# star-tracker-card.net
KiCad netlist of a schematic drawn in EAGLE
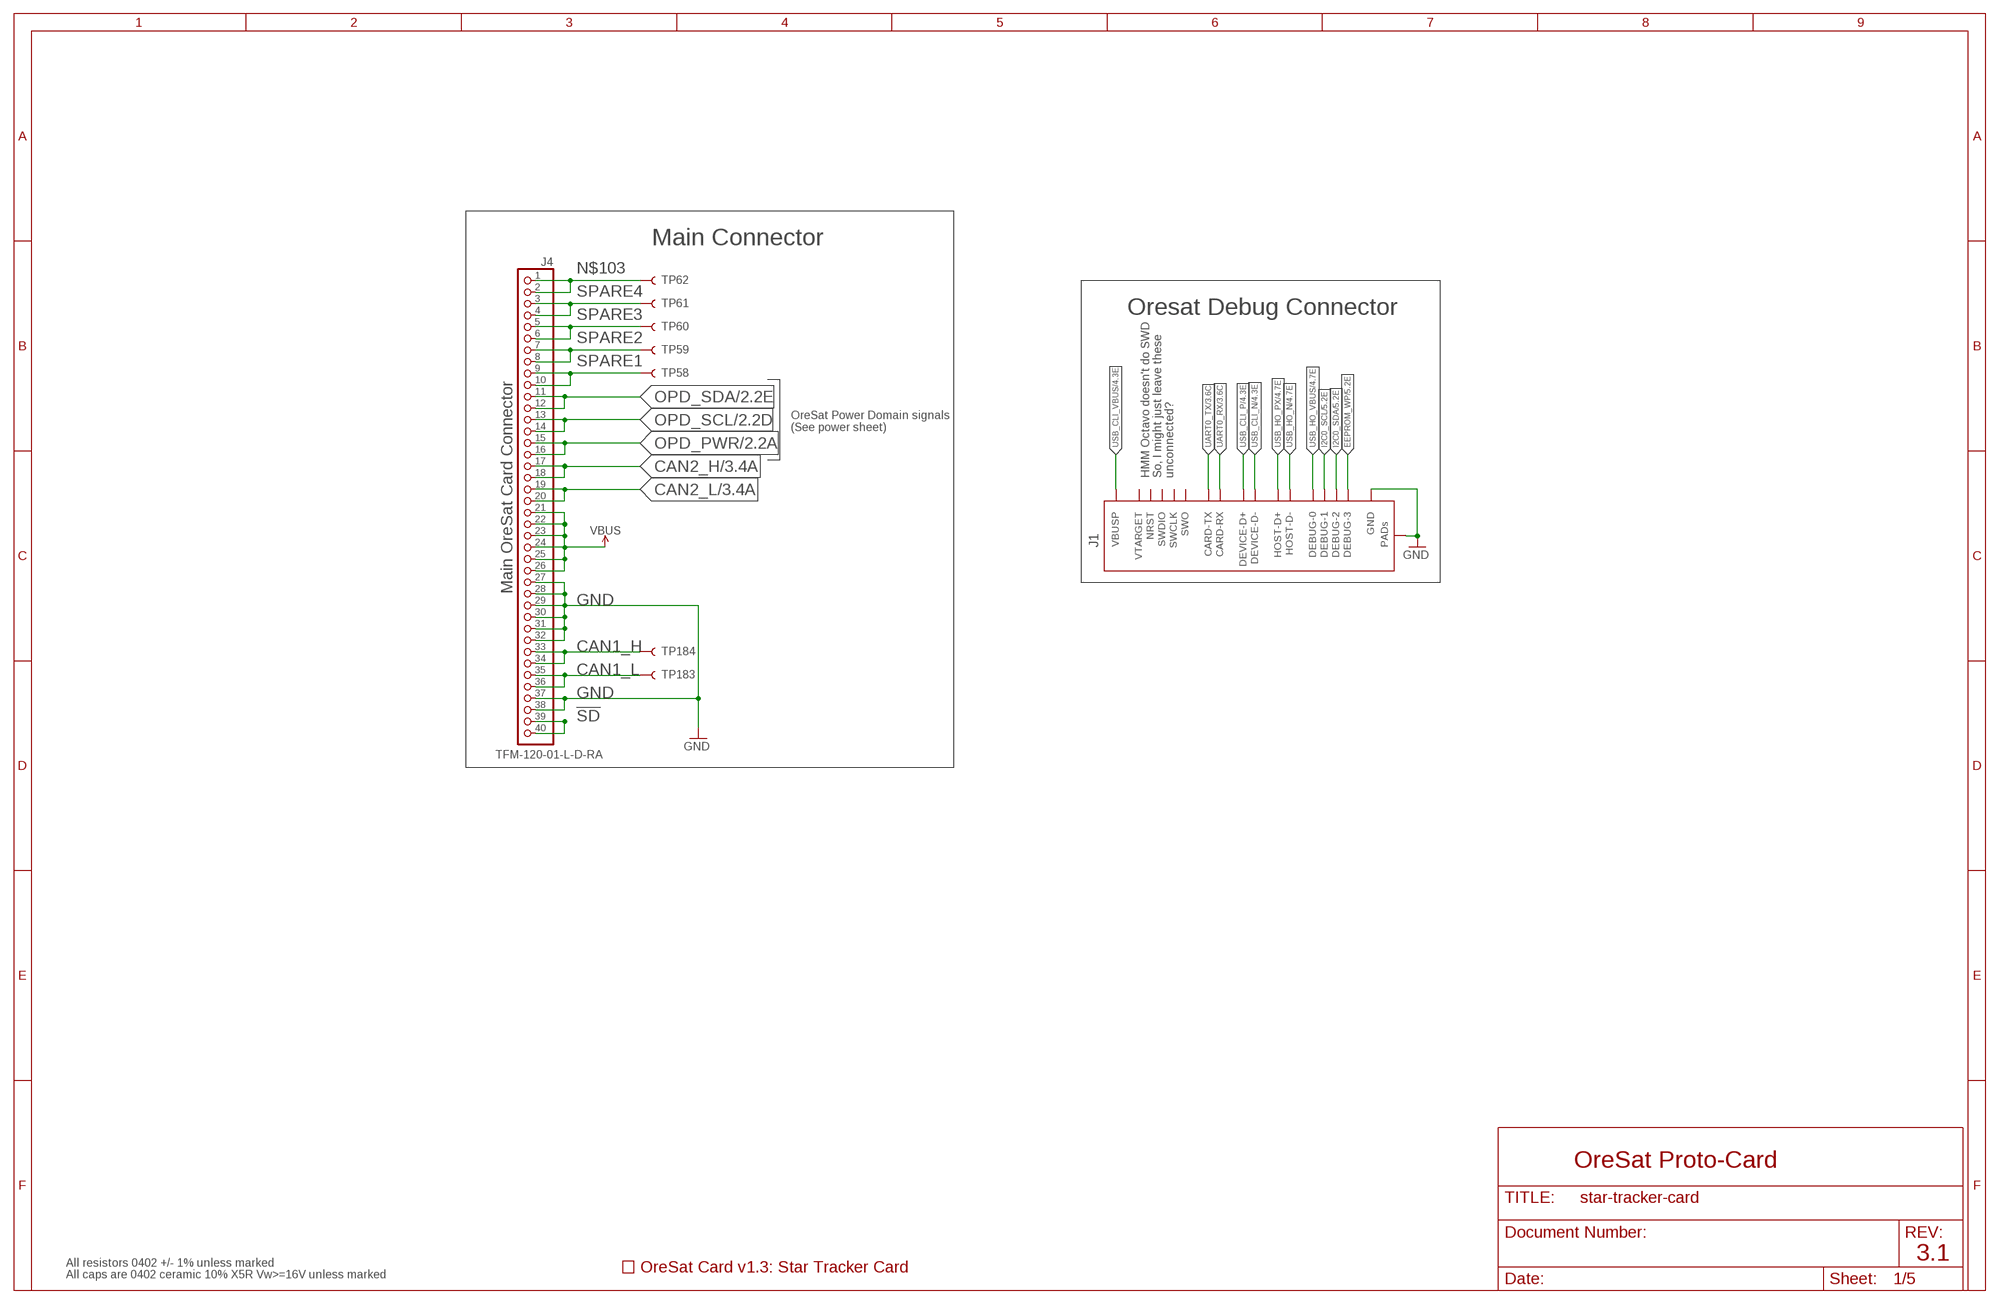
[diagram p0: schematic, sheet 1]
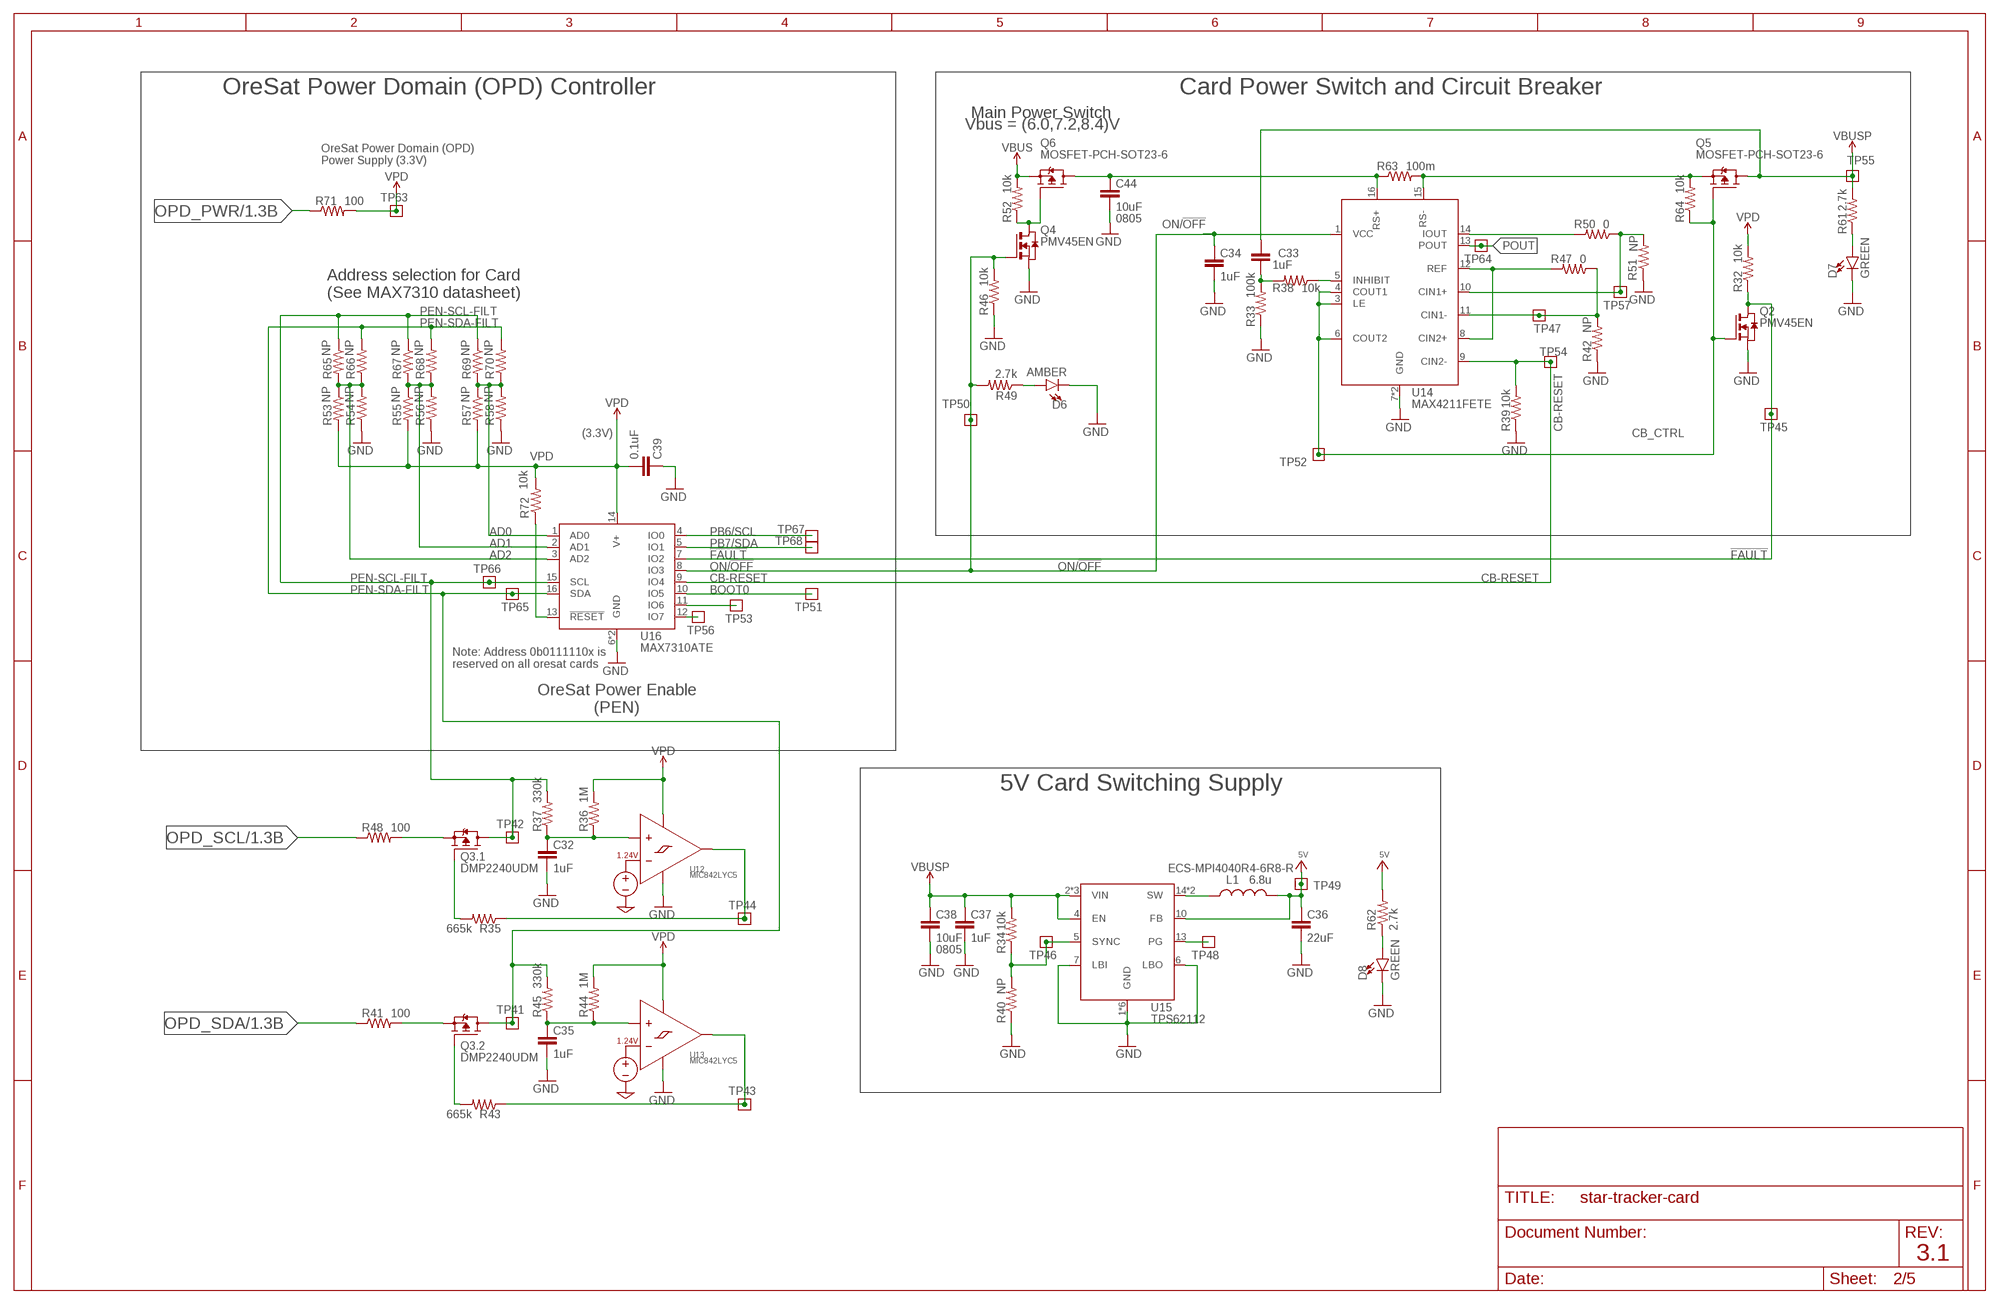
[diagram p1: schematic, sheet 2]
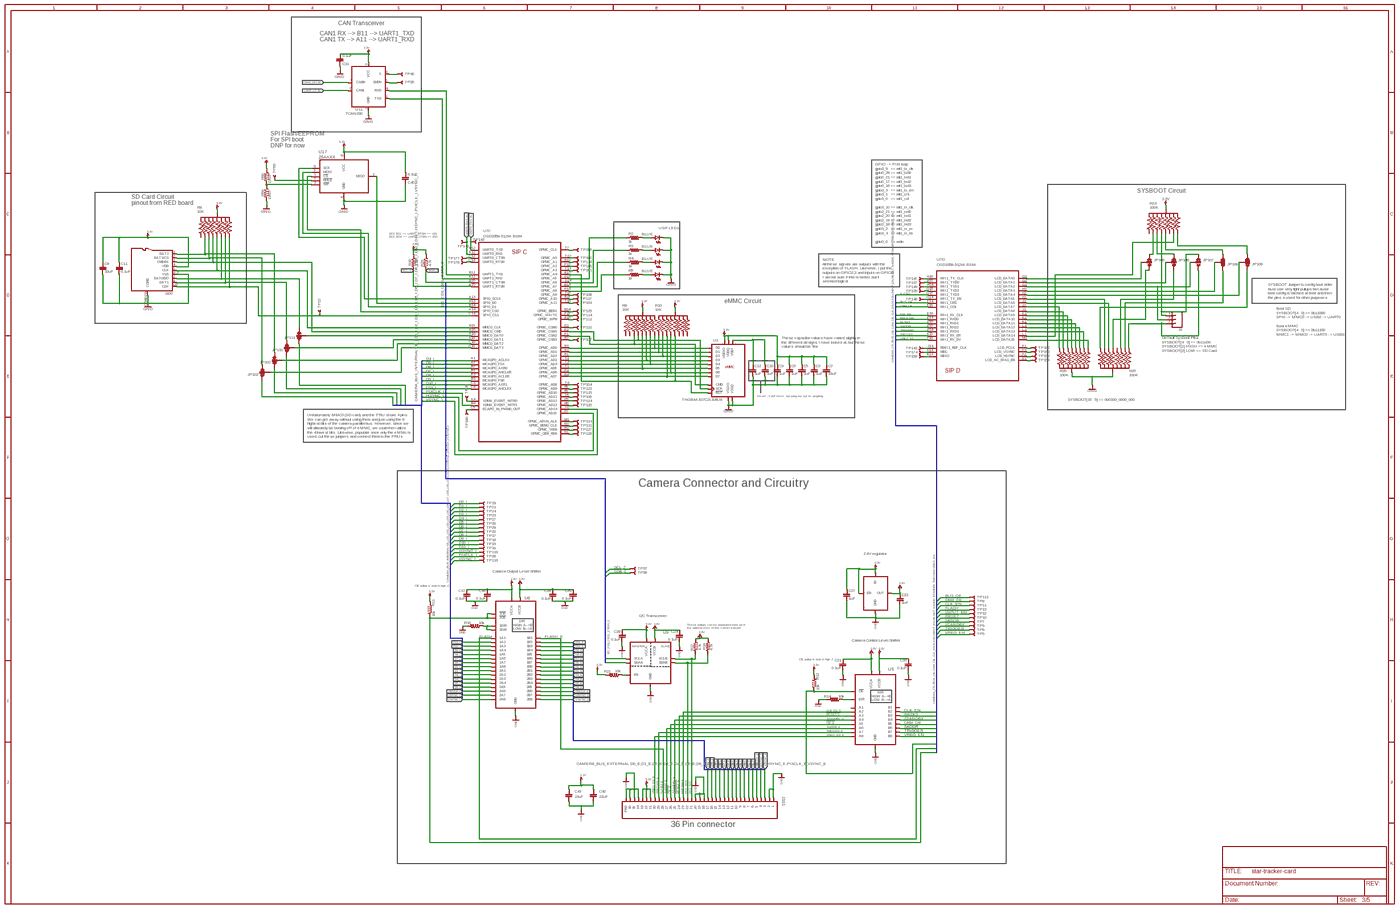
[diagram p2: schematic, sheet 3, overview]
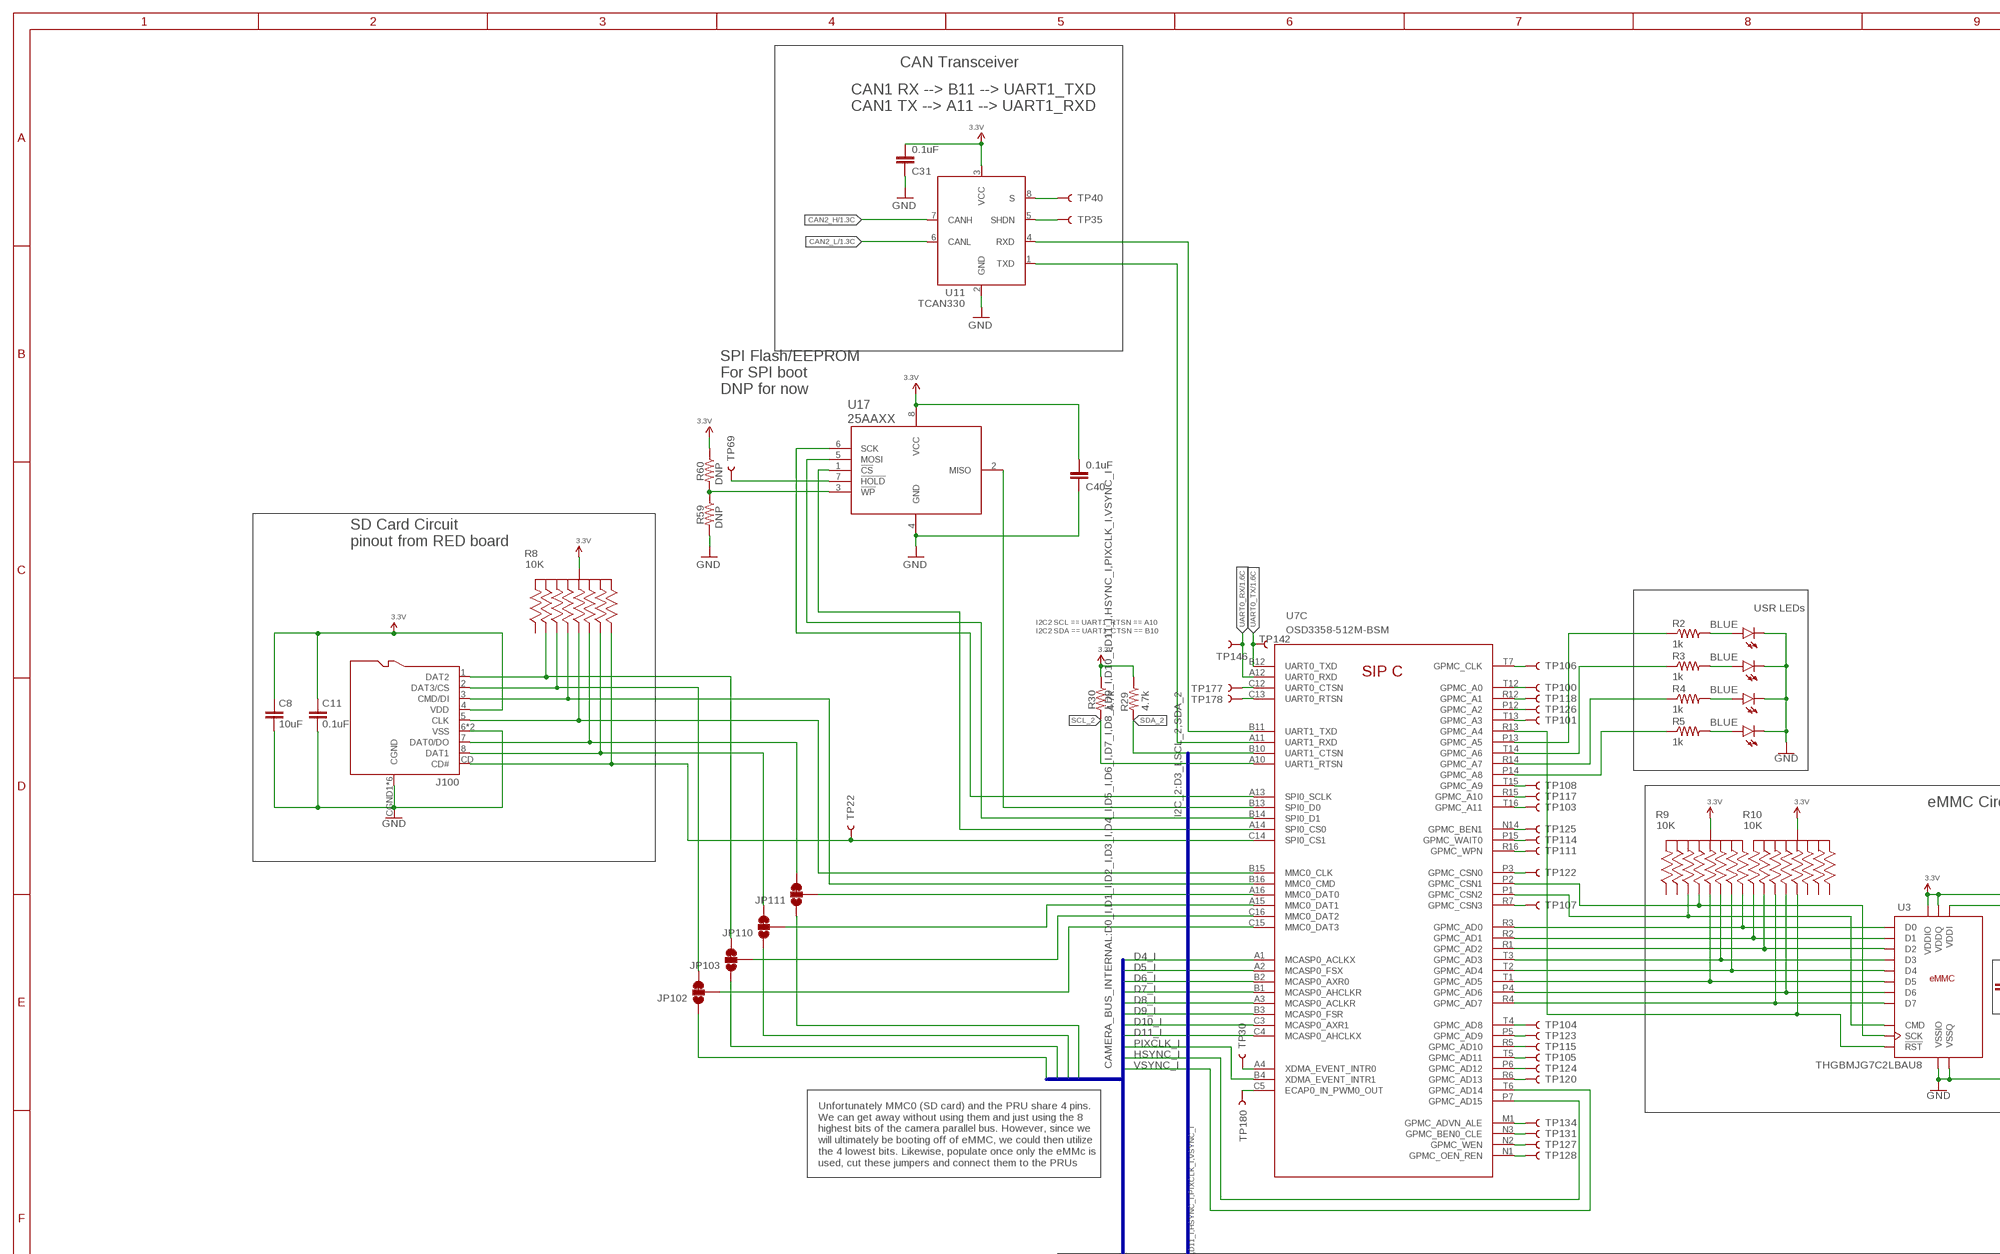
[diagram p3: schematic, sheet 3, part 1 of 4]
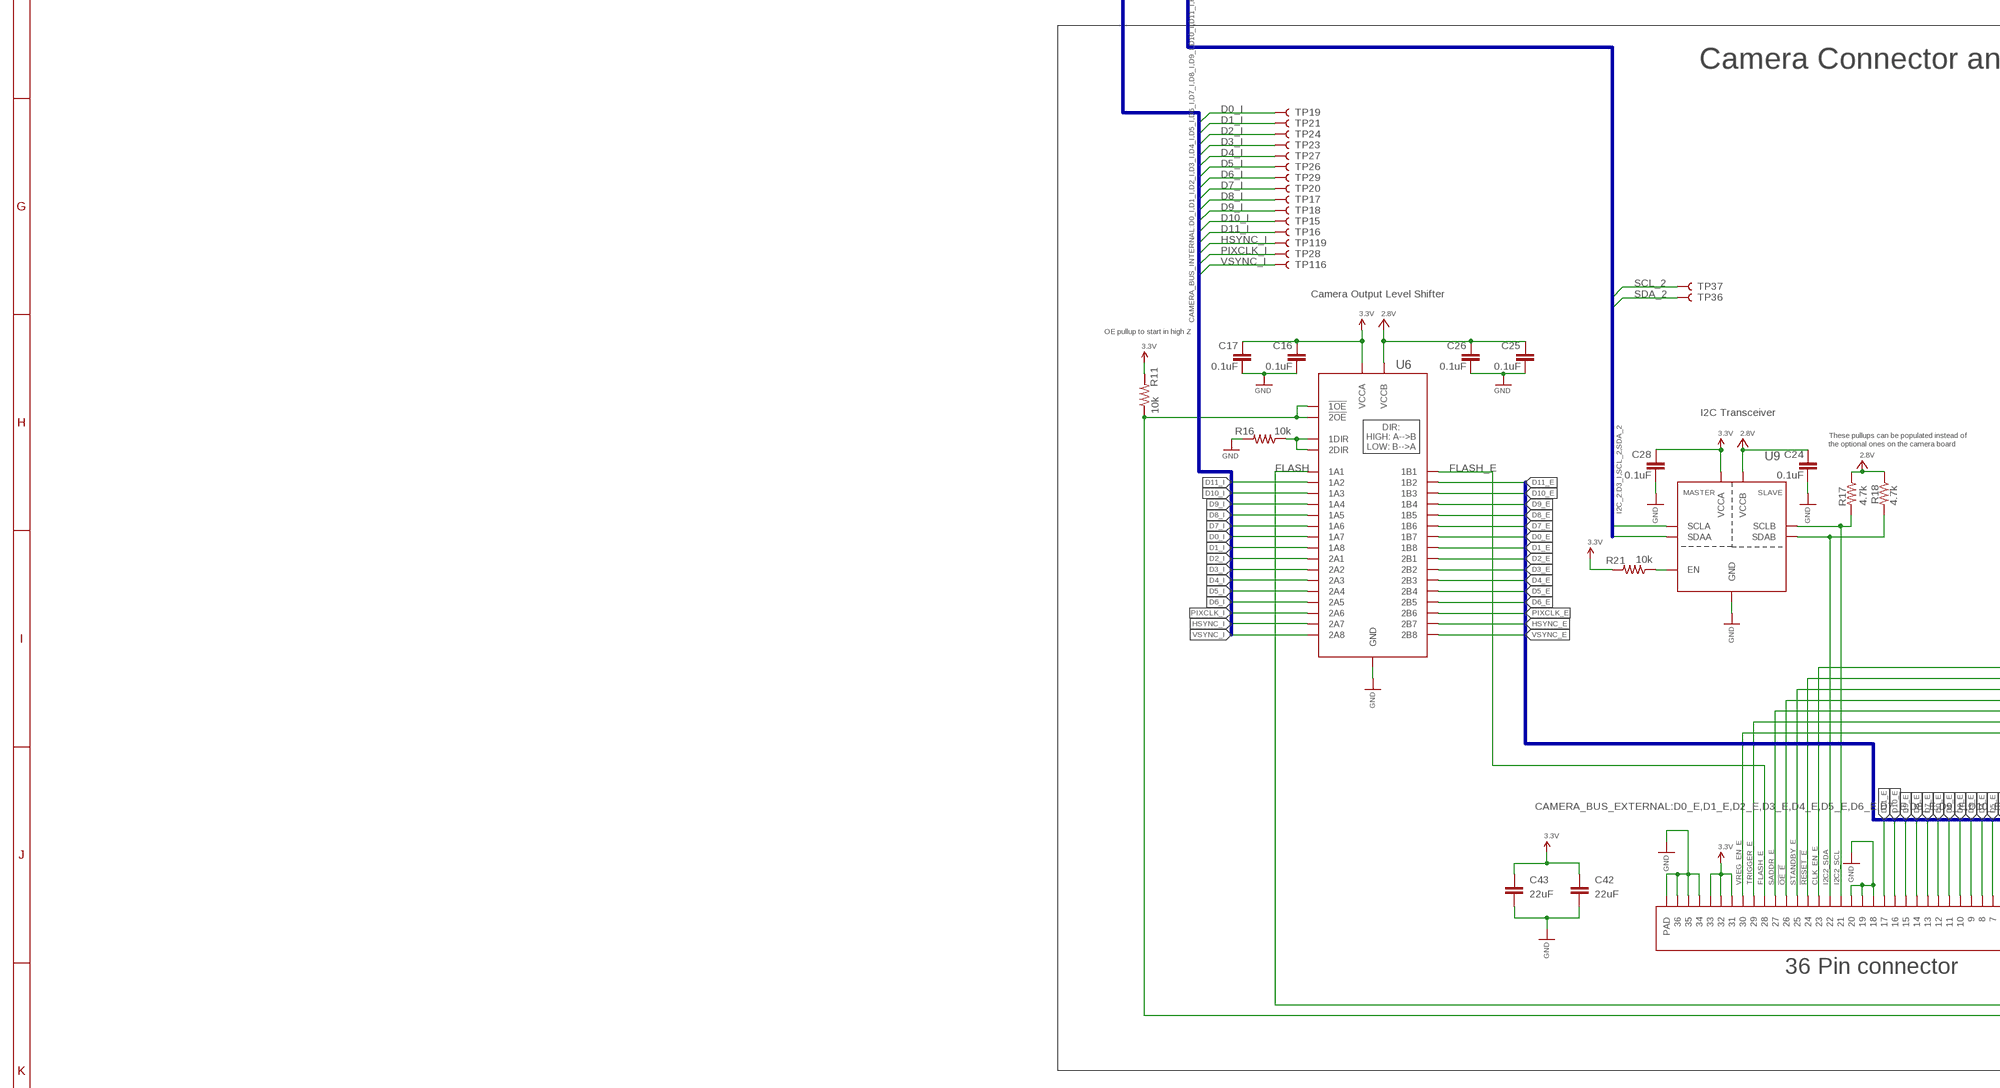
[diagram p4: schematic, sheet 3, part 2 of 4]
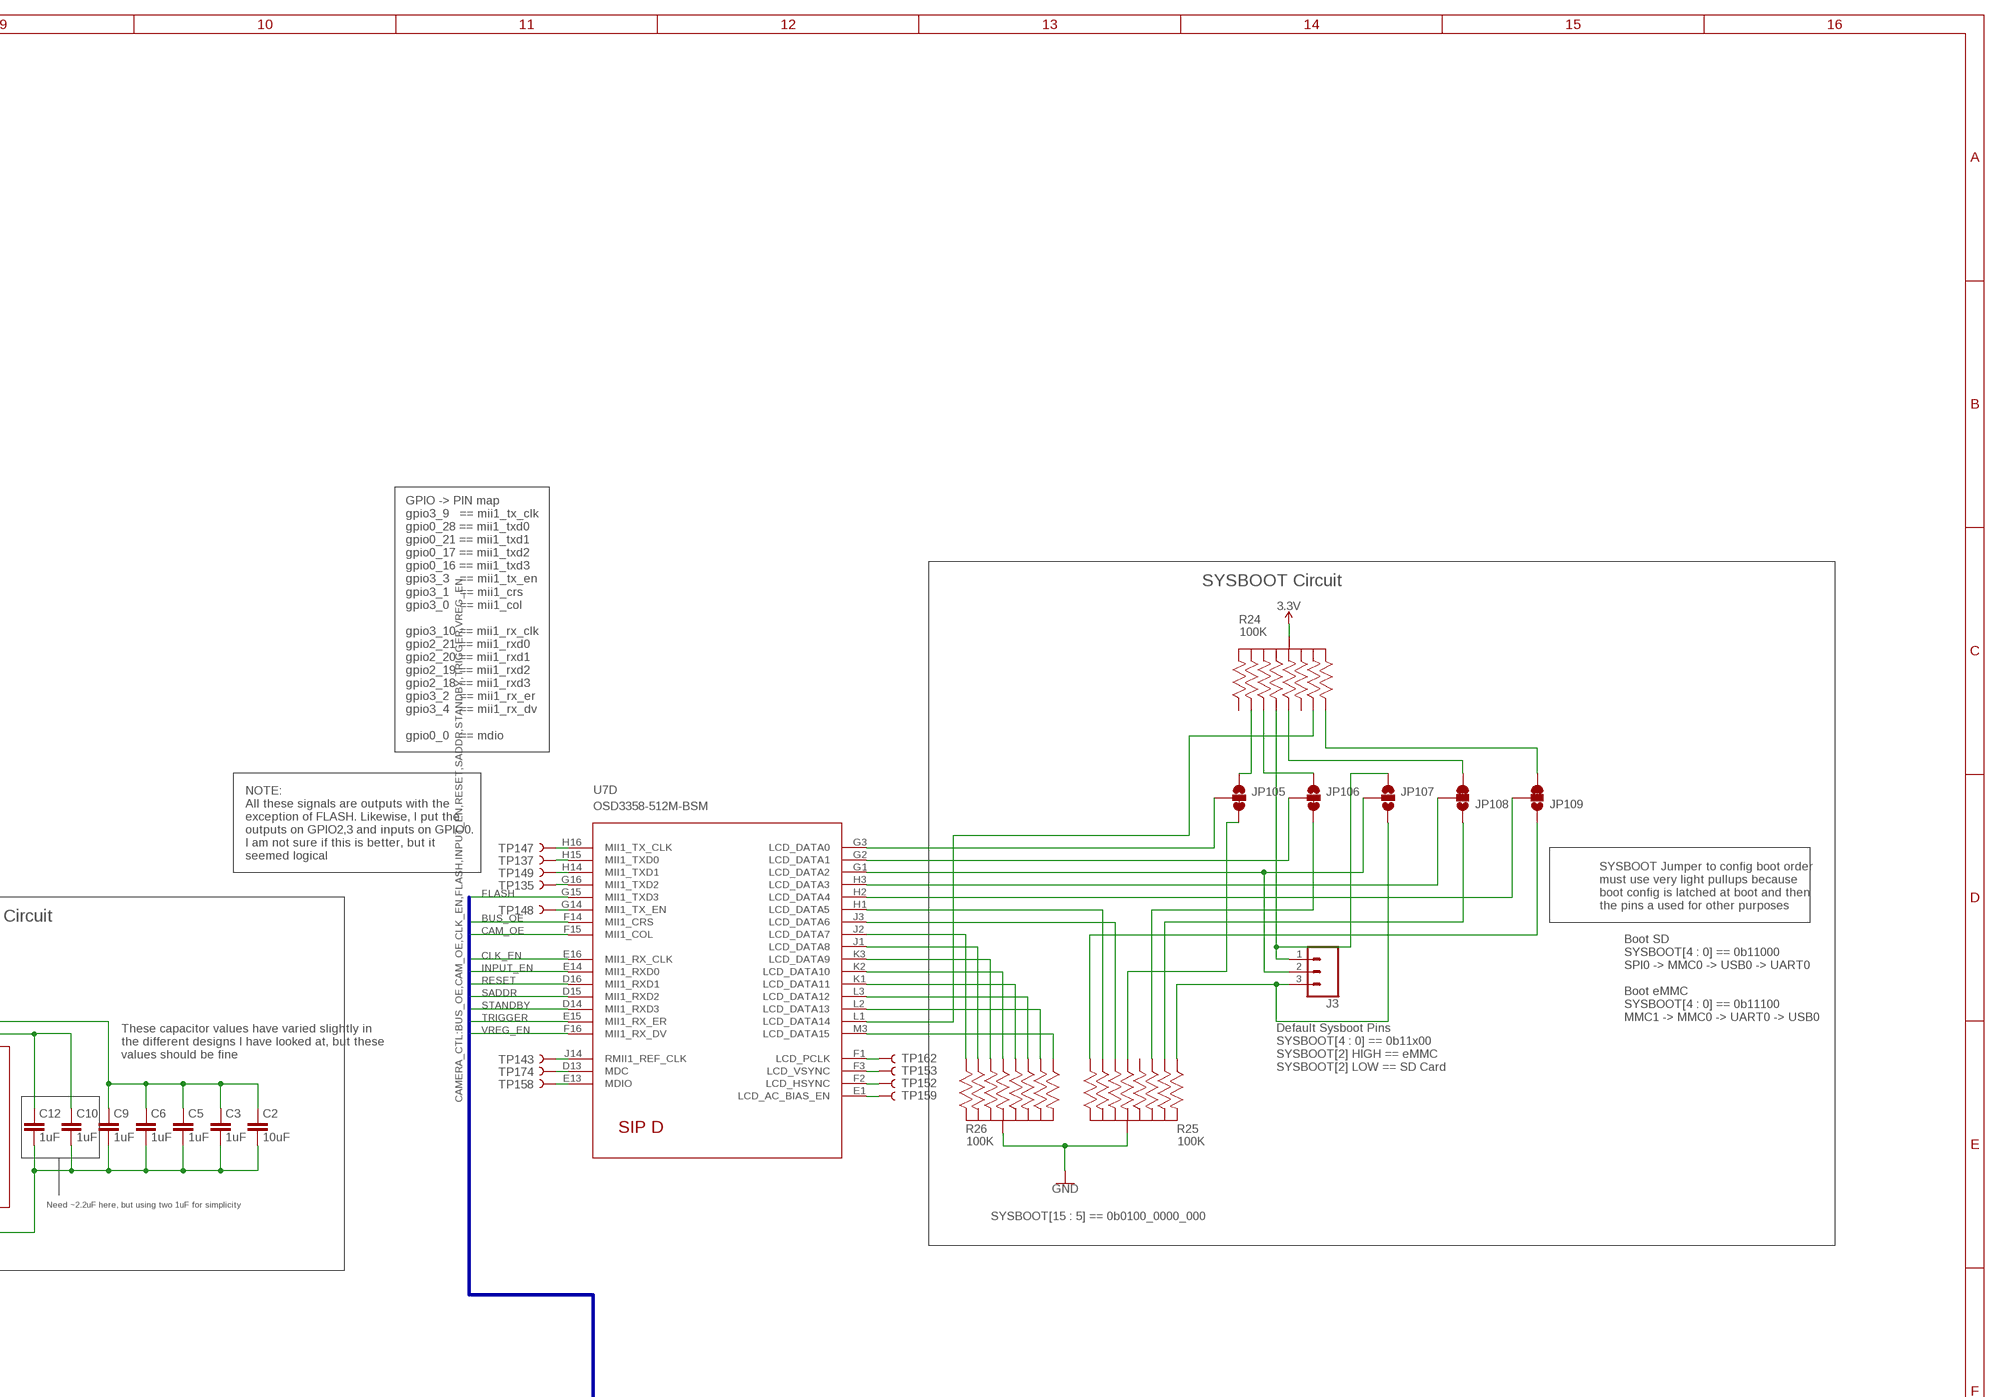
[diagram p5: schematic, sheet 3, part 3 of 4]
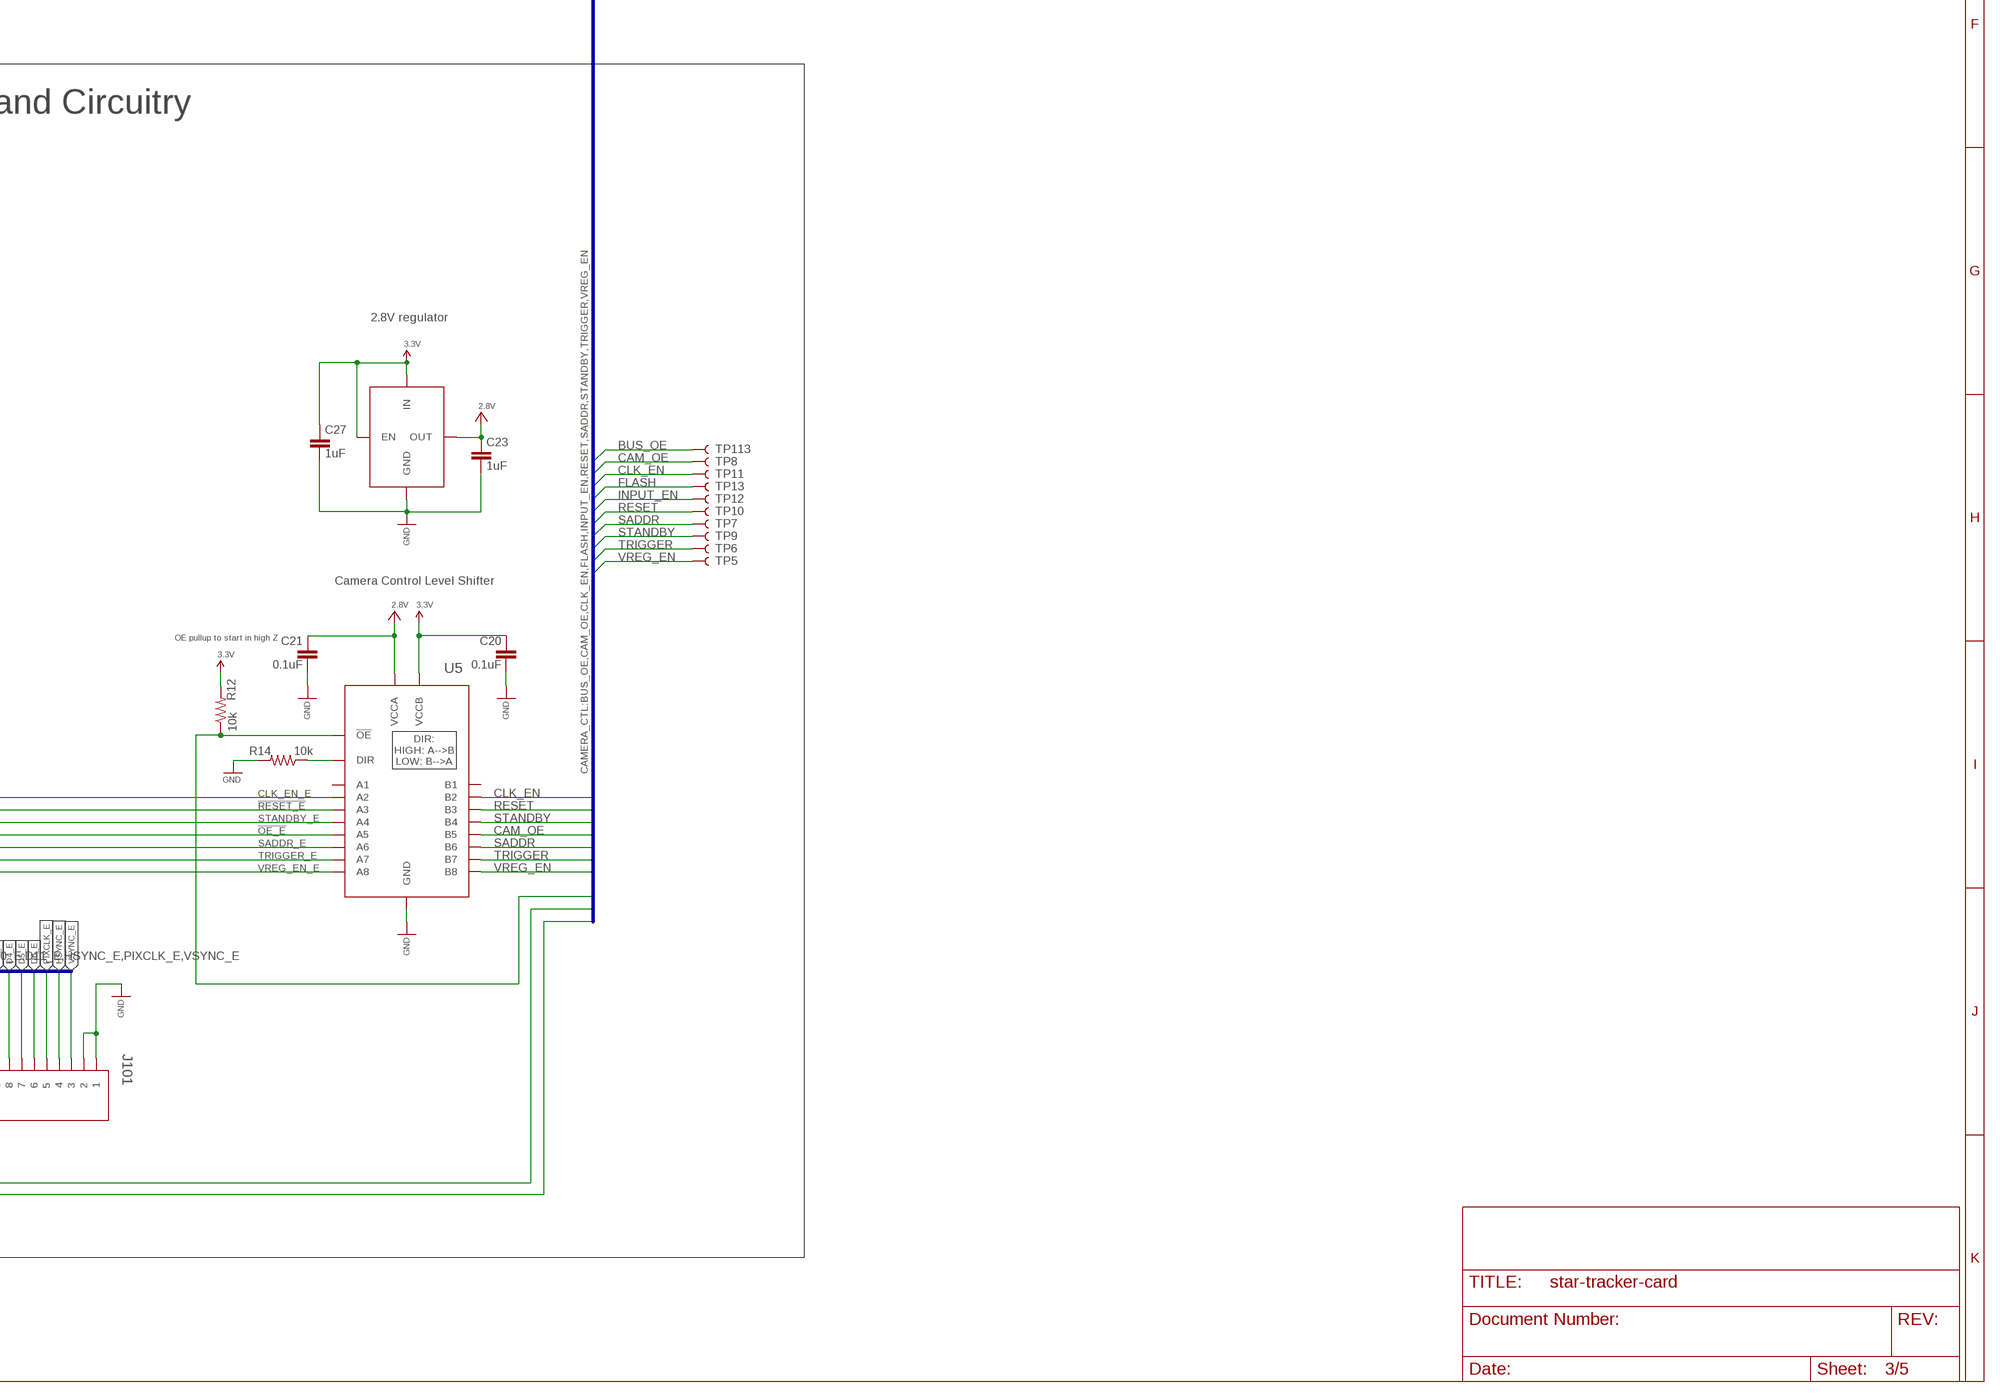
[diagram p6: schematic, sheet 3, part 4 of 4]
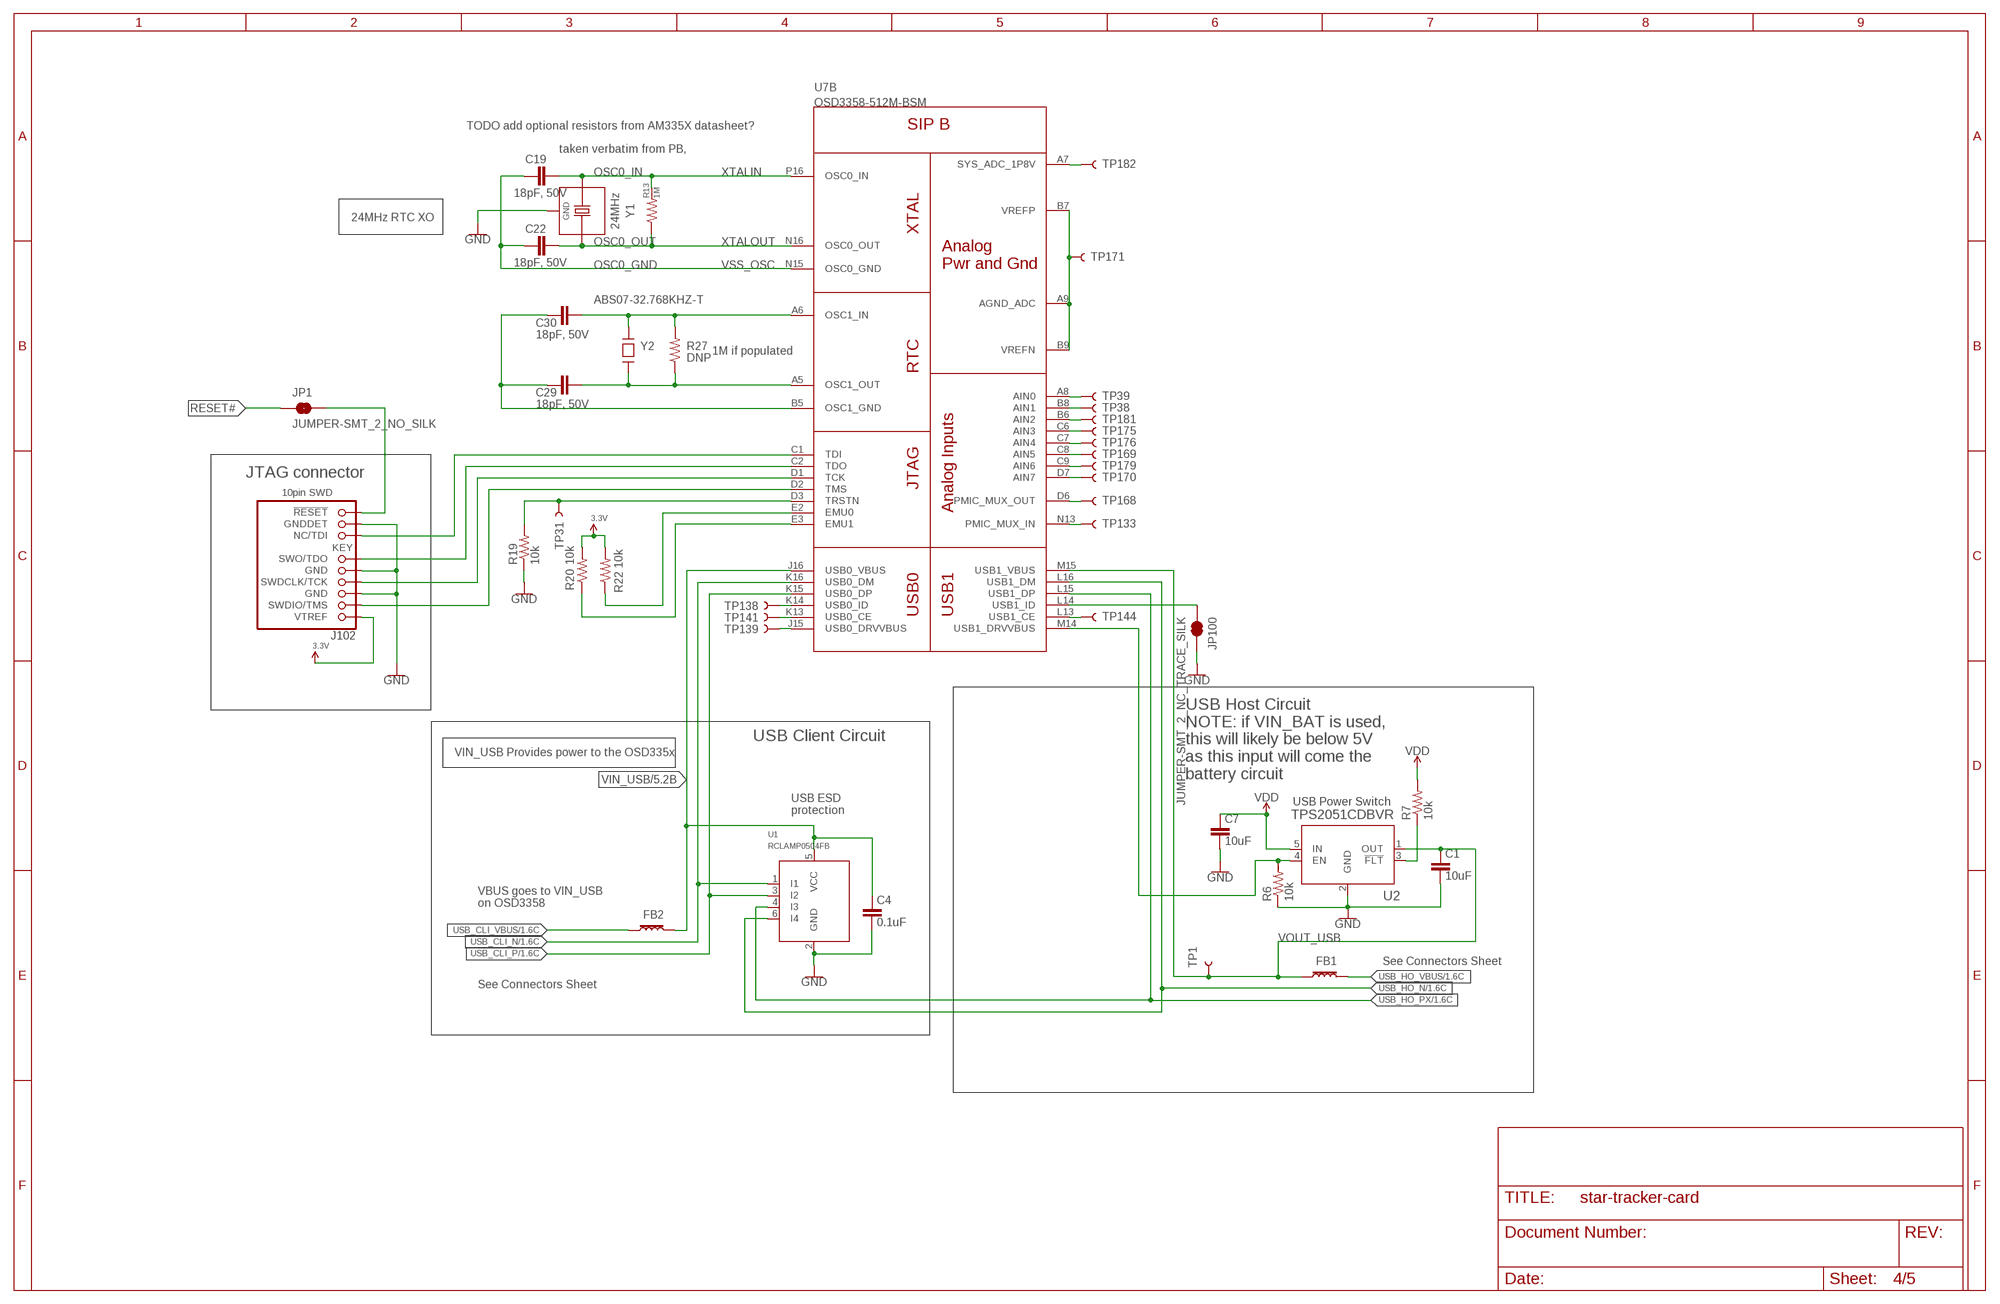
[diagram p7: schematic, sheet 4]
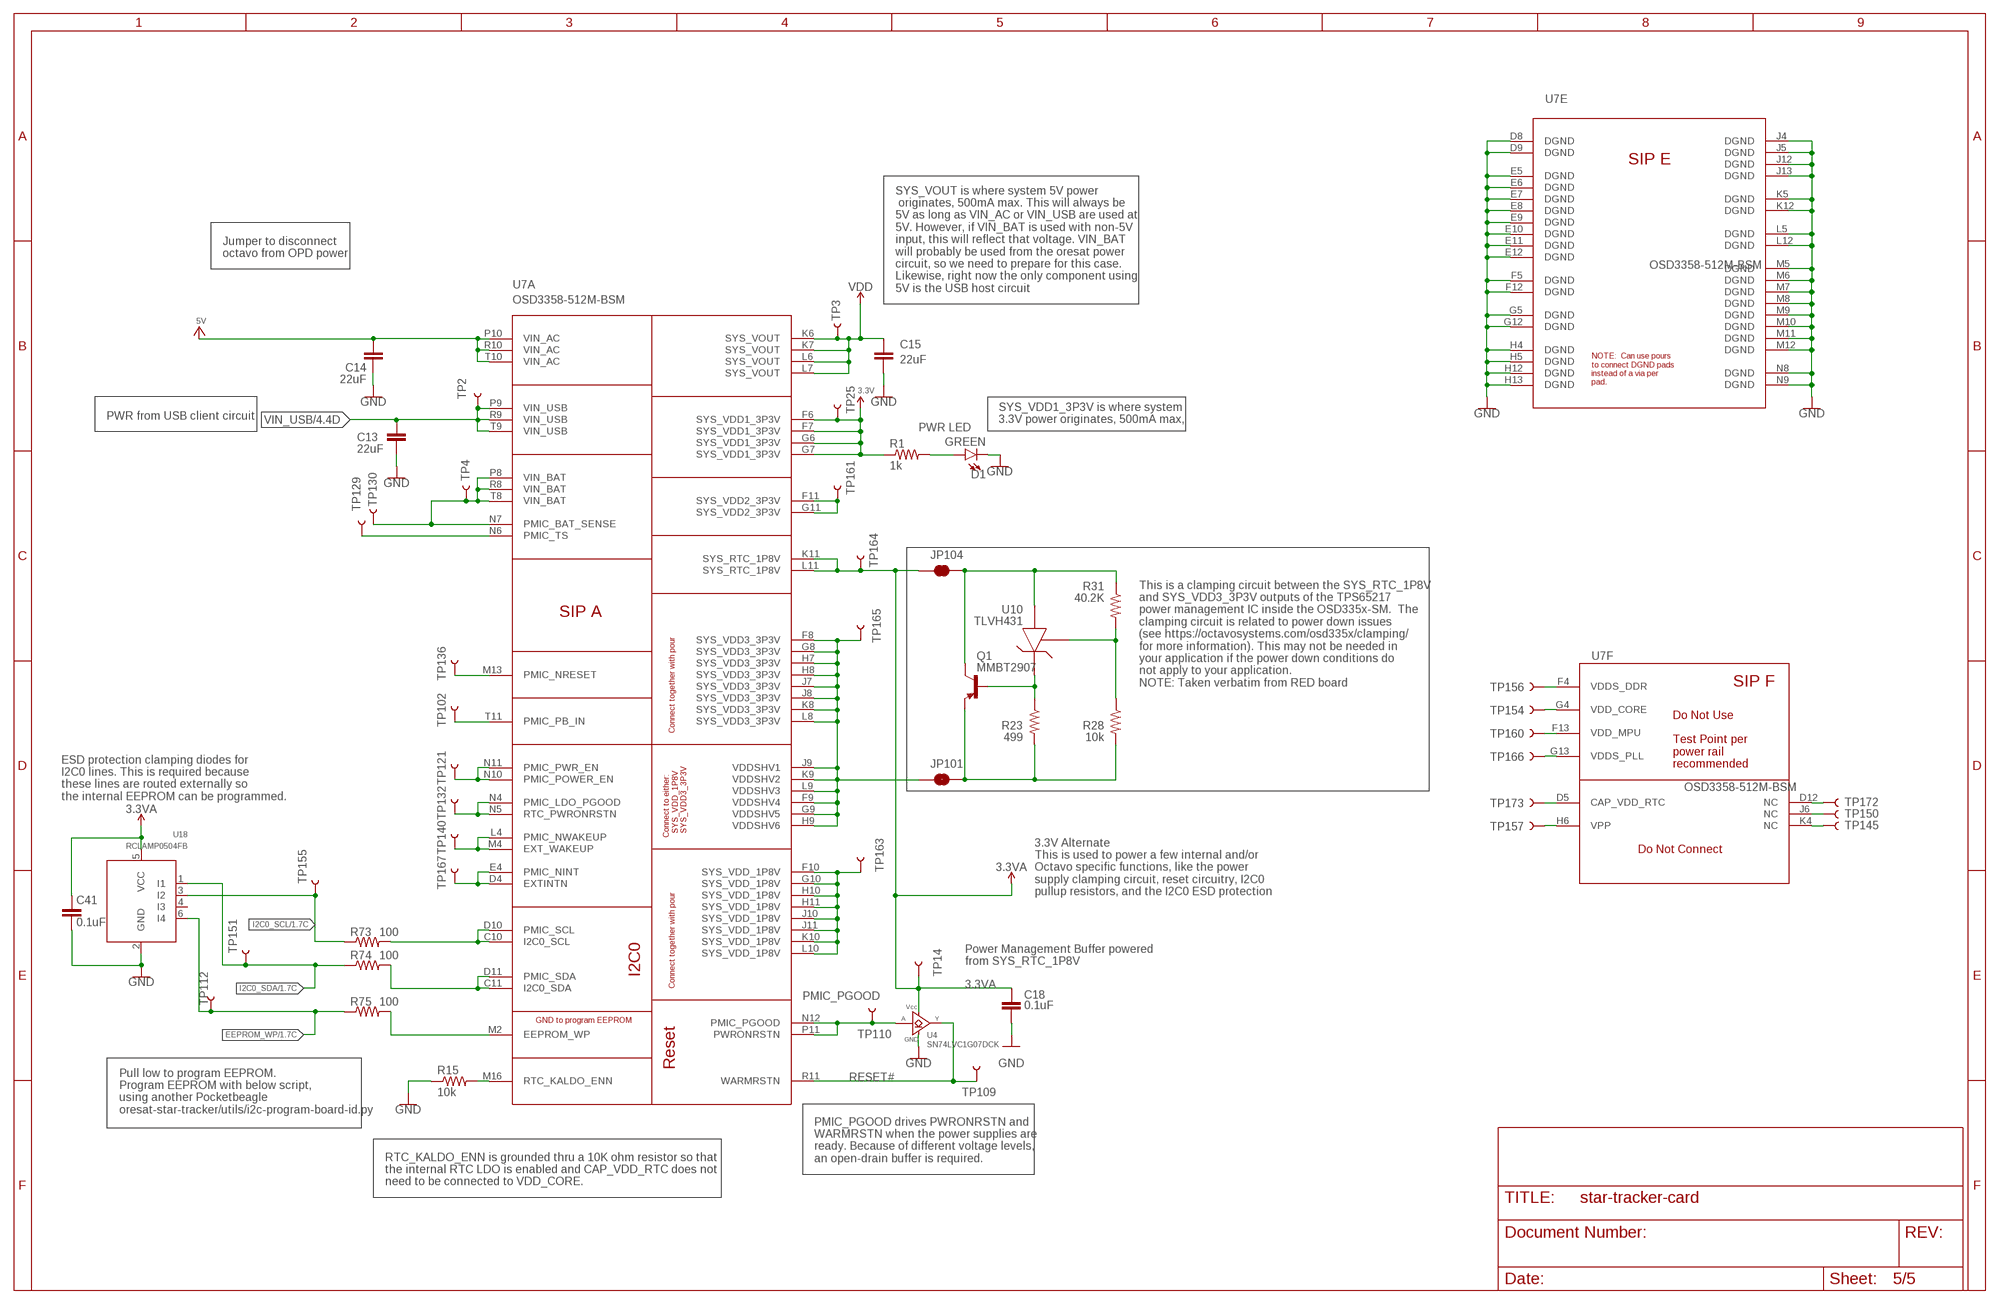
[diagram p8: schematic, sheet 5]

(export (version "E")
  (design (tool "Eeschema 10.0.6"))
  (components
    (comp (ref "C32")
      (value "1uF")
      (footprint "eagle-import:.0805-B-NOSILK")
      (libsource (lib "eagle-import") (part "C-EU0805-B-NOSILK"))
    )
    (comp (ref "C33")
      (value "1uF")
      (footprint "eagle-import:.0603-A")
      (fields (field (name "MFR") "Samsung") (field (name "MPN") "CL05B104KO5NNNC"))
      (libsource (lib "eagle-import") (part "C-EU0603-A"))
    )
    (comp (ref "C34")
      (value "1uF")
      (footprint "eagle-import:.0603-A")
      (libsource (lib "eagle-import") (part "C-EU0603-A"))
    )
    (comp (ref "C35")
      (value "1uF")
      (footprint "eagle-import:.0805-B-NOSILK")
      (libsource (lib "eagle-import") (part "C-EU0805-B-NOSILK"))
    )
    (comp (ref "C36")
      (value "22uF")
      (footprint "eagle-import:C1210")
      (libsource (lib "eagle-import") (part "C-EUC1210"))
    )
    (comp (ref "C37")
      (value "1uF")
      (footprint "eagle-import:.0603-A")
      (libsource (lib "eagle-import") (part "C-EU0603-A"))
    )
    (comp (ref "C38")
      (value "10uF")
      (footprint "eagle-import:.0805-B")
      (libsource (lib "eagle-import") (part "C-EU0805-B"))
    )
    (comp (ref "C39")
      (value "0.1uF")
      (footprint "eagle-import:.0603-A")
      (libsource (lib "eagle-import") (part "C-EU0603-A"))
    )
    (comp (ref "C44")
      (value "10uF")
      (footprint "eagle-import:.0805-B")
      (libsource (lib "eagle-import") (part "C-EU0805-B"))
    )
    (comp (ref "D6")
      (value "AMBER")
      (footprint "eagle-import:LED-0603")
      (libsource (lib "eagle-import") (part "SparkFun-LED_529_LED-GREEN0603"))
    )
    (comp (ref "D7")
      (value "GREEN")
      (footprint "eagle-import:LED-0603")
      (libsource (lib "eagle-import") (part "LED-GREEN0603"))
    )
    (comp (ref "D8")
      (value "GREEN")
      (footprint "eagle-import:LED-0603")
      (libsource (lib "eagle-import") (part "LED-GREEN0603"))
    )
    (comp (ref "L1")
      (value "6.8u")
      (footprint "eagle-import:ECS-MPI4040")
      (fields (field (name "MPN") "ECS-MPI4040R4-6R8-R"))
      (libsource (lib "eagle-import") (part "L-ECS-MPI4040"))
    )
    (comp (ref "Q2")
      (value "PMV45EN")
      (footprint "eagle-import:SOT23")
      (fields (field (name "MPN") "PMV45EN2R"))
      (libsource (lib "eagle-import") (part "PMV45EN"))
    )
    (comp (ref "Q3")
      (value "DMP2240UDM")
      (footprint "eagle-import:SOT23-6")
      (fields (field (name "MPN") "DMP2240UDM-7"))
      (libsource (lib "eagle-import") (part "Q-MOSFET-PCH-dual-SOT23-6_MOSFET-PCH-SOT23-6"))
    )
    (comp (ref "Q4")
      (value "PMV45EN")
      (footprint "eagle-import:SOT23")
      (fields (field (name "MPN") "PMV45EN2R"))
      (libsource (lib "eagle-import") (part "PMV45EN"))
    )
    (comp (ref "Q5")
      (value "MOSFET-PCH-SOT23-6")
      (footprint "eagle-import:SOT23-6")
      (fields (field (name "MPN") "DMP3050LVT-7") (field (name "MPN_1") "DMP3050LVT-7"))
      (libsource (lib "eagle-import") (part "MOSFET-PCH-SOT23-6"))
    )
    (comp (ref "Q6")
      (value "MOSFET-PCH-SOT23-6")
      (footprint "eagle-import:SOT23-6")
      (fields (field (name "MPN") "DMP3050LVT-7") (field (name "MPN_1") "DMP3050LVT-7"))
      (libsource (lib "eagle-import") (part "MOSFET-PCH-SOT23-6"))
    )
    (comp (ref "R32")
      (value "10k")
      (footprint "eagle-import:.0603-A")
      (libsource (lib "eagle-import") (part "R-US_0603-A"))
    )
    (comp (ref "R33")
      (value "100k")
      (footprint "eagle-import:.0603-A")
      (fields (field (name "MFR") "Samsung") (field (name "MPN") "RC1005F6653CS"))
      (libsource (lib "eagle-import") (part "R-US_0603-A"))
    )
    (comp (ref "R34")
      (value "10k")
      (footprint "eagle-import:.0603-A")
      (libsource (lib "eagle-import") (part "R-US_0603-A"))
    )
    (comp (ref "R35")
      (value "665k")
      (footprint "eagle-import:.0603-A")
      (libsource (lib "eagle-import") (part "R-US_0603-A"))
    )
    (comp (ref "R36")
      (value "1M")
      (footprint "eagle-import:.0603-A")
      (libsource (lib "eagle-import") (part "R-US_0603-A"))
    )
    (comp (ref "R37")
      (value "330k")
      (footprint "eagle-import:.0603-A")
      (libsource (lib "eagle-import") (part "R-US_0603-A"))
    )
    (comp (ref "R38")
      (value "10k")
      (footprint "eagle-import:.0603-A")
      (fields (field (name "MFR") "Samsung") (field (name "MPN") "RC1005F6653CS"))
      (libsource (lib "eagle-import") (part "R-US_0603-A"))
    )
    (comp (ref "R39")
      (value "10k")
      (footprint "eagle-import:.0603-A")
      (libsource (lib "eagle-import") (part "R-US_0603-A"))
    )
    (comp (ref "R40")
      (value "NP")
      (footprint "eagle-import:.0603-A")
      (fields (field (name "MFR") "Samsung") (field (name "MPN") "RC1005F6653CS"))
      (libsource (lib "eagle-import") (part "R-US_0603-A"))
    )
    (comp (ref "R41")
      (value "100")
      (footprint "eagle-import:.0603-A")
      (libsource (lib "eagle-import") (part "R-US_0603-A"))
    )
    (comp (ref "R42")
      (value "NP")
      (footprint "eagle-import:.0603-A")
      (fields (field (name "MFR") "Samsung") (field (name "MPN") "RC1005F6653CS"))
      (libsource (lib "eagle-import") (part "R-US_0603-A"))
    )
    (comp (ref "R43")
      (value "665k")
      (footprint "eagle-import:.0603-A")
      (libsource (lib "eagle-import") (part "R-US_0603-A"))
    )
    (comp (ref "R44")
      (value "1M")
      (footprint "eagle-import:.0603-A")
      (libsource (lib "eagle-import") (part "R-US_0603-A"))
    )
    (comp (ref "R45")
      (value "330k")
      (footprint "eagle-import:.0603-A")
      (libsource (lib "eagle-import") (part "R-US_0603-A"))
    )
    (comp (ref "R46")
      (value "10k")
      (footprint "eagle-import:.0603-A")
      (libsource (lib "eagle-import") (part "R-US_0603-A"))
    )
    (comp (ref "R47")
      (value "0")
      (footprint "eagle-import:.0603-A")
      (libsource (lib "eagle-import") (part "R-US_0603-A"))
    )
    (comp (ref "R48")
      (value "100")
      (footprint "eagle-import:.0603-A")
      (libsource (lib "eagle-import") (part "R-US_0603-A"))
    )
    (comp (ref "R49")
      (value "2.7k")
      (footprint "eagle-import:.0603-A")
      (libsource (lib "eagle-import") (part "R-US_0603-A"))
    )
    (comp (ref "R50")
      (value "0")
      (footprint "eagle-import:.0603-A")
      (libsource (lib "eagle-import") (part "R-US_0603-A"))
    )
    (comp (ref "R51")
      (value "NP")
      (footprint "eagle-import:.0603-A")
      (fields (field (name "MFR") "Samsung") (field (name "MPN") "RC1005F6653CS"))
      (libsource (lib "eagle-import") (part "R-US_0603-A"))
    )
    (comp (ref "R52")
      (value "10k")
      (footprint "eagle-import:.0603-A")
      (libsource (lib "eagle-import") (part "R-US_0603-A"))
    )
    (comp (ref "R53")
      (value "NP")
      (footprint "eagle-import:.0603-A")
      (fields (field (name "MFR") "Samsung") (field (name "MPN") "RC1005F6653CS"))
      (libsource (lib "eagle-import") (part "R-US_0603-A"))
    )
    (comp (ref "R54")
      (value "NP")
      (footprint "eagle-import:.0603-A")
      (fields (field (name "MFR") "Samsung") (field (name "MPN") "RC1005F6653CS"))
      (libsource (lib "eagle-import") (part "R-US_0603-A"))
    )
    (comp (ref "R55")
      (value "NP")
      (footprint "eagle-import:.0603-A")
      (fields (field (name "MFR") "Samsung") (field (name "MPN") "RC1005F6653CS"))
      (libsource (lib "eagle-import") (part "R-US_0603-A"))
    )
    (comp (ref "R56")
      (value "NP")
      (footprint "eagle-import:.0603-A")
      (fields (field (name "MFR") "Samsung") (field (name "MPN") "RC1005F6653CS"))
      (libsource (lib "eagle-import") (part "R-US_0603-A"))
    )
    (comp (ref "R57")
      (value "NP")
      (footprint "eagle-import:.0603-A")
      (fields (field (name "MFR") "Samsung") (field (name "MPN") "RC1005F6653CS"))
      (libsource (lib "eagle-import") (part "R-US_0603-A"))
    )
    (comp (ref "R58")
      (value "NP")
      (footprint "eagle-import:.0603-A")
      (fields (field (name "MFR") "Samsung") (field (name "MPN") "RC1005F6653CS"))
      (libsource (lib "eagle-import") (part "R-US_0603-A"))
    )
    (comp (ref "R61")
      (value "2.7k")
      (footprint "eagle-import:.0603-A")
      (libsource (lib "eagle-import") (part "R-US_0603-A"))
    )
    (comp (ref "R62")
      (value "2.7k")
      (footprint "eagle-import:.0603-A")
      (libsource (lib "eagle-import") (part "R-US_0603-A"))
    )
    (comp (ref "R63")
      (value "100m")
      (footprint "eagle-import:R1206")
      (libsource (lib "eagle-import") (part "rcl_334_R-US_R1206"))
    )
    (comp (ref "R64")
      (value "10k")
      (footprint "eagle-import:.0603-A")
      (libsource (lib "eagle-import") (part "R-US_0603-A"))
    )
    (comp (ref "R65")
      (value "NP")
      (footprint "eagle-import:.0603-A")
      (fields (field (name "MFR") "Samsung") (field (name "MPN") "RC1005F6653CS"))
      (libsource (lib "eagle-import") (part "R-US_0603-A"))
    )
    (comp (ref "R66")
      (value "NP")
      (footprint "eagle-import:.0603-A")
      (fields (field (name "MFR") "Samsung") (field (name "MPN") "RC1005F6653CS"))
      (libsource (lib "eagle-import") (part "R-US_0603-A"))
    )
    (comp (ref "R67")
      (value "NP")
      (footprint "eagle-import:.0603-A")
      (fields (field (name "MFR") "Samsung") (field (name "MPN") "RC1005F6653CS"))
      (libsource (lib "eagle-import") (part "R-US_0603-A"))
    )
    (comp (ref "R68")
      (value "NP")
      (footprint "eagle-import:.0603-A")
      (fields (field (name "MFR") "Samsung") (field (name "MPN") "RC1005F6653CS"))
      (libsource (lib "eagle-import") (part "R-US_0603-A"))
    )
    (comp (ref "R69")
      (value "NP")
      (footprint "eagle-import:.0603-A")
      (fields (field (name "MFR") "Samsung") (field (name "MPN") "RC1005F6653CS"))
      (libsource (lib "eagle-import") (part "R-US_0603-A"))
    )
    (comp (ref "R70")
      (value "NP")
      (footprint "eagle-import:.0603-A")
      (fields (field (name "MFR") "Samsung") (field (name "MPN") "RC1005F6653CS"))
      (libsource (lib "eagle-import") (part "R-US_0603-A"))
    )
    (comp (ref "R71")
      (value "100")
      (footprint "eagle-import:.0603-A")
      (libsource (lib "eagle-import") (part "R-US_0603-A"))
    )
    (comp (ref "R72")
      (value "10k")
      (footprint "eagle-import:.0603-A")
      (libsource (lib "eagle-import") (part "R-US_0603-A"))
    )
    (comp (ref "TP41")
      (value "TEST-POINT")
      (footprint "eagle-import:2MM-TEST-POINT")
      (libsource (lib "eagle-import") (part "TEST-POINT"))
    )
    (comp (ref "TP42")
      (value "TEST-POINT")
      (footprint "eagle-import:2MM-TEST-POINT")
      (libsource (lib "eagle-import") (part "TEST-POINT"))
    )
    (comp (ref "TP43")
      (value "TEST-POINT")
      (footprint "eagle-import:2MM-TEST-POINT")
      (libsource (lib "eagle-import") (part "TEST-POINT"))
    )
    (comp (ref "TP44")
      (value "TEST-POINT")
      (footprint "eagle-import:2MM-TEST-POINT")
      (libsource (lib "eagle-import") (part "TEST-POINT"))
    )
    (comp (ref "TP45")
      (value "TEST-POINT")
      (footprint "eagle-import:2MM-TEST-POINT")
      (libsource (lib "eagle-import") (part "TEST-POINT"))
    )
    (comp (ref "TP46")
      (value "TEST-POINT")
      (footprint "eagle-import:2MM-TEST-POINT")
      (libsource (lib "eagle-import") (part "TEST-POINT"))
    )
    (comp (ref "TP47")
      (value "TEST-POINT")
      (footprint "eagle-import:2MM-TEST-POINT")
      (libsource (lib "eagle-import") (part "TEST-POINT"))
    )
    (comp (ref "TP48")
      (value "TEST-POINT")
      (footprint "eagle-import:2MM-TEST-POINT")
      (libsource (lib "eagle-import") (part "TEST-POINT"))
    )
    (comp (ref "TP49")
      (value "TEST-POINT")
      (footprint "eagle-import:2MM-TEST-POINT")
      (libsource (lib "eagle-import") (part "TEST-POINT"))
    )
    (comp (ref "TP50")
      (value "TEST-POINT")
      (footprint "eagle-import:2MM-TEST-POINT")
      (libsource (lib "eagle-import") (part "TEST-POINT"))
    )
    (comp (ref "TP51")
      (value "TEST-POINT")
      (footprint "eagle-import:2MM-TEST-POINT")
      (libsource (lib "eagle-import") (part "TEST-POINT"))
    )
    (comp (ref "TP52")
      (value "TEST-POINT")
      (footprint "eagle-import:2MM-TEST-POINT")
      (libsource (lib "eagle-import") (part "TEST-POINT"))
    )
    (comp (ref "TP53")
      (value "TEST-POINT")
      (footprint "eagle-import:2MM-TEST-POINT")
      (libsource (lib "eagle-import") (part "TEST-POINT"))
    )
    (comp (ref "TP54")
      (value "TEST-POINT")
      (footprint "eagle-import:2MM-TEST-POINT")
      (libsource (lib "eagle-import") (part "TEST-POINT"))
    )
    (comp (ref "TP55")
      (value "TEST-POINT")
      (footprint "eagle-import:2MM-TEST-POINT")
      (libsource (lib "eagle-import") (part "TEST-POINT"))
    )
    (comp (ref "TP56")
      (value "TEST-POINT")
      (footprint "eagle-import:2MM-TEST-POINT")
      (libsource (lib "eagle-import") (part "TEST-POINT"))
    )
    (comp (ref "TP57")
      (value "TEST-POINT")
      (footprint "eagle-import:2MM-TEST-POINT")
      (libsource (lib "eagle-import") (part "TEST-POINT"))
    )
    (comp (ref "TP63")
      (value "TEST-POINT")
      (footprint "eagle-import:2MM-TEST-POINT")
      (libsource (lib "eagle-import") (part "TEST-POINT"))
    )
    (comp (ref "TP64")
      (value "TEST-POINT")
      (footprint "eagle-import:2MM-TEST-POINT")
      (libsource (lib "eagle-import") (part "TEST-POINT"))
    )
    (comp (ref "TP65")
      (value "TEST-POINT")
      (footprint "eagle-import:2MM-TEST-POINT")
      (libsource (lib "eagle-import") (part "TEST-POINT"))
    )
    (comp (ref "TP66")
      (value "TEST-POINT")
      (footprint "eagle-import:2MM-TEST-POINT")
      (libsource (lib "eagle-import") (part "TEST-POINT"))
    )
    (comp (ref "TP67")
      (value "TEST-POINT")
      (footprint "eagle-import:2MM-TEST-POINT")
      (libsource (lib "eagle-import") (part "TEST-POINT"))
    )
    (comp (ref "TP68")
      (value "TEST-POINT")
      (footprint "eagle-import:2MM-TEST-POINT")
      (libsource (lib "eagle-import") (part "TEST-POINT"))
    )
    (comp (ref "U12")
      (value "MIC842LYC5")
      (footprint "eagle-import:SC70-5")
      (libsource (lib "eagle-import") (part "MIC842LYC5"))
    )
    (comp (ref "U13")
      (value "MIC842LYC5")
      (footprint "eagle-import:SC70-5")
      (libsource (lib "eagle-import") (part "MIC842LYC5"))
    )
    (comp (ref "U14")
      (value "MAX4211FETE")
      (footprint "eagle-import:QFN65P400X400X80-17T210")
      (fields (field (name "MPN") "MAX4211FETE+"))
      (libsource (lib "eagle-import") (part "MAX4211"))
    )
    (comp (ref "U15")
      (value "TPS62112")
      (footprint "eagle-import:S-PVQFN-16")
      (fields (field (name "MPN") "TPS62112RSAR"))
      (libsource (lib "eagle-import") (part "TPS6211X"))
    )
    (comp (ref "U16")
      (value "MAX7310ATE")
      (footprint "eagle-import:QFN65P400X400X80-17T210")
      (fields
        (field (name "MPN") "MAX7310ATE+")
        (field (name "MFR") "Maxim")
        (field (name "MPN_1") "MAX7310ATE")
      )
      (libsource (lib "eagle-import") (part "MAX7310"))
    )
    (comp (ref "C1")
      (value "10uF")
      (footprint "eagle-import:.0805-B")
      (libsource (lib "eagle-import") (part "C-EU0805-B"))
    )
    (comp (ref "C4")
      (value "0.1uF")
      (footprint "eagle-import:.0603-A")
      (libsource (lib "eagle-import") (part "C-EU0603-A"))
    )
    (comp (ref "C7")
      (value "10uF")
      (footprint "eagle-import:.0805-B")
      (libsource (lib "eagle-import") (part "C-EU0805-B"))
    )
    (comp (ref "C19")
      (value "18pF, 50V")
      (footprint "eagle-import:.0603-A")
      (libsource (lib "eagle-import") (part "C-EU0603-A"))
    )
    (comp (ref "C22")
      (value "18pF, 50V")
      (footprint "eagle-import:.0603-A")
      (libsource (lib "eagle-import") (part "C-EU0603-A"))
    )
    (comp (ref "C29")
      (value "18pF, 50V")
      (footprint "eagle-import:.0603-A")
      (libsource (lib "eagle-import") (part "C-EU0603-A"))
    )
    (comp (ref "C30")
      (value "18pF, 50V")
      (footprint "eagle-import:.0603-A")
      (libsource (lib "eagle-import") (part "C-EU0603-A"))
    )
    (comp (ref "FB1")
      (value "30Ω/1.8A")
      (footprint "eagle-import:0603")
      (fields (field (name "MPN") "BLM18KG300JH1D"))
      (libsource (lib "eagle-import") (part "FERRITE_BEAD-0603"))
    )
    (comp (ref "FB2")
      (value "30Ω/1.8A")
      (footprint "eagle-import:0603")
      (fields (field (name "MPN") "BLM18KG300JH1D"))
      (libsource (lib "eagle-import") (part "FERRITE_BEAD-0603"))
    )
    (comp (ref "J102")
      (value "FTSH-105-XX-X-DV-K")
      (footprint "eagle-import:CON10_2X5_DUK_FTSH")
      (libsource (lib "eagle-import") (part "FTSH-105-XX-X-DV-K"))
    )
    (comp (ref "JP1")
      (value "JUMPER-SMT_2_NO_SILK")
      (footprint "eagle-import:SMT-JUMPER_2_NO_SILK")
      (libsource (lib "eagle-import") (part "JUMPER-SMT_2_NO_SILK"))
    )
    (comp (ref "JP100")
      (value "JUMPER-SMT_2_NC_TRACE_SILK")
      (footprint "eagle-import:SMT-JUMPER_2_NC_TRACE_SILK")
      (libsource (lib "eagle-import") (part "JUMPER-SMT_2_NC_TRACE_SILK"))
    )
    (comp (ref "R6")
      (value "10k")
      (footprint "eagle-import:.0603-A")
      (libsource (lib "eagle-import") (part "R-US_0603-A"))
    )
    (comp (ref "R7")
      (value "10k")
      (footprint "eagle-import:.0603-A")
      (libsource (lib "eagle-import") (part "R-US_0603-A"))
    )
    (comp (ref "R13")
      (value "1M")
      (footprint "eagle-import:.0603-A")
      (libsource (lib "eagle-import") (part "R-US_0603-A"))
    )
    (comp (ref "R19")
      (value "10k")
      (footprint "eagle-import:.0603-A")
      (libsource (lib "eagle-import") (part "R-US_0603-A"))
    )
    (comp (ref "R20")
      (value "10k")
      (footprint "eagle-import:.0603-A")
      (libsource (lib "eagle-import") (part "R-US_0603-A"))
    )
    (comp (ref "R22")
      (value "10k")
      (footprint "eagle-import:.0603-A")
      (libsource (lib "eagle-import") (part "R-US_0603-A"))
    )
    (comp (ref "R27")
      (value "DNP")
      (footprint "eagle-import:.0603-A")
      (libsource (lib "eagle-import") (part "R-US_0603-A"))
    )
    (comp (ref "TP1")
      (value "TEST-POINT3X4")
      (footprint "eagle-import:PAD.03X.04")
      (libsource (lib "eagle-import") (part "TEST-POINT3X4"))
    )
    (comp (ref "TP31")
      (value "TEST-POINT3X4")
      (footprint "eagle-import:PAD.03X.04")
      (libsource (lib "eagle-import") (part "TEST-POINT3X4"))
    )
    (comp (ref "TP38")
      (value "TEST-POINT3X4")
      (footprint "eagle-import:PAD.03X.04")
      (libsource (lib "eagle-import") (part "TEST-POINT3X4"))
    )
    (comp (ref "TP39")
      (value "TEST-POINT3X4")
      (footprint "eagle-import:PAD.03X.04")
      (libsource (lib "eagle-import") (part "TEST-POINT3X4"))
    )
    (comp (ref "TP133")
      (value "TEST-POINT3X4")
      (footprint "eagle-import:PAD.03X.04")
      (libsource (lib "eagle-import") (part "TEST-POINT3X4"))
    )
    (comp (ref "TP138")
      (value "TEST-POINT3X4")
      (footprint "eagle-import:PAD.03X.04")
      (libsource (lib "eagle-import") (part "TEST-POINT3X4"))
    )
    (comp (ref "TP139")
      (value "TEST-POINT3X4")
      (footprint "eagle-import:PAD.03X.04")
      (libsource (lib "eagle-import") (part "TEST-POINT3X4"))
    )
    (comp (ref "TP141")
      (value "TEST-POINT3X4")
      (footprint "eagle-import:PAD.03X.04")
      (libsource (lib "eagle-import") (part "TEST-POINT3X4"))
    )
    (comp (ref "TP144")
      (value "TEST-POINT3X4")
      (footprint "eagle-import:PAD.03X.04")
      (libsource (lib "eagle-import") (part "TEST-POINT3X4"))
    )
    (comp (ref "TP168")
      (value "TEST-POINT3X4")
      (footprint "eagle-import:PAD.03X.04")
      (libsource (lib "eagle-import") (part "TEST-POINT3X4"))
    )
    (comp (ref "TP169")
      (value "TEST-POINT3X4")
      (footprint "eagle-import:PAD.03X.04")
      (libsource (lib "eagle-import") (part "TEST-POINT3X4"))
    )
    (comp (ref "TP170")
      (value "TEST-POINT3X4")
      (footprint "eagle-import:PAD.03X.04")
      (libsource (lib "eagle-import") (part "TEST-POINT3X4"))
    )
    (comp (ref "TP171")
      (value "TEST-POINT3X4")
      (footprint "eagle-import:PAD.03X.04")
      (libsource (lib "eagle-import") (part "TEST-POINT3X4"))
    )
    (comp (ref "TP175")
      (value "TEST-POINT3X4")
      (footprint "eagle-import:PAD.03X.04")
      (libsource (lib "eagle-import") (part "TEST-POINT3X4"))
    )
    (comp (ref "TP176")
      (value "TEST-POINT3X4")
      (footprint "eagle-import:PAD.03X.04")
      (libsource (lib "eagle-import") (part "TEST-POINT3X4"))
    )
    (comp (ref "TP179")
      (value "TEST-POINT3X4")
      (footprint "eagle-import:PAD.03X.04")
      (libsource (lib "eagle-import") (part "TEST-POINT3X4"))
    )
    (comp (ref "TP181")
      (value "TEST-POINT3X4")
      (footprint "eagle-import:PAD.03X.04")
      (libsource (lib "eagle-import") (part "TEST-POINT3X4"))
    )
    (comp (ref "TP182")
      (value "TEST-POINT3X4")
      (footprint "eagle-import:PAD.03X.04")
      (libsource (lib "eagle-import") (part "TEST-POINT3X4"))
    )
    (comp (ref "U1")
      (value "RCLAMP0504FB")
      (footprint "eagle-import:SC70-6")
      (fields (field (name "MPN") "RCLAMP0504FBTCT"))
      (libsource (lib "eagle-import") (part "RCLAMP0504FB"))
    )
    (comp (ref "U2")
      (value "TPS2051CDBVR")
      (footprint "eagle-import:DBV5")
      (fields (field (name "MFR") "Texas Instruments"))
      (libsource (lib "eagle-import") (part "TPS2051CDBVR"))
    )
    (comp (ref "U7")
      (value "OSD3358-512M-BSM")
      (footprint "eagle-import:OSD335X-BGA-256")
      (fields (field (name "MFR") "Octavo Systems"))
      (libsource (lib "eagle-import") (part "OSD3358-512M-BSM"))
    )
    (comp (ref "Y1")
      (value "24MHz")
      (footprint "eagle-import:5X3.2-4SMD")
      (fields (field (name "MPN") "ECS-240-12-30BQ-AEN-TR"))
      (libsource (lib "eagle-import") (part "ECS-240-12-30BQ-AEN-TR"))
    )
    (comp (ref "Y2")
      (value "ABS07-32.768KHZ-T")
      (footprint "eagle-import:CRYSTAL_3.2X1.5")
      (libsource (lib "eagle-import") (part "ABS07-32.768KHZ-T"))
    )
    (comp (ref "C13")
      (value "22uF")
      (footprint "eagle-import:C1210")
      (libsource (lib "eagle-import") (part "C-EUC1210"))
    )
    (comp (ref "C14")
      (value "22uF")
      (footprint "eagle-import:C1210")
      (libsource (lib "eagle-import") (part "C-EUC1210"))
    )
    (comp (ref "C15")
      (value "22uF")
      (footprint "eagle-import:C1210")
      (libsource (lib "eagle-import") (part "C-EUC1210"))
    )
    (comp (ref "C18")
      (value "0.1uF")
      (footprint "eagle-import:.0603-A")
      (libsource (lib "eagle-import") (part "C-EU0603-A"))
    )
    (comp (ref "C41")
      (value "0.1uF")
      (footprint "eagle-import:.0603-A")
      (libsource (lib "eagle-import") (part "C-EU0603-A"))
    )
    (comp (ref "D1")
      (value "GREEN")
      (footprint "eagle-import:LED-0603")
      (libsource (lib "eagle-import") (part "LED-GREEN0603"))
    )
    (comp (ref "JP101")
      (value "JUMPER-SMT_2_NC_TRACE_SILK")
      (footprint "eagle-import:SMT-JUMPER_2_NC_TRACE_SILK")
      (libsource (lib "eagle-import") (part "JUMPER-SMT_2_NC_TRACE_SILK"))
    )
    (comp (ref "JP104")
      (value "JUMPER-SMT_2_NC_TRACE_SILK")
      (footprint "eagle-import:SMT-JUMPER_2_NC_TRACE_SILK")
      (libsource (lib "eagle-import") (part "JUMPER-SMT_2_NC_TRACE_SILK"))
    )
    (comp (ref "Q1")
      (value "MMBT2907")
      (footprint "eagle-import:SOT23-BEC")
      (fields (field (name "MPN") "MMBT2907A-7-F"))
      (libsource (lib "eagle-import") (part "MMBT2907SMD"))
    )
    (comp (ref "R1")
      (value "1k")
      (footprint "eagle-import:.0603-A")
      (libsource (lib "eagle-import") (part "R-US_0603-A"))
    )
    (comp (ref "R15")
      (value "10k")
      (footprint "eagle-import:.0603-A")
      (libsource (lib "eagle-import") (part "R-US_0603-A"))
    )
    (comp (ref "R23")
      (value "499")
      (footprint "eagle-import:.0603-A")
      (libsource (lib "eagle-import") (part "R-US_0603-A"))
    )
    (comp (ref "R28")
      (value "10k")
      (footprint "eagle-import:.0603-A")
      (libsource (lib "eagle-import") (part "R-US_0603-A"))
    )
    (comp (ref "R31")
      (value "40.2K")
      (footprint "eagle-import:.0603-A")
      (libsource (lib "eagle-import") (part "R-US_0603-A"))
    )
    (comp (ref "R73")
      (value "100")
      (footprint "eagle-import:.0603-A")
      (libsource (lib "eagle-import") (part "R-US_0603-A"))
    )
    (comp (ref "R74")
      (value "100")
      (footprint "eagle-import:.0603-A")
      (libsource (lib "eagle-import") (part "R-US_0603-A"))
    )
    (comp (ref "R75")
      (value "100")
      (footprint "eagle-import:.0603-A")
      (libsource (lib "eagle-import") (part "R-US_0603-A"))
    )
    (comp (ref "TP2")
      (value "TEST-POINT3X4")
      (footprint "eagle-import:PAD.03X.04")
      (libsource (lib "eagle-import") (part "TEST-POINT3X4"))
    )
    (comp (ref "TP3")
      (value "TEST-POINT3X4")
      (footprint "eagle-import:PAD.03X.04")
      (libsource (lib "eagle-import") (part "TEST-POINT3X4"))
    )
    (comp (ref "TP4")
      (value "TEST-POINT3X4")
      (footprint "eagle-import:PAD.03X.04")
      (libsource (lib "eagle-import") (part "TEST-POINT3X4"))
    )
    (comp (ref "TP14")
      (value "TEST-POINT3X4")
      (footprint "eagle-import:PAD.03X.04")
      (libsource (lib "eagle-import") (part "TEST-POINT3X4"))
    )
    (comp (ref "TP25")
      (value "TEST-POINT3X4")
      (footprint "eagle-import:PAD.03X.04")
      (libsource (lib "eagle-import") (part "TEST-POINT3X4"))
    )
    (comp (ref "TP102")
      (value "TEST-POINT3X4")
      (footprint "eagle-import:PAD.03X.04")
      (libsource (lib "eagle-import") (part "TEST-POINT3X4"))
    )
    (comp (ref "TP109")
      (value "TEST-POINT3X4")
      (footprint "eagle-import:PAD.03X.04")
      (libsource (lib "eagle-import") (part "TEST-POINT3X4"))
    )
    (comp (ref "TP110")
      (value "TEST-POINT3X4")
      (footprint "eagle-import:PAD.03X.04")
      (libsource (lib "eagle-import") (part "TEST-POINT3X4"))
    )
    (comp (ref "TP112")
      (value "TEST-POINT3X4")
      (footprint "eagle-import:PAD.03X.04")
      (libsource (lib "eagle-import") (part "TEST-POINT3X4"))
    )
    (comp (ref "TP121")
      (value "TEST-POINT3X4")
      (footprint "eagle-import:PAD.03X.04")
      (libsource (lib "eagle-import") (part "TEST-POINT3X4"))
    )
    (comp (ref "TP129")
      (value "TEST-POINT3X4")
      (footprint "eagle-import:PAD.03X.04")
      (libsource (lib "eagle-import") (part "TEST-POINT3X4"))
    )
    (comp (ref "TP130")
      (value "TEST-POINT3X4")
      (footprint "eagle-import:PAD.03X.04")
      (libsource (lib "eagle-import") (part "TEST-POINT3X4"))
    )
    (comp (ref "TP132")
      (value "TEST-POINT3X4")
      (footprint "eagle-import:PAD.03X.04")
      (libsource (lib "eagle-import") (part "TEST-POINT3X4"))
    )
    (comp (ref "TP136")
      (value "TEST-POINT3X4")
      (footprint "eagle-import:PAD.03X.04")
      (libsource (lib "eagle-import") (part "TEST-POINT3X4"))
    )
    (comp (ref "TP140")
      (value "TEST-POINT3X4")
      (footprint "eagle-import:PAD.03X.04")
      (libsource (lib "eagle-import") (part "TEST-POINT3X4"))
    )
    (comp (ref "TP145")
      (value "TEST-POINT3X4")
      (footprint "eagle-import:PAD.03X.04")
      (libsource (lib "eagle-import") (part "TEST-POINT3X4"))
    )
    (comp (ref "TP150")
      (value "TEST-POINT3X4")
      (footprint "eagle-import:PAD.03X.04")
      (libsource (lib "eagle-import") (part "TEST-POINT3X4"))
    )
    (comp (ref "TP151")
      (value "TEST-POINT3X4")
      (footprint "eagle-import:PAD.03X.04")
      (libsource (lib "eagle-import") (part "TEST-POINT3X4"))
    )
    (comp (ref "TP154")
      (value "TEST-POINT3X4")
      (footprint "eagle-import:PAD.03X.04")
      (libsource (lib "eagle-import") (part "TEST-POINT3X4"))
    )
    (comp (ref "TP155")
      (value "TEST-POINT3X4")
      (footprint "eagle-import:PAD.03X.04")
      (libsource (lib "eagle-import") (part "TEST-POINT3X4"))
    )
    (comp (ref "TP156")
      (value "TEST-POINT3X4")
      (footprint "eagle-import:PAD.03X.04")
      (libsource (lib "eagle-import") (part "TEST-POINT3X4"))
    )
    (comp (ref "TP157")
      (value "TEST-POINT3X4")
      (footprint "eagle-import:PAD.03X.04")
      (libsource (lib "eagle-import") (part "TEST-POINT3X4"))
    )
    (comp (ref "TP160")
      (value "TEST-POINT3X4")
      (footprint "eagle-import:PAD.03X.04")
      (libsource (lib "eagle-import") (part "TEST-POINT3X4"))
    )
    (comp (ref "TP161")
      (value "TEST-POINT3X4")
      (footprint "eagle-import:PAD.03X.04")
      (libsource (lib "eagle-import") (part "TEST-POINT3X4"))
    )
    (comp (ref "TP163")
      (value "TEST-POINT3X4")
      (footprint "eagle-import:PAD.03X.04")
      (libsource (lib "eagle-import") (part "TEST-POINT3X4"))
    )
    (comp (ref "TP164")
      (value "TEST-POINT3X4")
      (footprint "eagle-import:PAD.03X.04")
      (libsource (lib "eagle-import") (part "TEST-POINT3X4"))
    )
    (comp (ref "TP165")
      (value "TEST-POINT3X4")
      (footprint "eagle-import:PAD.03X.04")
      (libsource (lib "eagle-import") (part "TEST-POINT3X4"))
    )
    (comp (ref "TP166")
      (value "TEST-POINT3X4")
      (footprint "eagle-import:PAD.03X.04")
      (libsource (lib "eagle-import") (part "TEST-POINT3X4"))
    )
    (comp (ref "TP167")
      (value "TEST-POINT3X4")
      (footprint "eagle-import:PAD.03X.04")
      (libsource (lib "eagle-import") (part "TEST-POINT3X4"))
    )
    (comp (ref "TP172")
      (value "TEST-POINT3X4")
      (footprint "eagle-import:PAD.03X.04")
      (libsource (lib "eagle-import") (part "TEST-POINT3X4"))
    )
    (comp (ref "TP173")
      (value "TEST-POINT3X4")
      (footprint "eagle-import:PAD.03X.04")
      (libsource (lib "eagle-import") (part "TEST-POINT3X4"))
    )
    (comp (ref "U4")
      (value "SN74LVC1G07DCK")
      (footprint "eagle-import:C70(TI-DCK)")
      (fields (field (name "MPN") "SN74LVC1G07DCKR"))
      (libsource (lib "eagle-import") (part "SN74LVC1G07DCK"))
    )
    (comp (ref "U10")
      (value "TLVH431")
      (footprint "eagle-import:SOT23-3")
      (fields (field (name "MPN") "TLVH431BQDBZRQ1"))
      (libsource (lib "eagle-import") (part "TLVH431"))
    )
    (comp (ref "U18")
      (value "RCLAMP0504FB")
      (footprint "eagle-import:SC70-6")
      (fields (field (name "MPN") "RCLAMP0504FBTCT"))
      (libsource (lib "eagle-import") (part "RCLAMP0504FB"))
    )
    (comp (ref "J1")
      (value "ORESAT-DEBUG-CONNECTOR-CARD")
      (footprint "eagle-import:TE_2-1734592-0")
      (fields (field (name "MPN") "2-1734592-0"))
      (libsource (lib "eagle-import") (part "ORESAT-DEBUG-CONNECTOR-CARD"))
    )
    (comp (ref "J4")
      (value "TFM-120-01-L-D-RA")
      (footprint "eagle-import:J-SAMTEC-TFM-120-X1-XXX-D-RA")
      (libsource (lib "eagle-import") (part "J-SAMTEC-TFM-120-X1-XXX-D-RA"))
    )
    (comp (ref "PCB1")
      (value "ORESAT-CARD-V1.3-STAR-TRACKER")
      (footprint "eagle-import:ORESAT-CARD-V1.3-STAR-TRACKER")
      (libsource (lib "eagle-import") (part "ORESAT-CARD-V1.3-STAR-TRACKER"))
    )
    (comp (ref "TP58")
      (value "TEST-POINT3X4")
      (footprint "eagle-import:PAD.03X.04")
      (libsource (lib "eagle-import") (part "TEST-POINT3X4"))
    )
    (comp (ref "TP59")
      (value "TEST-POINT3X4")
      (footprint "eagle-import:PAD.03X.04")
      (libsource (lib "eagle-import") (part "TEST-POINT3X4"))
    )
    (comp (ref "TP60")
      (value "TEST-POINT3X4")
      (footprint "eagle-import:PAD.03X.04")
      (libsource (lib "eagle-import") (part "TEST-POINT3X4"))
    )
    (comp (ref "TP61")
      (value "TEST-POINT3X4")
      (footprint "eagle-import:PAD.03X.04")
      (libsource (lib "eagle-import") (part "TEST-POINT3X4"))
    )
    (comp (ref "TP62")
      (value "TEST-POINT3X4")
      (footprint "eagle-import:PAD.03X.04")
      (libsource (lib "eagle-import") (part "TEST-POINT3X4"))
    )
    (comp (ref "TP183")
      (value "TEST-POINT3X4")
      (footprint "eagle-import:PAD.03X.04")
      (libsource (lib "eagle-import") (part "TEST-POINT3X4"))
    )
    (comp (ref "TP184")
      (value "TEST-POINT3X4")
      (footprint "eagle-import:PAD.03X.04")
      (libsource (lib "eagle-import") (part "TEST-POINT3X4"))
    )
    (comp (ref "C2")
      (value "10uF")
      (footprint "eagle-import:.0805-B")
      (libsource (lib "eagle-import") (part "C-EU0805-B"))
    )
    (comp (ref "C3")
      (value "1uF")
      (footprint "eagle-import:.0603-A")
      (libsource (lib "eagle-import") (part "C-EU0603-A"))
    )
    (comp (ref "C5")
      (value "1uF")
      (footprint "eagle-import:.0603-A")
      (libsource (lib "eagle-import") (part "C-EU0603-A"))
    )
    (comp (ref "C6")
      (value "1uF")
      (footprint "eagle-import:.0603-A")
      (libsource (lib "eagle-import") (part "C-EU0603-A"))
    )
    (comp (ref "C8")
      (value "10uF")
      (footprint "eagle-import:.0805-B")
      (libsource (lib "eagle-import") (part "C-EU0805-B"))
    )
    (comp (ref "C9")
      (value "1uF")
      (footprint "eagle-import:.0603-A")
      (libsource (lib "eagle-import") (part "C-EU0603-A"))
    )
    (comp (ref "C10")
      (value "1uF")
      (footprint "eagle-import:.0603-A")
      (libsource (lib "eagle-import") (part "C-EU0603-A"))
    )
    (comp (ref "C11")
      (value "0.1uF")
      (footprint "eagle-import:.0603-A")
      (libsource (lib "eagle-import") (part "C-EU0603-A"))
    )
    (comp (ref "C12")
      (value "1uF")
      (footprint "eagle-import:.0603-A")
      (libsource (lib "eagle-import") (part "C-EU0603-A"))
    )
    (comp (ref "C16")
      (value "0.1uF")
      (footprint "eagle-import:.0603-A")
      (libsource (lib "eagle-import") (part "C-EU0603-A"))
    )
    (comp (ref "C17")
      (value "0.1uF")
      (footprint "eagle-import:.0603-A")
      (libsource (lib "eagle-import") (part "C-EU0603-A"))
    )
    (comp (ref "C20")
      (value "0.1uF")
      (footprint "eagle-import:.0603-A")
      (libsource (lib "eagle-import") (part "C-EU0603-A"))
    )
    (comp (ref "C21")
      (value "0.1uF")
      (footprint "eagle-import:.0603-A")
      (libsource (lib "eagle-import") (part "C-EU0603-A"))
    )
    (comp (ref "C23")
      (value "1uF")
      (footprint "eagle-import:.0603-A")
      (libsource (lib "eagle-import") (part "C-EU0603-A"))
    )
    (comp (ref "C24")
      (value "0.1uF")
      (footprint "eagle-import:.0603-A")
      (libsource (lib "eagle-import") (part "C-EU0603-A"))
    )
    (comp (ref "C25")
      (value "0.1uF")
      (footprint "eagle-import:.0603-A")
      (libsource (lib "eagle-import") (part "C-EU0603-A"))
    )
    (comp (ref "C26")
      (value "0.1uF")
      (footprint "eagle-import:.0603-A")
      (libsource (lib "eagle-import") (part "C-EU0603-A"))
    )
    (comp (ref "C27")
      (value "1uF")
      (footprint "eagle-import:.0603-A")
      (libsource (lib "eagle-import") (part "C-EU0603-A"))
    )
    (comp (ref "C28")
      (value "0.1uF")
      (footprint "eagle-import:.0603-A")
      (libsource (lib "eagle-import") (part "C-EU0603-A"))
    )
    (comp (ref "C31")
      (value "0.1uF")
      (footprint "eagle-import:.0603-A")
      (libsource (lib "eagle-import") (part "C-EU0603-A"))
    )
    (comp (ref "C40")
      (value "0.1uF")
      (footprint "eagle-import:.0603-A")
      (libsource (lib "eagle-import") (part "C-EU0603-A"))
    )
    (comp (ref "C42")
      (value "22uF")
      (footprint "eagle-import:C1210")
      (libsource (lib "eagle-import") (part "C-EUC1210"))
    )
    (comp (ref "C43")
      (value "22uF")
      (footprint "eagle-import:C1210")
      (libsource (lib "eagle-import") (part "C-EUC1210"))
    )
    (comp (ref "D2")
      (value "BLUE")
      (footprint "eagle-import:LED-0603")
      (libsource (lib "eagle-import") (part "LED-BLUE0603"))
    )
    (comp (ref "D3")
      (value "BLUE")
      (footprint "eagle-import:LED-0603")
      (libsource (lib "eagle-import") (part "LED-BLUE0603"))
    )
    (comp (ref "D4")
      (value "BLUE")
      (footprint "eagle-import:LED-0603")
      (libsource (lib "eagle-import") (part "LED-BLUE0603"))
    )
    (comp (ref "D5")
      (value "BLUE")
      (footprint "eagle-import:LED-0603")
      (libsource (lib "eagle-import") (part "LED-BLUE0603"))
    )
    (comp (ref "J3")
      (value "CONN_03LONGPADS")
      (footprint "eagle-import:1X03_LONGPADS")
      (libsource (lib "eagle-import") (part "CONN_03LONGPADS"))
    )
    (comp (ref "J100")
      (value "DM3BT-DSF-PEJS")
      (footprint "eagle-import:DM3BT-DSF-PEJS")
      (libsource (lib "eagle-import") (part "DM3BT-DSF-PEJS"))
    )
    (comp (ref "J101")
      (value "3-1734592-64-1734592-0")
      (footprint "eagle-import:TE_3-1734592-6")
      (fields (field (name "MPN") "3-1734592-6"))
      (libsource (lib "eagle-import") (part "3-1734592-64-1734592-0"))
    )
    (comp (ref "JP102")
      (value "JUMPER-SMT_3_1-NC_TRACE_SILK")
      (footprint "eagle-import:SMT-JUMPER_3_1-NC_TRACE_SILK")
      (libsource (lib "eagle-import") (part "JUMPER-SMT_3_1-NC_TRACE_SILK"))
    )
    (comp (ref "JP103")
      (value "JUMPER-SMT_3_1-NC_TRACE_SILK")
      (footprint "eagle-import:SMT-JUMPER_3_1-NC_TRACE_SILK")
      (libsource (lib "eagle-import") (part "JUMPER-SMT_3_1-NC_TRACE_SILK"))
    )
    (comp (ref "JP105")
      (value "JUMPER-SMT_3_1-NC_TRACE_SILK")
      (footprint "eagle-import:SMT-JUMPER_3_1-NC_TRACE_SILK")
      (libsource (lib "eagle-import") (part "JUMPER-SMT_3_1-NC_TRACE_SILK"))
    )
    (comp (ref "JP106")
      (value "JUMPER-SMT_3_1-NC_TRACE_SILK")
      (footprint "eagle-import:SMT-JUMPER_3_1-NC_TRACE_SILK")
      (libsource (lib "eagle-import") (part "JUMPER-SMT_3_1-NC_TRACE_SILK"))
    )
    (comp (ref "JP107")
      (value "JUMPER-SMT_3_NO_SILK")
      (footprint "eagle-import:SMT-JUMPER_3_NO_SILK")
      (libsource (lib "eagle-import") (part "JUMPER-SMT_3_NO_SILK"))
    )
    (comp (ref "JP108")
      (value "JUMPER-SMT_3_1-NC_TRACE_SILK")
      (footprint "eagle-import:SMT-JUMPER_3_1-NC_TRACE_SILK")
      (libsource (lib "eagle-import") (part "JUMPER-SMT_3_1-NC_TRACE_SILK"))
    )
    (comp (ref "JP109")
      (value "JUMPER-SMT_3_1-NC_TRACE_SILK")
      (footprint "eagle-import:SMT-JUMPER_3_1-NC_TRACE_SILK")
      (libsource (lib "eagle-import") (part "JUMPER-SMT_3_1-NC_TRACE_SILK"))
    )
    (comp (ref "JP110")
      (value "JUMPER-SMT_3_1-NC_TRACE_SILK")
      (footprint "eagle-import:SMT-JUMPER_3_1-NC_TRACE_SILK")
      (libsource (lib "eagle-import") (part "JUMPER-SMT_3_1-NC_TRACE_SILK"))
    )
    (comp (ref "JP111")
      (value "JUMPER-SMT_3_1-NC_TRACE_SILK")
      (footprint "eagle-import:SMT-JUMPER_3_1-NC_TRACE_SILK")
      (libsource (lib "eagle-import") (part "JUMPER-SMT_3_1-NC_TRACE_SILK"))
    )
    (comp (ref "R2")
      (value "1k")
      (footprint "eagle-import:.0603-A")
      (libsource (lib "eagle-import") (part "R-US_0603-A"))
    )
    (comp (ref "R3")
      (value "1k")
      (footprint "eagle-import:.0603-A")
      (libsource (lib "eagle-import") (part "R-US_0603-A"))
    )
    (comp (ref "R4")
      (value "1k")
      (footprint "eagle-import:.0603-A")
      (libsource (lib "eagle-import") (part "R-US_0603-A"))
    )
    (comp (ref "R5")
      (value "1k")
      (footprint "eagle-import:.0603-A")
      (libsource (lib "eagle-import") (part "R-US_0603-A"))
    )
    (comp (ref "R8")
      (value "10K")
      (footprint "eagle-import:ARRAY_EXBA-M")
      (fields
        (field (name "MFR") "Panasonic Electronic Components")
        (field (name "MPN") "EXB-A10PXXXJ")
        (field (name "MPN_1") "EXB-A10P103J")
      )
      (libsource (lib "eagle-import") (part "EXB-A10P391JC_ARRAY_EXBA-M"))
    )
    (comp (ref "R9")
      (value "10K")
      (footprint "eagle-import:ARRAY_EXBA-M")
      (fields
        (field (name "MFR") "Panasonic Electronic Components")
        (field (name "MPN") "EXB-A10PXXXJ")
        (field (name "MPN_1") "EXB-A10P103J")
      )
      (libsource (lib "eagle-import") (part "EXB-A10P391JC_ARRAY_EXBA-M"))
    )
    (comp (ref "R10")
      (value "10K")
      (footprint "eagle-import:ARRAY_EXBA-M")
      (fields
        (field (name "MFR") "Panasonic Electronic Components")
        (field (name "MPN") "EXB-A10PXXXJ")
        (field (name "DPN") "U7103CT-ND")
        (field (name "MPN_1") "EXB-A10P103J")
      )
      (libsource (lib "eagle-import") (part "EXB-A10P391JC_ARRAY_EXBA-M"))
    )
    (comp (ref "R11")
      (value "10k")
      (footprint "eagle-import:.0603-A")
      (libsource (lib "eagle-import") (part "R-US_0603-A"))
    )
    (comp (ref "R12")
      (value "10k")
      (footprint "eagle-import:.0603-A")
      (libsource (lib "eagle-import") (part "R-US_0603-A"))
    )
    (comp (ref "R14")
      (value "10k")
      (footprint "eagle-import:.0603-A")
      (libsource (lib "eagle-import") (part "R-US_0603-A"))
    )
    (comp (ref "R16")
      (value "10k")
      (footprint "eagle-import:.0603-A")
      (libsource (lib "eagle-import") (part "R-US_0603-A"))
    )
    (comp (ref "R17")
      (value "4.7k")
      (footprint "eagle-import:.0603-A")
      (libsource (lib "eagle-import") (part "R-US_0603-A"))
    )
    (comp (ref "R18")
      (value "4.7k")
      (footprint "eagle-import:.0603-A")
      (libsource (lib "eagle-import") (part "R-US_0603-A"))
    )
    (comp (ref "R21")
      (value "10k")
      (footprint "eagle-import:.0603-A")
      (libsource (lib "eagle-import") (part "R-US_0603-A"))
    )
    (comp (ref "R24")
      (value "100K")
      (footprint "eagle-import:ARRAY_EXBA-M")
      (fields
        (field (name "MFR") "Panasonic Electronic Components")
        (field (name "MPN") "EXB-A10PXXXJ")
        (field (name "MPN_1") "EXB-A10P104J")
      )
      (libsource (lib "eagle-import") (part "EXB-A10P391JC_ARRAY_EXBA-M"))
    )
    (comp (ref "R25")
      (value "100K")
      (footprint "eagle-import:ARRAY_EXBA-M")
      (fields
        (field (name "MFR") "Panasonic Electronic Components")
        (field (name "MPN") "EXB-A10PXXXJ")
        (field (name "MPN_1") "EXB-A10P104J")
      )
      (libsource (lib "eagle-import") (part "EXB-A10P391JC_ARRAY_EXBA-M"))
    )
    (comp (ref "R26")
      (value "100K")
      (footprint "eagle-import:ARRAY_EXBA-M")
      (fields
        (field (name "MFR") "Panasonic Electronic Components")
        (field (name "MPN") "EXB-A10PXXXJ")
        (field (name "MPN_1") "EXB-A10P104J")
      )
      (libsource (lib "eagle-import") (part "EXB-A10P391JC_ARRAY_EXBA-M"))
    )
    (comp (ref "R29")
      (value "4.7k")
      (footprint "eagle-import:.0603-A")
      (libsource (lib "eagle-import") (part "R-US_0603-A"))
    )
    (comp (ref "R30")
      (value "4.7k")
      (footprint "eagle-import:.0603-A")
      (libsource (lib "eagle-import") (part "R-US_0603-A"))
    )
    (comp (ref "R59")
      (value "DNP")
      (footprint "eagle-import:.0603-A")
      (libsource (lib "eagle-import") (part "R-US_0603-A"))
    )
    (comp (ref "R60")
      (value "DNP")
      (footprint "eagle-import:.0603-A")
      (libsource (lib "eagle-import") (part "R-US_0603-A"))
    )
    (comp (ref "TP5")
      (value "TEST-POINT3X4")
      (footprint "eagle-import:PAD.03X.04")
      (libsource (lib "eagle-import") (part "TEST-POINT3X4"))
    )
    (comp (ref "TP6")
      (value "TEST-POINT3X4")
      (footprint "eagle-import:PAD.03X.04")
      (libsource (lib "eagle-import") (part "TEST-POINT3X4"))
    )
    (comp (ref "TP7")
      (value "TEST-POINT3X4")
      (footprint "eagle-import:PAD.03X.04")
      (libsource (lib "eagle-import") (part "TEST-POINT3X4"))
    )
    (comp (ref "TP8")
      (value "TEST-POINT3X4")
      (footprint "eagle-import:PAD.03X.04")
      (libsource (lib "eagle-import") (part "TEST-POINT3X4"))
    )
    (comp (ref "TP9")
      (value "TEST-POINT3X4")
      (footprint "eagle-import:PAD.03X.04")
      (libsource (lib "eagle-import") (part "TEST-POINT3X4"))
    )
    (comp (ref "TP10")
      (value "TEST-POINT3X4")
      (footprint "eagle-import:PAD.03X.04")
      (libsource (lib "eagle-import") (part "TEST-POINT3X4"))
    )
    (comp (ref "TP11")
      (value "TEST-POINT3X4")
      (footprint "eagle-import:PAD.03X.04")
      (libsource (lib "eagle-import") (part "TEST-POINT3X4"))
    )
    (comp (ref "TP12")
      (value "TEST-POINT3X4")
      (footprint "eagle-import:PAD.03X.04")
      (libsource (lib "eagle-import") (part "TEST-POINT3X4"))
    )
    (comp (ref "TP13")
      (value "TEST-POINT3X4")
      (footprint "eagle-import:PAD.03X.04")
      (libsource (lib "eagle-import") (part "TEST-POINT3X4"))
    )
    (comp (ref "TP15")
      (value "TEST-POINT3X4")
      (footprint "eagle-import:PAD.03X.04")
      (libsource (lib "eagle-import") (part "TEST-POINT3X4"))
    )
    (comp (ref "TP16")
      (value "TEST-POINT3X4")
      (footprint "eagle-import:PAD.03X.04")
      (libsource (lib "eagle-import") (part "TEST-POINT3X4"))
    )
    (comp (ref "TP17")
      (value "TEST-POINT3X4")
      (footprint "eagle-import:PAD.03X.04")
      (libsource (lib "eagle-import") (part "TEST-POINT3X4"))
    )
    (comp (ref "TP18")
      (value "TEST-POINT3X4")
      (footprint "eagle-import:PAD.03X.04")
      (libsource (lib "eagle-import") (part "TEST-POINT3X4"))
    )
    (comp (ref "TP19")
      (value "TEST-POINT3X4")
      (footprint "eagle-import:PAD.03X.04")
      (libsource (lib "eagle-import") (part "TEST-POINT3X4"))
    )
    (comp (ref "TP20")
      (value "TEST-POINT3X4")
      (footprint "eagle-import:PAD.03X.04")
      (libsource (lib "eagle-import") (part "TEST-POINT3X4"))
    )
    (comp (ref "TP21")
      (value "TEST-POINT3X4")
      (footprint "eagle-import:PAD.03X.04")
      (libsource (lib "eagle-import") (part "TEST-POINT3X4"))
    )
    (comp (ref "TP22")
      (value "TEST-POINT3X4")
      (footprint "eagle-import:PAD.03X.04")
      (libsource (lib "eagle-import") (part "TEST-POINT3X4"))
    )
    (comp (ref "TP23")
      (value "TEST-POINT3X4")
      (footprint "eagle-import:PAD.03X.04")
      (libsource (lib "eagle-import") (part "TEST-POINT3X4"))
    )
    (comp (ref "TP24")
      (value "TEST-POINT3X4")
      (footprint "eagle-import:PAD.03X.04")
      (libsource (lib "eagle-import") (part "TEST-POINT3X4"))
    )
    (comp (ref "TP26")
      (value "TEST-POINT3X4")
      (footprint "eagle-import:PAD.03X.04")
      (libsource (lib "eagle-import") (part "TEST-POINT3X4"))
    )
    (comp (ref "TP27")
      (value "TEST-POINT3X4")
      (footprint "eagle-import:PAD.03X.04")
      (libsource (lib "eagle-import") (part "TEST-POINT3X4"))
    )
    (comp (ref "TP28")
      (value "TEST-POINT3X4")
      (footprint "eagle-import:PAD.03X.04")
      (libsource (lib "eagle-import") (part "TEST-POINT3X4"))
    )
    (comp (ref "TP29")
      (value "TEST-POINT3X4")
      (footprint "eagle-import:PAD.03X.04")
      (libsource (lib "eagle-import") (part "TEST-POINT3X4"))
    )
    (comp (ref "TP30")
      (value "TEST-POINT3X4")
      (footprint "eagle-import:PAD.03X.04")
      (libsource (lib "eagle-import") (part "TEST-POINT3X4"))
    )
    (comp (ref "TP35")
      (value "TEST-POINT3X4")
      (footprint "eagle-import:PAD.03X.04")
      (libsource (lib "eagle-import") (part "TEST-POINT3X4"))
    )
    (comp (ref "TP36")
      (value "TEST-POINT3X4")
      (footprint "eagle-import:PAD.03X.04")
      (libsource (lib "eagle-import") (part "TEST-POINT3X4"))
    )
    (comp (ref "TP37")
      (value "TEST-POINT3X4")
      (footprint "eagle-import:PAD.03X.04")
      (libsource (lib "eagle-import") (part "TEST-POINT3X4"))
    )
    (comp (ref "TP40")
      (value "TEST-POINT3X4")
      (footprint "eagle-import:PAD.03X.04")
      (libsource (lib "eagle-import") (part "TEST-POINT3X4"))
    )
    (comp (ref "TP69")
      (value "TEST-POINT3X4")
      (footprint "eagle-import:PAD.03X.04")
      (libsource (lib "eagle-import") (part "TEST-POINT3X4"))
    )
    (comp (ref "TP100")
      (value "TEST-POINT3X4")
      (footprint "eagle-import:PAD.03X.04")
      (libsource (lib "eagle-import") (part "TEST-POINT3X4"))
    )
    (comp (ref "TP101")
      (value "TEST-POINT3X4")
      (footprint "eagle-import:PAD.03X.04")
      (libsource (lib "eagle-import") (part "TEST-POINT3X4"))
    )
    (comp (ref "TP103")
      (value "TEST-POINT3X4")
      (footprint "eagle-import:PAD.03X.04")
      (libsource (lib "eagle-import") (part "TEST-POINT3X4"))
    )
    (comp (ref "TP104")
      (value "TEST-POINT3X4")
      (footprint "eagle-import:PAD.03X.04")
      (libsource (lib "eagle-import") (part "TEST-POINT3X4"))
    )
    (comp (ref "TP105")
      (value "TEST-POINT3X4")
      (footprint "eagle-import:PAD.03X.04")
      (libsource (lib "eagle-import") (part "TEST-POINT3X4"))
    )
    (comp (ref "TP106")
      (value "TEST-POINT3X4")
      (footprint "eagle-import:PAD.03X.04")
      (libsource (lib "eagle-import") (part "TEST-POINT3X4"))
    )
    (comp (ref "TP107")
      (value "TEST-POINT3X4")
      (footprint "eagle-import:PAD.03X.04")
      (libsource (lib "eagle-import") (part "TEST-POINT3X4"))
    )
    (comp (ref "TP108")
      (value "TEST-POINT3X4")
      (footprint "eagle-import:PAD.03X.04")
      (libsource (lib "eagle-import") (part "TEST-POINT3X4"))
    )
    (comp (ref "TP111")
      (value "TEST-POINT3X4")
      (footprint "eagle-import:PAD.03X.04")
      (libsource (lib "eagle-import") (part "TEST-POINT3X4"))
    )
    (comp (ref "TP113")
      (value "TEST-POINT3X4")
      (footprint "eagle-import:PAD.03X.04")
      (libsource (lib "eagle-import") (part "TEST-POINT3X4"))
    )
    (comp (ref "TP114")
      (value "TEST-POINT3X4")
      (footprint "eagle-import:PAD.03X.04")
      (libsource (lib "eagle-import") (part "TEST-POINT3X4"))
    )
    (comp (ref "TP115")
      (value "TEST-POINT3X4")
      (footprint "eagle-import:PAD.03X.04")
      (libsource (lib "eagle-import") (part "TEST-POINT3X4"))
    )
    (comp (ref "TP116")
      (value "TEST-POINT3X4")
      (footprint "eagle-import:PAD.03X.04")
      (libsource (lib "eagle-import") (part "TEST-POINT3X4"))
    )
    (comp (ref "TP117")
      (value "TEST-POINT3X4")
      (footprint "eagle-import:PAD.03X.04")
      (libsource (lib "eagle-import") (part "TEST-POINT3X4"))
    )
    (comp (ref "TP118")
      (value "TEST-POINT3X4")
      (footprint "eagle-import:PAD.03X.04")
      (libsource (lib "eagle-import") (part "TEST-POINT3X4"))
    )
    (comp (ref "TP119")
      (value "TEST-POINT3X4")
      (footprint "eagle-import:PAD.03X.04")
      (libsource (lib "eagle-import") (part "TEST-POINT3X4"))
    )
    (comp (ref "TP120")
      (value "TEST-POINT3X4")
      (footprint "eagle-import:PAD.03X.04")
      (libsource (lib "eagle-import") (part "TEST-POINT3X4"))
    )
    (comp (ref "TP122")
      (value "TEST-POINT3X4")
      (footprint "eagle-import:PAD.03X.04")
      (libsource (lib "eagle-import") (part "TEST-POINT3X4"))
    )
    (comp (ref "TP123")
      (value "TEST-POINT3X4")
      (footprint "eagle-import:PAD.03X.04")
      (libsource (lib "eagle-import") (part "TEST-POINT3X4"))
    )
    (comp (ref "TP124")
      (value "TEST-POINT3X4")
      (footprint "eagle-import:PAD.03X.04")
      (libsource (lib "eagle-import") (part "TEST-POINT3X4"))
    )
    (comp (ref "TP125")
      (value "TEST-POINT3X4")
      (footprint "eagle-import:PAD.03X.04")
      (libsource (lib "eagle-import") (part "TEST-POINT3X4"))
    )
    (comp (ref "TP126")
      (value "TEST-POINT3X4")
      (footprint "eagle-import:PAD.03X.04")
      (libsource (lib "eagle-import") (part "TEST-POINT3X4"))
    )
    (comp (ref "TP127")
      (value "TEST-POINT3X4")
      (footprint "eagle-import:PAD.03X.04")
      (libsource (lib "eagle-import") (part "TEST-POINT3X4"))
    )
    (comp (ref "TP128")
      (value "TEST-POINT3X4")
      (footprint "eagle-import:PAD.03X.04")
      (libsource (lib "eagle-import") (part "TEST-POINT3X4"))
    )
    (comp (ref "TP131")
      (value "TEST-POINT3X4")
      (footprint "eagle-import:PAD.03X.04")
      (libsource (lib "eagle-import") (part "TEST-POINT3X4"))
    )
    (comp (ref "TP134")
      (value "TEST-POINT3X4")
      (footprint "eagle-import:PAD.03X.04")
      (libsource (lib "eagle-import") (part "TEST-POINT3X4"))
    )
    (comp (ref "TP135")
      (value "TEST-POINT3X4")
      (footprint "eagle-import:PAD.03X.04")
      (libsource (lib "eagle-import") (part "TEST-POINT3X4"))
    )
    (comp (ref "TP137")
      (value "TEST-POINT3X4")
      (footprint "eagle-import:PAD.03X.04")
      (libsource (lib "eagle-import") (part "TEST-POINT3X4"))
    )
    (comp (ref "TP142")
      (value "TEST-POINT3X4")
      (footprint "eagle-import:PAD.03X.04")
      (libsource (lib "eagle-import") (part "TEST-POINT3X4"))
    )
    (comp (ref "TP143")
      (value "TEST-POINT3X4")
      (footprint "eagle-import:PAD.03X.04")
      (libsource (lib "eagle-import") (part "TEST-POINT3X4"))
    )
    (comp (ref "TP146")
      (value "TEST-POINT3X4")
      (footprint "eagle-import:PAD.03X.04")
      (libsource (lib "eagle-import") (part "TEST-POINT3X4"))
    )
    (comp (ref "TP147")
      (value "TEST-POINT3X4")
      (footprint "eagle-import:PAD.03X.04")
      (libsource (lib "eagle-import") (part "TEST-POINT3X4"))
    )
    (comp (ref "TP148")
      (value "TEST-POINT3X4")
      (footprint "eagle-import:PAD.03X.04")
      (libsource (lib "eagle-import") (part "TEST-POINT3X4"))
    )
    (comp (ref "TP149")
      (value "TEST-POINT3X4")
      (footprint "eagle-import:PAD.03X.04")
      (libsource (lib "eagle-import") (part "TEST-POINT3X4"))
    )
    (comp (ref "TP152")
      (value "TEST-POINT3X4")
      (footprint "eagle-import:PAD.03X.04")
      (libsource (lib "eagle-import") (part "TEST-POINT3X4"))
    )
    (comp (ref "TP153")
      (value "TEST-POINT3X4")
      (footprint "eagle-import:PAD.03X.04")
      (libsource (lib "eagle-import") (part "TEST-POINT3X4"))
    )
    (comp (ref "TP158")
      (value "TEST-POINT3X4")
      (footprint "eagle-import:PAD.03X.04")
      (libsource (lib "eagle-import") (part "TEST-POINT3X4"))
    )
    (comp (ref "TP159")
      (value "TEST-POINT3X4")
      (footprint "eagle-import:PAD.03X.04")
      (libsource (lib "eagle-import") (part "TEST-POINT3X4"))
    )
    (comp (ref "TP162")
      (value "TEST-POINT3X4")
      (footprint "eagle-import:PAD.03X.04")
      (libsource (lib "eagle-import") (part "TEST-POINT3X4"))
    )
    (comp (ref "TP174")
      (value "TEST-POINT3X4")
      (footprint "eagle-import:PAD.03X.04")
      (libsource (lib "eagle-import") (part "TEST-POINT3X4"))
    )
    (comp (ref "TP177")
      (value "TEST-POINT3X4")
      (footprint "eagle-import:PAD.03X.04")
      (libsource (lib "eagle-import") (part "TEST-POINT3X4"))
    )
    (comp (ref "TP178")
      (value "TEST-POINT3X4")
      (footprint "eagle-import:PAD.03X.04")
      (libsource (lib "eagle-import") (part "TEST-POINT3X4"))
    )
    (comp (ref "TP180")
      (value "TEST-POINT3X4")
      (footprint "eagle-import:PAD.03X.04")
      (libsource (lib "eagle-import") (part "TEST-POINT3X4"))
    )
    (comp (ref "U3")
      (value "THGBMJG7C2LBAU8")
      (footprint "eagle-import:BGA-153(11.5X13)(EMMC-BA)")
      (libsource (lib "eagle-import") (part "EMMC+RESET+5.1-COMPATIBLE-BA"))
    )
    (comp (ref "U5")
      (value "SN74LVC8T245MPWREPPW24-M")
      (footprint "eagle-import:PW24-M")
      (fields (field (name "MPN") " ‎SN74LVC8T245MPWREP‎"))
      (libsource (lib "eagle-import") (part "SN74LVC8T245MPWREPPW24-M"))
    )
    (comp (ref "U6")
      (value "CLVCH16T245MDGGREP")
      (footprint "eagle-import:DGG48-M")
      (libsource (lib "eagle-import") (part "CLVCH16T245MDGGREP"))
    )
    (comp (ref "U8")
      (value "TLV70028QDDCRQ1")
      (footprint "eagle-import:SOT23-5")
      (fields (field (name "MPN") "TLV70028DDCR"))
      (libsource (lib "eagle-import") (part "TLV70028QDDCRQ1"))
    )
    (comp (ref "U9")
      (value "TCA9509DGKRDGK8-M")
      (footprint "eagle-import:DGK8-M")
      (fields (field (name "MFR") "Texas Instruments") (field (name "MPN") "TCA9509DGKR"))
      (libsource (lib "eagle-import") (part "TCA9509DGKRDGK8-M"))
    )
    (comp (ref "U11")
      (value "TCAN330")
      (footprint "eagle-import:SOT23-8_TI-DCN")
      (fields (field (name "MPN") "TCAN330GDCNT"))
      (libsource (lib "eagle-import") (part "TCAN330"))
    )
    (comp (ref "U17")
      (value "25AAXX")
      (footprint "eagle-import:SOIC8")
      (fields (field (name "MPN") "25AA02E48T-I/SN"))
      (libsource (lib "eagle-import") (part "25AAXX"))
    )
  )
  (nets
    (net (code "7") (name "2.8V") (class "Default")
      (node (ref "C21") (pin "1") (pinfunction "1_1") (pintype "passive"))
      (node (ref "C23") (pin "1") (pinfunction "1_1") (pintype "passive"))
      (node (ref "C24") (pin "1") (pinfunction "1_1") (pintype "passive"))
      (node (ref "C25") (pin "1") (pinfunction "1_1") (pintype "passive"))
      (node (ref "C26") (pin "1") (pinfunction "1_1") (pintype "passive"))
      (node (ref "R17") (pin "1") (pinfunction "1_1") (pintype "passive"))
      (node (ref "R18") (pin "1") (pinfunction "1_1") (pintype "passive"))
      (node (ref "U5") (pin "1") (pinfunction "VCCA_1") (pintype "power_in"))
      (node (ref "U6") (pin "18") (pinfunction "VCCB_18") (pintype "power_in"))
      (node (ref "U6") (pin "7") (pinfunction "VCCB_7") (pintype "power_in"))
      (node (ref "U8") (pin "5") (pinfunction "OUT_5") (pintype "power_in"))
      (node (ref "U9") (pin "8") (pinfunction "VCCB_8") (pintype "power_in"))
    )
    (net (code "8") (name "3.3V") (class "Default")
      (node (ref "C11") (pin "1") (pinfunction "1_1") (pintype "passive"))
      (node (ref "C16") (pin "1") (pinfunction "1_1") (pintype "passive"))
      (node (ref "C17") (pin "1") (pinfunction "1_1") (pintype "passive"))
      (node (ref "C2") (pin "1") (pinfunction "1_1") (pintype "passive"))
      (node (ref "C20") (pin "1") (pinfunction "1_1") (pintype "passive"))
      (node (ref "C27") (pin "1") (pinfunction "1_1") (pintype "passive"))
      (node (ref "C28") (pin "1") (pinfunction "1_1") (pintype "passive"))
      (node (ref "C3") (pin "1") (pinfunction "1_1") (pintype "passive"))
      (node (ref "C31") (pin "2") (pinfunction "2_2") (pintype "passive"))
      (node (ref "C40") (pin "2") (pinfunction "2_2") (pintype "passive"))
      (node (ref "C42") (pin "1") (pinfunction "1_1") (pintype "passive"))
      (node (ref "C43") (pin "1") (pinfunction "1_1") (pintype "passive"))
      (node (ref "C5") (pin "1") (pinfunction "1_1") (pintype "passive"))
      (node (ref "C6") (pin "1") (pinfunction "1_1") (pintype "passive"))
      (node (ref "C8") (pin "1") (pinfunction "1_1") (pintype "passive"))
      (node (ref "C9") (pin "1") (pinfunction "1_1") (pintype "passive"))
      (node (ref "J100") (pin "4") (pinfunction "VDD_4") (pintype "bidirectional"))
      (node (ref "J101") (pin "31") (pinfunction "31_31") (pintype "passive"))
      (node (ref "J101") (pin "32") (pinfunction "32_32") (pintype "passive"))
      (node (ref "J101") (pin "33") (pinfunction "33_33") (pintype "passive"))
      (node (ref "J102") (pin "1") (pinfunction "VTREF_1") (pintype "passive"))
      (node (ref "R1") (pin "1") (pinfunction "1_1") (pintype "passive"))
      (node (ref "R10") (pin "10") (pinfunction "55_10") (pintype "passive"))
      (node (ref "R10") (pin "5") (pinfunction "55_5") (pintype "passive"))
      (node (ref "R11") (pin "2") (pinfunction "2_2") (pintype "passive"))
      (node (ref "R12") (pin "2") (pinfunction "2_2") (pintype "passive"))
      (node (ref "R20") (pin "2") (pinfunction "2_2") (pintype "passive"))
      (node (ref "R21") (pin "2") (pinfunction "2_2") (pintype "passive"))
      (node (ref "R22") (pin "2") (pinfunction "2_2") (pintype "passive"))
      (node (ref "R24") (pin "10") (pinfunction "55_10") (pintype "passive"))
      (node (ref "R24") (pin "5") (pinfunction "55_5") (pintype "passive"))
      (node (ref "R29") (pin "1") (pinfunction "1_1") (pintype "passive"))
      (node (ref "R30") (pin "1") (pinfunction "1_1") (pintype "passive"))
      (node (ref "R60") (pin "1") (pinfunction "1_1") (pintype "passive"))
      (node (ref "R8") (pin "10") (pinfunction "55_10") (pintype "passive"))
      (node (ref "R8") (pin "5") (pinfunction "55_5") (pintype "passive"))
      (node (ref "R9") (pin "10") (pinfunction "55_10") (pintype "passive"))
      (node (ref "R9") (pin "5") (pinfunction "55_5") (pintype "passive"))
      (node (ref "TP25") (pin "P$1") (pinfunction "1_P$1") (pintype "bidirectional"))
      (node (ref "U11") (pin "3") (pinfunction "VCC_3") (pintype "power_in"))
      (node (ref "U17") (pin "8") (pinfunction "VCC_8") (pintype "power_in"))
      (node (ref "U3") (pin "C6") (pinfunction "VDDQ_C6") (pintype "power_in"))
      (node (ref "U3") (pin "E6") (pinfunction "VDDIO_E6") (pintype "power_in"))
      (node (ref "U3") (pin "F5") (pinfunction "VDDIO_F5") (pintype "power_in"))
      (node (ref "U3") (pin "J10") (pinfunction "VDDIO_J10") (pintype "power_in"))
      (node (ref "U3") (pin "K9") (pinfunction "VDDIO_K9") (pintype "power_in"))
      (node (ref "U3") (pin "M4") (pinfunction "VDDQ_M4") (pintype "power_in"))
      (node (ref "U3") (pin "N4") (pinfunction "VDDQ_N4") (pintype "power_in"))
      (node (ref "U3") (pin "P3") (pinfunction "VDDQ_P3") (pintype "power_in"))
      (node (ref "U3") (pin "P5") (pinfunction "VDDQ_P5") (pintype "power_in"))
      (node (ref "U5") (pin "23") (pinfunction "VCCB_23") (pintype "power_in"))
      (node (ref "U5") (pin "24") (pinfunction "VCCB_24") (pintype "power_in"))
      (node (ref "U6") (pin "31") (pinfunction "VCCA_31") (pintype "power_in"))
      (node (ref "U6") (pin "42") (pinfunction "VCCA_42") (pintype "power_in"))
      (node (ref "U7") (pin "F6") (pinfunction "SYS_VDD1_3P3V_F6") (pintype "power_in"))
      (node (ref "U7") (pin "F7") (pinfunction "SYS_VDD1_3P3V_F7") (pintype "power_in"))
      (node (ref "U7") (pin "G6") (pinfunction "SYS_VDD1_3P3V_G6") (pintype "power_in"))
      (node (ref "U7") (pin "G7") (pinfunction "SYS_VDD1_3P3V_G7") (pintype "power_in"))
      (node (ref "U8") (pin "1") (pinfunction "IN_1") (pintype "power_in"))
      (node (ref "U8") (pin "3") (pinfunction "EN_3") (pintype "input"))
      (node (ref "U9") (pin "1") (pinfunction "VCCA_1") (pintype "power_in"))
    )
    (net (code "9") (name "3.3VA") (class "Default")
      (node (ref "C18") (pin "1") (pinfunction "1_1") (pintype "passive"))
      (node (ref "C41") (pin "1") (pinfunction "1_1") (pintype "passive"))
      (node (ref "JP104") (pin "1") (pinfunction "1_1") (pintype "passive"))
      (node (ref "TP14") (pin "P$1") (pinfunction "1_P$1") (pintype "bidirectional"))
      (node (ref "TP164") (pin "P$1") (pinfunction "1_P$1") (pintype "bidirectional"))
      (node (ref "U18") (pin "5") (pinfunction "VCC_5") (pintype "power_in"))
      (node (ref "U4") (pin "5") (pinfunction "VCC_5") (pintype "bidirectional"))
      (node (ref "U7") (pin "K11") (pinfunction "SYS_RTC_1P8V_K11") (pintype "power_in"))
      (node (ref "U7") (pin "L11") (pinfunction "SYS_RTC_1P8V_L11") (pintype "power_in"))
    )
    (net (code "10") (name "5V") (class "Default")
      (node (ref "C14") (pin "1") (pinfunction "1_1") (pintype "passive"))
      (node (ref "C36") (pin "1") (pinfunction "1_1") (pintype "passive"))
      (node (ref "L1") (pin "2") (pinfunction "2_2") (pintype "passive"))
      (node (ref "R62") (pin "2") (pinfunction "2_2") (pintype "passive"))
      (node (ref "TP49") (pin "1") (pinfunction "1_1") (pintype "passive"))
      (node (ref "U15") (pin "10") (pinfunction "FB_10") (pintype "input"))
      (node (ref "U7") (pin "P10") (pinfunction "VIN_AC_P10") (pintype "power_in"))
      (node (ref "U7") (pin "R10") (pinfunction "VIN_AC_R10") (pintype "power_in"))
      (node (ref "U7") (pin "T10") (pinfunction "VIN_AC_T10") (pintype "power_in"))
    )
    (net (code "11") (name "AD0") (class "Default")
      (node (ref "R57") (pin "1") (pinfunction "1_1") (pintype "passive"))
      (node (ref "R58") (pin "2") (pinfunction "2_2") (pintype "passive"))
      (node (ref "R69") (pin "2") (pinfunction "2_2") (pintype "passive"))
      (node (ref "R70") (pin "1") (pinfunction "1_1") (pintype "passive"))
      (node (ref "U16") (pin "1") (pinfunction "AD0_1") (pintype "input"))
    )
    (net (code "12") (name "AD1") (class "Default")
      (node (ref "R55") (pin "1") (pinfunction "1_1") (pintype "passive"))
      (node (ref "R56") (pin "2") (pinfunction "2_2") (pintype "passive"))
      (node (ref "R67") (pin "2") (pinfunction "2_2") (pintype "passive"))
      (node (ref "R68") (pin "1") (pinfunction "1_1") (pintype "passive"))
      (node (ref "U16") (pin "2") (pinfunction "AD1_2") (pintype "input"))
    )
    (net (code "13") (name "AD2") (class "Default")
      (node (ref "R53") (pin "1") (pinfunction "1_1") (pintype "passive"))
      (node (ref "R54") (pin "2") (pinfunction "2_2") (pintype "passive"))
      (node (ref "R65") (pin "2") (pinfunction "2_2") (pintype "passive"))
      (node (ref "R66") (pin "1") (pinfunction "1_1") (pintype "passive"))
      (node (ref "U16") (pin "3") (pinfunction "AD2_3") (pintype "input"))
    )
    (net (code "14") (name "BOOT0") (class "Default")
      (node (ref "TP51") (pin "1") (pinfunction "1_1") (pintype "passive"))
      (node (ref "U16") (pin "10") (pinfunction "IO5_10") (pintype "bidirectional"))
    )
    (net (code "15") (name "BUS_OE") (class "Default")
      (node (ref "R11") (pin "1") (pinfunction "1_1") (pintype "passive"))
      (node (ref "TP113") (pin "P$1") (pinfunction "1_P$1") (pintype "bidirectional"))
      (node (ref "U6") (pin "25") (pinfunction "~{2OE}_25") (pintype "input"))
      (node (ref "U6") (pin "48") (pinfunction "~{1OE}_48") (pintype "input"))
      (node (ref "U7") (pin "F14") (pinfunction "MII1_CRS_F14") (pintype "bidirectional"))
    )
    (net (code "16") (name "CAM_OE") (class "Default")
      (node (ref "TP8") (pin "P$1") (pinfunction "1_P$1") (pintype "bidirectional"))
      (node (ref "U5") (pin "17") (pinfunction "B5_17") (pintype "bidirectional"))
      (node (ref "U7") (pin "F15") (pinfunction "MII1_COL_F15") (pintype "bidirectional"))
    )
    (net (code "17") (name "CAN1_H") (class "Default")
      (node (ref "J4") (pin "33") (pinfunction "33_33") (pintype "passive"))
      (node (ref "J4") (pin "34") (pinfunction "34_34") (pintype "passive"))
      (node (ref "TP184") (pin "P$1") (pinfunction "1_P$1") (pintype "bidirectional"))
    )
    (net (code "18") (name "CAN1_L") (class "Default")
      (node (ref "J4") (pin "35") (pinfunction "35_35") (pintype "passive"))
      (node (ref "J4") (pin "36") (pinfunction "36_36") (pintype "passive"))
      (node (ref "TP183") (pin "P$1") (pinfunction "1_P$1") (pintype "bidirectional"))
    )
    (net (code "19") (name "CAN2_H") (class "Default")
      (node (ref "J4") (pin "17") (pinfunction "17_17") (pintype "passive"))
      (node (ref "J4") (pin "18") (pinfunction "18_18") (pintype "passive"))
      (node (ref "U11") (pin "7") (pinfunction "CANH_7") (pintype "bidirectional"))
    )
    (net (code "20") (name "CAN2_L") (class "Default")
      (node (ref "J4") (pin "19") (pinfunction "19_19") (pintype "passive"))
      (node (ref "J4") (pin "20") (pinfunction "20_20") (pintype "passive"))
      (node (ref "U11") (pin "6") (pinfunction "CANL_6") (pintype "bidirectional"))
    )
    (net (code "21") (name "CB-RESET") (class "Default")
      (node (ref "R39") (pin "2") (pinfunction "2_2") (pintype "passive"))
      (node (ref "TP54") (pin "1") (pinfunction "1_1") (pintype "passive"))
      (node (ref "U14") (pin "9") (pinfunction "CIN2-_9") (pintype "input"))
      (node (ref "U16") (pin "9") (pinfunction "IO4_9") (pintype "bidirectional"))
    )
    (net (code "22") (name "CB_CTRL") (class "Default")
      (node (ref "Q2") (pin "1") (pinfunction "G_1") (pintype "passive"))
      (node (ref "Q5") (pin "3") (pinfunction "G_3") (pintype "passive"))
      (node (ref "R64") (pin "1") (pinfunction "1_1") (pintype "passive"))
      (node (ref "TP52") (pin "1") (pinfunction "1_1") (pintype "passive"))
      (node (ref "U14") (pin "3") (pinfunction "LE_3") (pintype "input"))
      (node (ref "U14") (pin "4") (pinfunction "COUT1_4") (pintype "open_collector"))
      (node (ref "U14") (pin "6") (pinfunction "COUT2_6") (pintype "open_collector"))
    )
    (net (code "23") (name "CLK_EN") (class "Default")
      (node (ref "TP11") (pin "P$1") (pinfunction "1_P$1") (pintype "bidirectional"))
      (node (ref "U5") (pin "20") (pinfunction "B2_20") (pintype "bidirectional"))
      (node (ref "U7") (pin "E16") (pinfunction "MII1_RX_CLK_E16") (pintype "bidirectional"))
    )
    (net (code "24") (name "CLK_EN_E") (class "Default")
      (node (ref "J101") (pin "23") (pinfunction "23_23") (pintype "passive"))
      (node (ref "U5") (pin "4") (pinfunction "A2_4") (pintype "bidirectional"))
    )
    (net (code "25") (name "D0_E") (class "Default")
      (node (ref "J101") (pin "12") (pinfunction "12_12") (pintype "passive"))
      (node (ref "U6") (pin "11") (pinfunction "1B7_11") (pintype "bidirectional"))
    )
    (net (code "26") (name "D0_I") (class "Default")
      (node (ref "JP102") (pin "1") (pinfunction "1_1") (pintype "passive"))
      (node (ref "TP19") (pin "P$1") (pinfunction "1_P$1") (pintype "bidirectional"))
      (node (ref "U6") (pin "38") (pinfunction "1A7_38") (pintype "bidirectional"))
    )
    (net (code "27") (name "D1_E") (class "Default")
      (node (ref "J101") (pin "11") (pinfunction "11_11") (pintype "passive"))
      (node (ref "U6") (pin "12") (pinfunction "1B8_12") (pintype "bidirectional"))
    )
    (net (code "28") (name "D1_I") (class "Default")
      (node (ref "JP103") (pin "1") (pinfunction "1_1") (pintype "passive"))
      (node (ref "TP21") (pin "P$1") (pinfunction "1_P$1") (pintype "bidirectional"))
      (node (ref "U6") (pin "37") (pinfunction "1A8_37") (pintype "bidirectional"))
    )
    (net (code "29") (name "D2_E") (class "Default")
      (node (ref "J101") (pin "10") (pinfunction "10_10") (pintype "passive"))
      (node (ref "U6") (pin "13") (pinfunction "2B1_13") (pintype "bidirectional"))
    )
    (net (code "30") (name "D2_I") (class "Default")
      (node (ref "JP110") (pin "1") (pinfunction "1_1") (pintype "passive"))
      (node (ref "TP24") (pin "P$1") (pinfunction "1_P$1") (pintype "bidirectional"))
      (node (ref "U6") (pin "36") (pinfunction "2A1_36") (pintype "bidirectional"))
    )
    (net (code "31") (name "D3_E") (class "Default")
      (node (ref "J101") (pin "9") (pinfunction "9_9") (pintype "passive"))
      (node (ref "U6") (pin "14") (pinfunction "2B2_14") (pintype "bidirectional"))
    )
    (net (code "32") (name "D3_I") (class "Default")
      (node (ref "JP111") (pin "1") (pinfunction "1_1") (pintype "passive"))
      (node (ref "TP23") (pin "P$1") (pinfunction "1_P$1") (pintype "bidirectional"))
      (node (ref "U6") (pin "35") (pinfunction "2A2_35") (pintype "bidirectional"))
    )
    (net (code "33") (name "D4_E") (class "Default")
      (node (ref "J101") (pin "8") (pinfunction "8_8") (pintype "passive"))
      (node (ref "U6") (pin "16") (pinfunction "2B3_16") (pintype "bidirectional"))
    )
    (net (code "34") (name "D4_I") (class "Default")
      (node (ref "TP27") (pin "P$1") (pinfunction "1_P$1") (pintype "bidirectional"))
      (node (ref "U6") (pin "33") (pinfunction "2A3_33") (pintype "bidirectional"))
      (node (ref "U7") (pin "A1") (pinfunction "MCASP0_ACLKX_A1") (pintype "bidirectional"))
    )
    (net (code "35") (name "D5_E") (class "Default")
      (node (ref "J101") (pin "7") (pinfunction "7_7") (pintype "passive"))
      (node (ref "U6") (pin "17") (pinfunction "2B4_17") (pintype "bidirectional"))
    )
    (net (code "36") (name "D5_I") (class "Default")
      (node (ref "TP26") (pin "P$1") (pinfunction "1_P$1") (pintype "bidirectional"))
      (node (ref "U6") (pin "32") (pinfunction "2A4_32") (pintype "bidirectional"))
      (node (ref "U7") (pin "A2") (pinfunction "MCASP0_FSX_A2") (pintype "bidirectional"))
    )
    (net (code "37") (name "D6_E") (class "Default")
      (node (ref "J101") (pin "6") (pinfunction "6_6") (pintype "passive"))
      (node (ref "U6") (pin "19") (pinfunction "2B5_19") (pintype "bidirectional"))
    )
    (net (code "38") (name "D6_I") (class "Default")
      (node (ref "TP29") (pin "P$1") (pinfunction "1_P$1") (pintype "bidirectional"))
      (node (ref "U6") (pin "30") (pinfunction "2A5_30") (pintype "bidirectional"))
      (node (ref "U7") (pin "B2") (pinfunction "MCASP0_AXR0_B2") (pintype "bidirectional"))
    )
    (net (code "39") (name "D7_E") (class "Default")
      (node (ref "J101") (pin "13") (pinfunction "13_13") (pintype "passive"))
      (node (ref "U6") (pin "9") (pinfunction "1B6_9") (pintype "bidirectional"))
    )
    (net (code "40") (name "D7_I") (class "Default")
      (node (ref "TP20") (pin "P$1") (pinfunction "1_P$1") (pintype "bidirectional"))
      (node (ref "U6") (pin "40") (pinfunction "1A6_40") (pintype "bidirectional"))
      (node (ref "U7") (pin "B1") (pinfunction "MCASP0_AHCLKR_B1") (pintype "bidirectional"))
    )
    (net (code "41") (name "D8_E") (class "Default")
      (node (ref "J101") (pin "14") (pinfunction "14_14") (pintype "passive"))
      (node (ref "U6") (pin "8") (pinfunction "1B5_8") (pintype "bidirectional"))
    )
    (net (code "42") (name "D8_I") (class "Default")
      (node (ref "TP17") (pin "P$1") (pinfunction "1_P$1") (pintype "bidirectional"))
      (node (ref "U6") (pin "41") (pinfunction "1A5_41") (pintype "bidirectional"))
      (node (ref "U7") (pin "A3") (pinfunction "MCASP0_ACLKR_A3") (pintype "bidirectional"))
    )
    (net (code "43") (name "D9_E") (class "Default")
      (node (ref "J101") (pin "15") (pinfunction "15_15") (pintype "passive"))
      (node (ref "U6") (pin "6") (pinfunction "1B4_6") (pintype "bidirectional"))
    )
    (net (code "44") (name "D9_I") (class "Default")
      (node (ref "TP18") (pin "P$1") (pinfunction "1_P$1") (pintype "bidirectional"))
      (node (ref "U6") (pin "43") (pinfunction "1A4_43") (pintype "bidirectional"))
      (node (ref "U7") (pin "B3") (pinfunction "MCASP0_FSR_B3") (pintype "bidirectional"))
    )
    (net (code "45") (name "D10_E") (class "Default")
      (node (ref "J101") (pin "16") (pinfunction "16_16") (pintype "passive"))
      (node (ref "U6") (pin "5") (pinfunction "1B3_5") (pintype "bidirectional"))
    )
    (net (code "46") (name "D10_I") (class "Default")
      (node (ref "TP15") (pin "P$1") (pinfunction "1_P$1") (pintype "bidirectional"))
      (node (ref "U6") (pin "44") (pinfunction "1A3_44") (pintype "bidirectional"))
      (node (ref "U7") (pin "C3") (pinfunction "MCASP0_AXR1_C3") (pintype "bidirectional"))
    )
    (net (code "47") (name "D11_E") (class "Default")
      (node (ref "J101") (pin "17") (pinfunction "17_17") (pintype "passive"))
      (node (ref "U6") (pin "3") (pinfunction "1B2_3") (pintype "bidirectional"))
    )
    (net (code "48") (name "D11_I") (class "Default")
      (node (ref "TP16") (pin "P$1") (pinfunction "1_P$1") (pintype "bidirectional"))
      (node (ref "U6") (pin "46") (pinfunction "1A2_46") (pintype "bidirectional"))
      (node (ref "U7") (pin "C4") (pinfunction "MCASP0_AHCLKX_C4") (pintype "bidirectional"))
    )
    (net (code "49") (name "EEPROM_WP") (class "Default")
      (node (ref "J1") (pin "20") (pinfunction "DEBUG-3_20") (pintype "passive"))
      (node (ref "R75") (pin "1") (pinfunction "1_1") (pintype "passive"))
      (node (ref "TP112") (pin "P$1") (pinfunction "1_P$1") (pintype "bidirectional"))
      (node (ref "U18") (pin "6") (pinfunction "I4_6") (pintype "bidirectional"))
    )
    (net (code "50") (name "FLASH") (class "Default")
      (node (ref "TP13") (pin "P$1") (pinfunction "1_P$1") (pintype "bidirectional"))
      (node (ref "U6") (pin "47") (pinfunction "1A1_47") (pintype "bidirectional"))
      (node (ref "U7") (pin "G15") (pinfunction "MII1_TXD3_G15") (pintype "bidirectional"))
    )
    (net (code "51") (name "FLASH_E") (class "Default")
      (node (ref "J101") (pin "28") (pinfunction "28_28") (pintype "passive"))
      (node (ref "U6") (pin "2") (pinfunction "1B1_2") (pintype "bidirectional"))
    )
    (net (code "52") (name "GND") (class "Default")
      (node (ref "C1") (pin "2") (pinfunction "2_2") (pintype "passive"))
      (node (ref "C10") (pin "2") (pinfunction "2_2") (pintype "passive"))
      (node (ref "C11") (pin "2") (pinfunction "2_2") (pintype "passive"))
      (node (ref "C12") (pin "2") (pinfunction "2_2") (pintype "passive"))
      (node (ref "C13") (pin "2") (pinfunction "2_2") (pintype "passive"))
      (node (ref "C14") (pin "2") (pinfunction "2_2") (pintype "passive"))
      (node (ref "C15") (pin "2") (pinfunction "2_2") (pintype "passive"))
      (node (ref "C16") (pin "2") (pinfunction "2_2") (pintype "passive"))
      (node (ref "C17") (pin "2") (pinfunction "2_2") (pintype "passive"))
      (node (ref "C18") (pin "2") (pinfunction "2_2") (pintype "passive"))
      (node (ref "C2") (pin "2") (pinfunction "2_2") (pintype "passive"))
      (node (ref "C20") (pin "2") (pinfunction "2_2") (pintype "passive"))
      (node (ref "C21") (pin "2") (pinfunction "2_2") (pintype "passive"))
      (node (ref "C23") (pin "2") (pinfunction "2_2") (pintype "passive"))
      (node (ref "C24") (pin "2") (pinfunction "2_2") (pintype "passive"))
      (node (ref "C25") (pin "2") (pinfunction "2_2") (pintype "passive"))
      (node (ref "C26") (pin "2") (pinfunction "2_2") (pintype "passive"))
      (node (ref "C27") (pin "2") (pinfunction "2_2") (pintype "passive"))
      (node (ref "C28") (pin "2") (pinfunction "2_2") (pintype "passive"))
      (node (ref "C3") (pin "2") (pinfunction "2_2") (pintype "passive"))
      (node (ref "C31") (pin "1") (pinfunction "1_1") (pintype "passive"))
      (node (ref "C32") (pin "2") (pinfunction "2_2") (pintype "passive"))
      (node (ref "C34") (pin "2") (pinfunction "2_2") (pintype "passive"))
      (node (ref "C35") (pin "2") (pinfunction "2_2") (pintype "passive"))
      (node (ref "C36") (pin "2") (pinfunction "2_2") (pintype "passive"))
      (node (ref "C37") (pin "2") (pinfunction "2_2") (pintype "passive"))
      (node (ref "C38") (pin "2") (pinfunction "2_2") (pintype "passive"))
      (node (ref "C39") (pin "1") (pinfunction "1_1") (pintype "passive"))
      (node (ref "C4") (pin "2") (pinfunction "2_2") (pintype "passive"))
      (node (ref "C40") (pin "1") (pinfunction "1_1") (pintype "passive"))
      (node (ref "C41") (pin "2") (pinfunction "2_2") (pintype "passive"))
      (node (ref "C42") (pin "2") (pinfunction "2_2") (pintype "passive"))
      (node (ref "C43") (pin "2") (pinfunction "2_2") (pintype "passive"))
      (node (ref "C44") (pin "2") (pinfunction "2_2") (pintype "passive"))
      (node (ref "C5") (pin "2") (pinfunction "2_2") (pintype "passive"))
      (node (ref "C6") (pin "2") (pinfunction "2_2") (pintype "passive"))
      (node (ref "C7") (pin "2") (pinfunction "2_2") (pintype "passive"))
      (node (ref "C8") (pin "2") (pinfunction "2_2") (pintype "passive"))
      (node (ref "C9") (pin "2") (pinfunction "2_2") (pintype "passive"))
      (node (ref "D1") (pin "C") (pinfunction "C_C") (pintype "passive"))
      (node (ref "D2") (pin "C") (pinfunction "C_C") (pintype "passive"))
      (node (ref "D3") (pin "C") (pinfunction "C_C") (pintype "passive"))
      (node (ref "D4") (pin "C") (pinfunction "C_C") (pintype "passive"))
      (node (ref "D5") (pin "C") (pinfunction "C_C") (pintype "passive"))
      (node (ref "D6") (pin "C") (pinfunction "C_C") (pintype "passive"))
      (node (ref "D7") (pin "C") (pinfunction "C_C") (pintype "passive"))
      (node (ref "D8") (pin "C") (pinfunction "C_C") (pintype "passive"))
      (node (ref "J1") (pin "3") (pinfunction "GND_3") (pintype "passive"))
      (node (ref "J1") (pin "6") (pinfunction "GND_6") (pintype "passive"))
      (node (ref "J1") (pin "9") (pinfunction "GND_9") (pintype "passive"))
      (node (ref "J1") (pin "PAD1") (pinfunction "PAD_PAD1") (pintype "bidirectional"))
      (node (ref "J1") (pin "PAD2") (pinfunction "PAD_PAD2") (pintype "bidirectional"))
      (node (ref "J100") (pin "6") (pinfunction "VSS_6") (pintype "bidirectional"))
      (node (ref "J100") (pin "CGND1") (pinfunction "CGND_CGND1") (pintype "bidirectional"))
      (node (ref "J100") (pin "CGND2") (pinfunction "CGND_CGND2") (pintype "bidirectional"))
      (node (ref "J100") (pin "CGND3") (pinfunction "CGND_CGND3") (pintype "bidirectional"))
      (node (ref "J100") (pin "CGND4") (pinfunction "CGND_CGND4") (pintype "bidirectional"))
      (node (ref "J100") (pin "CGND5") (pinfunction "CGND_CGND5") (pintype "bidirectional"))
      (node (ref "J100") (pin "CGND6") (pinfunction "CGND_CGND6") (pintype "bidirectional"))
      (node (ref "J100") (pin "GND") (pinfunction "VSS_GND") (pintype "bidirectional"))
      (node (ref "J101") (pin "1") (pinfunction "1_1") (pintype "passive"))
      (node (ref "J101") (pin "18") (pinfunction "18_18") (pintype "passive"))
      (node (ref "J101") (pin "19") (pinfunction "19_19") (pintype "passive"))
      (node (ref "J101") (pin "2") (pinfunction "2_2") (pintype "passive"))
      (node (ref "J101") (pin "20") (pinfunction "20_20") (pintype "passive"))
      (node (ref "J101") (pin "34") (pinfunction "34_34") (pintype "passive"))
      (node (ref "J101") (pin "35") (pinfunction "35_35") (pintype "passive"))
      (node (ref "J101") (pin "36") (pinfunction "36_36") (pintype "passive"))
      (node (ref "J101") (pin "S1") (pinfunction "PAD_S1") (pintype "bidirectional"))
      (node (ref "J101") (pin "S2") (pinfunction "PAD_S2") (pintype "bidirectional"))
      (node (ref "J102") (pin "3") (pinfunction "GND_3") (pintype "passive"))
      (node (ref "J102") (pin "5") (pinfunction "GND_5") (pintype "passive"))
      (node (ref "J102") (pin "9") (pinfunction "GNDDET_9") (pintype "passive"))
      (node (ref "J4") (pin "27") (pinfunction "27_27") (pintype "passive"))
      (node (ref "J4") (pin "28") (pinfunction "28_28") (pintype "passive"))
      (node (ref "J4") (pin "29") (pinfunction "29_29") (pintype "passive"))
      (node (ref "J4") (pin "30") (pinfunction "30_30") (pintype "passive"))
      (node (ref "J4") (pin "31") (pinfunction "31_31") (pintype "passive"))
      (node (ref "J4") (pin "32") (pinfunction "32_32") (pintype "passive"))
      (node (ref "J4") (pin "37") (pinfunction "37_37") (pintype "passive"))
      (node (ref "J4") (pin "38") (pinfunction "38_38") (pintype "passive"))
      (node (ref "JP100") (pin "2") (pinfunction "2_2") (pintype "passive"))
      (node (ref "Q2") (pin "2") (pinfunction "S_2") (pintype "passive"))
      (node (ref "Q4") (pin "2") (pinfunction "S_2") (pintype "passive"))
      (node (ref "R14") (pin "2") (pinfunction "2_2") (pintype "passive"))
      (node (ref "R15") (pin "1") (pinfunction "1_1") (pintype "passive"))
      (node (ref "R16") (pin "2") (pinfunction "2_2") (pintype "passive"))
      (node (ref "R19") (pin "1") (pinfunction "1_1") (pintype "passive"))
      (node (ref "R25") (pin "10") (pinfunction "55_10") (pintype "passive"))
      (node (ref "R25") (pin "5") (pinfunction "55_5") (pintype "passive"))
      (node (ref "R26") (pin "10") (pinfunction "55_10") (pintype "passive"))
      (node (ref "R26") (pin "5") (pinfunction "55_5") (pintype "passive"))
      (node (ref "R33") (pin "1") (pinfunction "1_1") (pintype "passive"))
      (node (ref "R39") (pin "1") (pinfunction "1_1") (pintype "passive"))
      (node (ref "R40") (pin "1") (pinfunction "1_1") (pintype "passive"))
      (node (ref "R42") (pin "1") (pinfunction "1_1") (pintype "passive"))
      (node (ref "R46") (pin "1") (pinfunction "1_1") (pintype "passive"))
      (node (ref "R51") (pin "1") (pinfunction "1_1") (pintype "passive"))
      (node (ref "R54") (pin "1") (pinfunction "1_1") (pintype "passive"))
      (node (ref "R56") (pin "1") (pinfunction "1_1") (pintype "passive"))
      (node (ref "R58") (pin "1") (pinfunction "1_1") (pintype "passive"))
      (node (ref "R59") (pin "2") (pinfunction "2_2") (pintype "passive"))
      (node (ref "R6") (pin "1") (pinfunction "1_1") (pintype "passive"))
      (node (ref "U1") (pin "2") (pinfunction "GND_2") (pintype "power_in"))
      (node (ref "U11") (pin "2") (pinfunction "GND_2") (pintype "power_in"))
      (node (ref "U12") (pin "2") (pinfunction "GND_2") (pintype "power_in"))
      (node (ref "U13") (pin "2") (pinfunction "GND_2") (pintype "power_in"))
      (node (ref "U14") (pin "7") (pinfunction "GND_7") (pintype "power_in"))
      (node (ref "U14") (pin "EPAD") (pinfunction "GND_EPAD") (pintype "power_in"))
      (node (ref "U15") (pin "1") (pinfunction "GND_1") (pintype "power_in"))
      (node (ref "U15") (pin "11") (pinfunction "GND_11") (pintype "power_in"))
      (node (ref "U15") (pin "12") (pinfunction "GND_12") (pintype "power_in"))
      (node (ref "U15") (pin "16") (pinfunction "GND_16") (pintype "power_in"))
      (node (ref "U15") (pin "6") (pinfunction "LBO_6") (pintype "open_collector"))
      (node (ref "U15") (pin "7") (pinfunction "LBI_7") (pintype "input"))
      (node (ref "U15") (pin "9") (pinfunction "GND_9") (pintype "power_in"))
      (node (ref "U15") (pin "PAD") (pinfunction "GND_PAD") (pintype "power_in"))
      (node (ref "U16") (pin "6") (pinfunction "GND_6") (pintype "power_in"))
      (node (ref "U16") (pin "EPAD") (pinfunction "GND_EPAD") (pintype "power_in"))
      (node (ref "U17") (pin "4") (pinfunction "GND_4") (pintype "power_in"))
      (node (ref "U18") (pin "2") (pinfunction "GND_2") (pintype "power_in"))
      (node (ref "U2") (pin "2") (pinfunction "GND_2") (pintype "power_in"))
      (node (ref "U3") (pin "C4") (pinfunction "VSSQ_C4") (pintype "power_in"))
      (node (ref "U3") (pin "E7") (pinfunction "VSSIO_E7") (pintype "power_in"))
      (node (ref "U3") (pin "G5") (pinfunction "VSSIO_G5") (pintype "power_in"))
      (node (ref "U3") (pin "H10") (pinfunction "VSSIO_H10") (pintype "power_in"))
      (node (ref "U3") (pin "J5") (pinfunction "VSSIO_J5") (pintype "power_in"))
      (node (ref "U3") (pin "K8") (pinfunction "VSSIO_K8") (pintype "power_in"))
      (node (ref "U3") (pin "N2") (pinfunction "VSSQ_N2") (pintype "power_in"))
      (node (ref "U3") (pin "N5") (pinfunction "VSSQ_N5") (pintype "power_in"))
      (node (ref "U3") (pin "P4") (pinfunction "VSSQ_P4") (pintype "power_in"))
      (node (ref "U3") (pin "P6") (pinfunction "VSSQ_P6") (pintype "power_in"))
      (node (ref "U4") (pin "3") (pinfunction "GND_3") (pintype "bidirectional"))
      (node (ref "U5") (pin "11") (pinfunction "GND_11") (pintype "power_in"))
      (node (ref "U5") (pin "12") (pinfunction "GND_12") (pintype "power_in"))
      (node (ref "U5") (pin "13") (pinfunction "GND_13") (pintype "power_in"))
      (node (ref "U6") (pin "10") (pinfunction "GND_10") (pintype "power_in"))
      (node (ref "U6") (pin "15") (pinfunction "GND_15") (pintype "power_in"))
      (node (ref "U6") (pin "21") (pinfunction "GND_21") (pintype "power_in"))
      (node (ref "U6") (pin "28") (pinfunction "GND_28") (pintype "power_in"))
      (node (ref "U6") (pin "34") (pinfunction "GND_34") (pintype "power_in"))
      (node (ref "U6") (pin "39") (pinfunction "GND_39") (pintype "power_in"))
      (node (ref "U6") (pin "4") (pinfunction "GND_4") (pintype "power_in"))
      (node (ref "U6") (pin "45") (pinfunction "GND_45") (pintype "power_in"))
      (node (ref "U7") (pin "D8") (pinfunction "DGND_D8") (pintype "bidirectional"))
      (node (ref "U7") (pin "D9") (pinfunction "DGND_D9") (pintype "bidirectional"))
      (node (ref "U7") (pin "E10") (pinfunction "DGND_E10") (pintype "bidirectional"))
      (node (ref "U7") (pin "E11") (pinfunction "DGND_E11") (pintype "bidirectional"))
      (node (ref "U7") (pin "E12") (pinfunction "DGND_E12") (pintype "bidirectional"))
      (node (ref "U7") (pin "E5") (pinfunction "DGND_E5") (pintype "bidirectional"))
      (node (ref "U7") (pin "E6") (pinfunction "DGND_E6") (pintype "bidirectional"))
      (node (ref "U7") (pin "E7") (pinfunction "DGND_E7") (pintype "bidirectional"))
      (node (ref "U7") (pin "E8") (pinfunction "DGND_E8") (pintype "bidirectional"))
      (node (ref "U7") (pin "E9") (pinfunction "DGND_E9") (pintype "bidirectional"))
      (node (ref "U7") (pin "F12") (pinfunction "DGND_F12") (pintype "bidirectional"))
      (node (ref "U7") (pin "F5") (pinfunction "DGND_F5") (pintype "bidirectional"))
      (node (ref "U7") (pin "G12") (pinfunction "DGND_G12") (pintype "bidirectional"))
      (node (ref "U7") (pin "G5") (pinfunction "DGND_G5") (pintype "bidirectional"))
      (node (ref "U7") (pin "H12") (pinfunction "DGND_H12") (pintype "bidirectional"))
      (node (ref "U7") (pin "H13") (pinfunction "DGND_H13") (pintype "bidirectional"))
      (node (ref "U7") (pin "H4") (pinfunction "DGND_H4") (pintype "bidirectional"))
      (node (ref "U7") (pin "H5") (pinfunction "DGND_H5") (pintype "bidirectional"))
      (node (ref "U7") (pin "J12") (pinfunction "DGND_J12") (pintype "bidirectional"))
      (node (ref "U7") (pin "J13") (pinfunction "DGND_J13") (pintype "bidirectional"))
      (node (ref "U7") (pin "J4") (pinfunction "DGND_J4") (pintype "bidirectional"))
      (node (ref "U7") (pin "J5") (pinfunction "DGND_J5") (pintype "bidirectional"))
      (node (ref "U7") (pin "K12") (pinfunction "DGND_K12") (pintype "bidirectional"))
      (node (ref "U7") (pin "K5") (pinfunction "DGND_K5") (pintype "bidirectional"))
      (node (ref "U7") (pin "L12") (pinfunction "DGND_L12") (pintype "bidirectional"))
      (node (ref "U7") (pin "L5") (pinfunction "DGND_L5") (pintype "bidirectional"))
      (node (ref "U7") (pin "M10") (pinfunction "DGND_M10") (pintype "bidirectional"))
      (node (ref "U7") (pin "M11") (pinfunction "DGND_M11") (pintype "bidirectional"))
      (node (ref "U7") (pin "M12") (pinfunction "DGND_M12") (pintype "bidirectional"))
      (node (ref "U7") (pin "M5") (pinfunction "DGND_M5") (pintype "bidirectional"))
      (node (ref "U7") (pin "M6") (pinfunction "DGND_M6") (pintype "bidirectional"))
      (node (ref "U7") (pin "M7") (pinfunction "DGND_M7") (pintype "bidirectional"))
      (node (ref "U7") (pin "M8") (pinfunction "DGND_M8") (pintype "bidirectional"))
      (node (ref "U7") (pin "M9") (pinfunction "DGND_M9") (pintype "bidirectional"))
      (node (ref "U7") (pin "N8") (pinfunction "DGND_N8") (pintype "bidirectional"))
      (node (ref "U7") (pin "N9") (pinfunction "DGND_N9") (pintype "bidirectional"))
      (node (ref "U8") (pin "2") (pinfunction "GND_2") (pintype "power_in"))
      (node (ref "U9") (pin "4") (pinfunction "GND_4") (pintype "power_in"))
      (node (ref "Y1") (pin "2") (pinfunction "GND_2") (pintype "power_in"))
      (node (ref "Y1") (pin "4") (pinfunction "GND_4") (pintype "power_in"))
    )
    (net (code "53") (name "HSYNC_E") (class "Default")
      (node (ref "J101") (pin "4") (pinfunction "4_4") (pintype "passive"))
      (node (ref "U6") (pin "22") (pinfunction "2B7_22") (pintype "bidirectional"))
    )
    (net (code "54") (name "HSYNC_I") (class "Default")
      (node (ref "TP119") (pin "P$1") (pinfunction "1_P$1") (pintype "bidirectional"))
      (node (ref "U6") (pin "27") (pinfunction "2A7_27") (pintype "bidirectional"))
      (node (ref "U7") (pin "P7") (pinfunction "GPMC_AD15_P7") (pintype "bidirectional"))
    )
    (net (code "55") (name "I2C0_SCL") (class "Default")
      (node (ref "J1") (pin "18") (pinfunction "DEBUG-1_18") (pintype "passive"))
      (node (ref "R73") (pin "1") (pinfunction "1_1") (pintype "passive"))
      (node (ref "TP155") (pin "P$1") (pinfunction "1_P$1") (pintype "bidirectional"))
      (node (ref "U18") (pin "3") (pinfunction "I2_3") (pintype "bidirectional"))
    )
    (net (code "56") (name "I2C0_SDA") (class "Default")
      (node (ref "J1") (pin "19") (pinfunction "DEBUG-2_19") (pintype "passive"))
      (node (ref "R74") (pin "1") (pinfunction "1_1") (pintype "passive"))
      (node (ref "TP151") (pin "P$1") (pinfunction "1_P$1") (pintype "bidirectional"))
      (node (ref "U18") (pin "1") (pinfunction "I1_1") (pintype "bidirectional"))
    )
    (net (code "57") (name "I2C2_SCL") (class "Default")
      (node (ref "J101") (pin "21") (pinfunction "21_21") (pintype "passive"))
      (node (ref "R17") (pin "2") (pinfunction "2_2") (pintype "passive"))
      (node (ref "U9") (pin "7") (pinfunction "SCLB_7") (pintype "bidirectional"))
    )
    (net (code "58") (name "I2C2_SDA") (class "Default")
      (node (ref "J101") (pin "22") (pinfunction "22_22") (pintype "passive"))
      (node (ref "R18") (pin "2") (pinfunction "2_2") (pintype "passive"))
      (node (ref "U9") (pin "6") (pinfunction "SDAB_6") (pintype "bidirectional"))
    )
    (net (code "59") (name "INPUT_EN") (class "Default")
      (node (ref "R12") (pin "1") (pinfunction "1_1") (pintype "passive"))
      (node (ref "TP12") (pin "P$1") (pinfunction "1_P$1") (pintype "bidirectional"))
      (node (ref "U5") (pin "22") (pinfunction "~{OE}_22") (pintype "input"))
      (node (ref "U7") (pin "E14") (pinfunction "MII1_RXD0_E14") (pintype "bidirectional"))
    )
    (net (code "60") (name "N$103") (class "Default")
      (node (ref "J4") (pin "1") (pinfunction "1_1") (pintype "passive"))
      (node (ref "J4") (pin "2") (pinfunction "2_2") (pintype "passive"))
      (node (ref "TP62") (pin "P$1") (pinfunction "1_P$1") (pintype "bidirectional"))
    )
    (net (code "61") (name "Net-(C33-Pad1)") (class "Default")
      (node (ref "C33") (pin "1") (pinfunction "1_1") (pintype "passive"))
      (node (ref "R33") (pin "2") (pinfunction "2_2") (pintype "passive"))
      (node (ref "R38") (pin "2") (pinfunction "2_2") (pintype "passive"))
    )
    (net (code "62") (name "Net-(D1-PadA)") (class "Default")
      (node (ref "D1") (pin "A") (pinfunction "A_A") (pintype "passive"))
      (node (ref "R1") (pin "2") (pinfunction "2_2") (pintype "passive"))
    )
    (net (code "63") (name "Net-(D2-PadA)") (class "Default")
      (node (ref "D2") (pin "A") (pinfunction "A_A") (pintype "passive"))
      (node (ref "R2") (pin "2") (pinfunction "2_2") (pintype "passive"))
    )
    (net (code "64") (name "Net-(D3-PadA)") (class "Default")
      (node (ref "D3") (pin "A") (pinfunction "A_A") (pintype "passive"))
      (node (ref "R3") (pin "2") (pinfunction "2_2") (pintype "passive"))
    )
    (net (code "65") (name "Net-(D4-PadA)") (class "Default")
      (node (ref "D4") (pin "A") (pinfunction "A_A") (pintype "passive"))
      (node (ref "R4") (pin "2") (pinfunction "2_2") (pintype "passive"))
    )
    (net (code "66") (name "Net-(D5-PadA)") (class "Default")
      (node (ref "D5") (pin "A") (pinfunction "A_A") (pintype "passive"))
      (node (ref "R5") (pin "2") (pinfunction "2_2") (pintype "passive"))
    )
    (net (code "67") (name "Net-(D6-PadA)") (class "Default")
      (node (ref "D6") (pin "A") (pinfunction "A_A") (pintype "passive"))
      (node (ref "R49") (pin "1") (pinfunction "1_1") (pintype "passive"))
    )
    (net (code "68") (name "Net-(D7-PadA)") (class "Default")
      (node (ref "D7") (pin "A") (pinfunction "A_A") (pintype "passive"))
      (node (ref "R61") (pin "1") (pinfunction "1_1") (pintype "passive"))
    )
    (net (code "69") (name "Net-(D8-PadA)") (class "Default")
      (node (ref "D8") (pin "A") (pinfunction "A_A") (pintype "passive"))
      (node (ref "R62") (pin "1") (pinfunction "1_1") (pintype "passive"))
    )
    (net (code "70") (name "Net-(J100-CD#)") (class "Default")
      (node (ref "J100") (pin "CD") (pinfunction "CD#_CD") (pintype "bidirectional"))
      (node (ref "R8") (pin "6") (pinfunction "66_6") (pintype "passive"))
      (node (ref "TP22") (pin "P$1") (pinfunction "1_P$1") (pintype "bidirectional"))
      (node (ref "U7") (pin "C14") (pinfunction "SPI0_CS1_C14") (pintype "bidirectional"))
    )
    (net (code "71") (name "Net-(J100-CLK)") (class "Default")
      (node (ref "J100") (pin "5") (pinfunction "CLK_5") (pintype "bidirectional"))
      (node (ref "R8") (pin "3") (pinfunction "33_3") (pintype "passive"))
      (node (ref "U7") (pin "B15") (pinfunction "MMC0_CLK_B15") (pintype "bidirectional"))
    )
    (net (code "72") (name "Net-(J100-CMD{slash}DI)") (class "Default")
      (node (ref "J100") (pin "3") (pinfunction "CMD/DI_3") (pintype "bidirectional"))
      (node (ref "R8") (pin "8") (pinfunction "88_8") (pintype "passive"))
      (node (ref "U7") (pin "B16") (pinfunction "MMC0_CMD_B16") (pintype "bidirectional"))
    )
    (net (code "73") (name "Net-(J100-DAT0{slash}DO)") (class "Default")
      (node (ref "J100") (pin "7") (pinfunction "DAT0/DO_7") (pintype "bidirectional"))
      (node (ref "JP111") (pin "3") (pinfunction "3_3") (pintype "passive"))
      (node (ref "R8") (pin "7") (pinfunction "77_7") (pintype "passive"))
    )
    (net (code "74") (name "Net-(J100-DAT1)") (class "Default")
      (node (ref "J100") (pin "8") (pinfunction "DAT1_8") (pintype "bidirectional"))
      (node (ref "JP110") (pin "3") (pinfunction "3_3") (pintype "passive"))
      (node (ref "R8") (pin "4") (pinfunction "44_4") (pintype "passive"))
    )
    (net (code "75") (name "Net-(J100-DAT2)") (class "Default")
      (node (ref "J100") (pin "1") (pinfunction "DAT2_1") (pintype "bidirectional"))
      (node (ref "JP103") (pin "3") (pinfunction "3_3") (pintype "passive"))
      (node (ref "R8") (pin "9") (pinfunction "99_9") (pintype "passive"))
    )
    (net (code "76") (name "Net-(J100-DAT3{slash}CS)") (class "Default")
      (node (ref "J100") (pin "2") (pinfunction "DAT3/CS_2") (pintype "bidirectional"))
      (node (ref "JP102") (pin "3") (pinfunction "3_3") (pintype "passive"))
      (node (ref "R8") (pin "2") (pinfunction "22_2") (pintype "passive"))
    )
    (net (code "77") (name "Net-(J102-NC{slash}TDI)") (class "Default")
      (node (ref "J102") (pin "8") (pinfunction "NC/TDI_8") (pintype "passive"))
      (node (ref "U7") (pin "C1") (pinfunction "TDI_C1") (pintype "bidirectional"))
    )
    (net (code "78") (name "Net-(J102-SWDCLK{slash}TCK)") (class "Default")
      (node (ref "J102") (pin "4") (pinfunction "SWDCLK/TCK_4") (pintype "passive"))
      (node (ref "U7") (pin "D1") (pinfunction "TCK_D1") (pintype "bidirectional"))
    )
    (net (code "79") (name "Net-(J102-SWDIO{slash}TMS)") (class "Default")
      (node (ref "J102") (pin "2") (pinfunction "SWDIO/TMS_2") (pintype "passive"))
      (node (ref "U7") (pin "D2") (pinfunction "TMS_D2") (pintype "bidirectional"))
    )
    (net (code "80") (name "Net-(J102-SWO{slash}TDO)") (class "Default")
      (node (ref "J102") (pin "6") (pinfunction "SWO/TDO_6") (pintype "passive"))
      (node (ref "U7") (pin "C2") (pinfunction "TDO_C2") (pintype "bidirectional"))
    )
    (net (code "81") (name "Net-(J102-~{RESET})") (class "Default")
      (node (ref "J102") (pin "10") (pinfunction "~{RESET}_10") (pintype "passive"))
      (node (ref "JP1") (pin "2") (pinfunction "2_2") (pintype "passive"))
    )
    (net (code "82") (name "Net-(JP101-Pad2)") (class "Default")
      (node (ref "JP101") (pin "2") (pinfunction "2_2") (pintype "passive"))
      (node (ref "Q1") (pin "E") (pinfunction "E_E") (pintype "passive"))
      (node (ref "R23") (pin "2") (pinfunction "2_2") (pintype "passive"))
      (node (ref "R28") (pin "2") (pinfunction "2_2") (pintype "passive"))
    )
    (net (code "83") (name "Net-(L1-Pad1)") (class "Default")
      (node (ref "L1") (pin "1") (pinfunction "1_1") (pintype "passive"))
      (node (ref "U15") (pin "14") (pinfunction "SW_14") (pintype "output"))
      (node (ref "U15") (pin "15") (pinfunction "SW_15") (pintype "output"))
    )
    (net (code "84") (name "Net-(Q3A-G)") (class "Default")
      (node (ref "Q3") (pin "1") (pinfunction "G_1") (pintype "passive"))
      (node (ref "R35") (pin "2") (pinfunction "2_2") (pintype "passive"))
    )
    (net (code "85") (name "Net-(Q3A-S)") (class "Default")
      (node (ref "Q3") (pin "5") (pinfunction "S_5") (pintype "passive"))
      (node (ref "R48") (pin "2") (pinfunction "2_2") (pintype "passive"))
    )
    (net (code "86") (name "Net-(Q3B-G)") (class "Default")
      (node (ref "Q3") (pin "3") (pinfunction "G_3") (pintype "passive"))
      (node (ref "R43") (pin "2") (pinfunction "2_2") (pintype "passive"))
    )
    (net (code "87") (name "Net-(Q3B-S)") (class "Default")
      (node (ref "Q3") (pin "2") (pinfunction "S_2") (pintype "passive"))
      (node (ref "R41") (pin "2") (pinfunction "2_2") (pintype "passive"))
    )
    (net (code "88") (name "Net-(Q4-D)") (class "Default")
      (node (ref "Q4") (pin "3") (pinfunction "D_3") (pintype "passive"))
      (node (ref "Q6") (pin "3") (pinfunction "G_3") (pintype "passive"))
      (node (ref "R52") (pin "1") (pinfunction "1_1") (pintype "passive"))
    )
    (net (code "89") (name "Net-(Q5-S)") (class "Default")
      (node (ref "Q5") (pin "4") (pinfunction "S_4") (pintype "passive"))
      (node (ref "R63") (pin "2") (pinfunction "2_2") (pintype "passive"))
      (node (ref "R64") (pin "2") (pinfunction "2_2") (pintype "passive"))
      (node (ref "U14") (pin "15") (pinfunction "RS-_15") (pintype "passive"))
    )
    (net (code "90") (name "Net-(R9-22)") (class "Default")
      (node (ref "R9") (pin "2") (pinfunction "22_2") (pintype "passive"))
      (node (ref "U3") (pin "M5") (pinfunction "CMD_M5") (pintype "input"))
      (node (ref "U7") (pin "P1") (pinfunction "GPMC_CSN2_P1") (pintype "bidirectional"))
    )
    (net (code "91") (name "Net-(R9-33)") (class "Default")
      (node (ref "R9") (pin "3") (pinfunction "33_3") (pintype "passive"))
      (node (ref "U3") (pin "B4") (pinfunction "D5_B4") (pintype "input"))
      (node (ref "U7") (pin "T1") (pinfunction "GPMC_AD5_T1") (pintype "bidirectional"))
    )
    (net (code "92") (name "Net-(R9-44)") (class "Default")
      (node (ref "R9") (pin "4") (pinfunction "44_4") (pintype "passive"))
      (node (ref "U3") (pin "B3") (pinfunction "D4_B3") (pintype "input"))
      (node (ref "U7") (pin "T2") (pinfunction "GPMC_AD4_T2") (pintype "bidirectional"))
    )
    (net (code "93") (name "Net-(R9-66)") (class "Default")
      (node (ref "R9") (pin "6") (pinfunction "66_6") (pintype "passive"))
      (node (ref "U3") (pin "A3") (pinfunction "D0_A3") (pintype "input"))
      (node (ref "U7") (pin "R3") (pinfunction "GPMC_AD0_R3") (pintype "bidirectional"))
    )
    (net (code "94") (name "Net-(R9-77)") (class "Default")
      (node (ref "R9") (pin "7") (pinfunction "77_7") (pintype "passive"))
      (node (ref "U3") (pin "B2") (pinfunction "D3_B2") (pintype "input"))
      (node (ref "U7") (pin "T3") (pinfunction "GPMC_AD3_T3") (pintype "bidirectional"))
    )
    (net (code "95") (name "Net-(R9-88)") (class "Default")
      (node (ref "R9") (pin "8") (pinfunction "88_8") (pintype "passive"))
      (node (ref "U3") (pin "M6") (pinfunction "SCK_M6") (pintype "input"))
      (node (ref "U7") (pin "P2") (pinfunction "GPMC_CSN1_P2") (pintype "bidirectional"))
    )
    (net (code "96") (name "Net-(R10-11)") (class "Default")
      (node (ref "R10") (pin "1") (pinfunction "11_1") (pintype "passive"))
      (node (ref "U3") (pin "A4") (pinfunction "D1_A4") (pintype "input"))
      (node (ref "U7") (pin "R2") (pinfunction "GPMC_AD1_R2") (pintype "bidirectional"))
    )
    (net (code "97") (name "Net-(R10-22)") (class "Default")
      (node (ref "R10") (pin "2") (pinfunction "22_2") (pintype "passive"))
      (node (ref "U3") (pin "B6") (pinfunction "D7_B6") (pintype "input"))
      (node (ref "U7") (pin "R4") (pinfunction "GPMC_AD7_R4") (pintype "bidirectional"))
    )
    (net (code "98") (name "Net-(R10-33)") (class "Default")
      (node (ref "R10") (pin "3") (pinfunction "33_3") (pintype "passive"))
      (node (ref "U3") (pin "K5") (pinfunction "~{RST}_K5") (pintype "input"))
      (node (ref "U7") (pin "R13") (pinfunction "GPMC_A4_R13") (pintype "bidirectional"))
    )
    (net (code "99") (name "Net-(R10-88)") (class "Default")
      (node (ref "R10") (pin "8") (pinfunction "88_8") (pintype "passive"))
      (node (ref "U3") (pin "B5") (pinfunction "D6_B5") (pintype "bidirectional"))
      (node (ref "U7") (pin "P4") (pinfunction "GPMC_AD6_P4") (pintype "bidirectional"))
    )
    (net (code "100") (name "Net-(R10-99)") (class "Default")
      (node (ref "R10") (pin "9") (pinfunction "99_9") (pintype "passive"))
      (node (ref "U3") (pin "A5") (pinfunction "D2_A5") (pintype "input"))
      (node (ref "U7") (pin "R1") (pinfunction "GPMC_AD2_R1") (pintype "bidirectional"))
    )
    (net (code "101") (name "Net-(R24-22)") (class "Default")
      (node (ref "JP106") (pin "1") (pinfunction "1_1") (pintype "passive"))
      (node (ref "R24") (pin "2") (pinfunction "22_2") (pintype "passive"))
    )
    (net (code "102") (name "Net-(R24-33)") (class "Default")
      (node (ref "JP108") (pin "3") (pinfunction "3_3") (pintype "passive"))
      (node (ref "R24") (pin "3") (pinfunction "33_3") (pintype "passive"))
    )
    (net (code "103") (name "Net-(R24-44)") (class "Default")
      (node (ref "R24") (pin "4") (pinfunction "44_4") (pintype "passive"))
      (node (ref "U7") (pin "L1") (pinfunction "LCD_DATA14_L1") (pintype "bidirectional"))
    )
    (net (code "104") (name "Net-(R24-66)") (class "Default")
      (node (ref "JP109") (pin "3") (pinfunction "3_3") (pintype "passive"))
      (node (ref "R24") (pin "6") (pinfunction "66_6") (pintype "passive"))
    )
    (net (code "105") (name "Net-(R24-88)") (class "Default")
      (node (ref "J3") (pin "1") (pinfunction "1_1") (pintype "passive"))
      (node (ref "JP107") (pin "1") (pinfunction "1_1") (pintype "passive"))
      (node (ref "R24") (pin "8") (pinfunction "88_8") (pintype "passive"))
    )
    (net (code "106") (name "Net-(R24-99)") (class "Default")
      (node (ref "JP105") (pin "1") (pinfunction "1_1") (pintype "passive"))
      (node (ref "R24") (pin "9") (pinfunction "99_9") (pintype "passive"))
    )
    (net (code "107") (name "Net-(R25-11)") (class "Default")
      (node (ref "J3") (pin "3") (pinfunction "3_3") (pintype "passive"))
      (node (ref "JP107") (pin "3") (pinfunction "3_3") (pintype "passive"))
      (node (ref "R25") (pin "1") (pinfunction "11_1") (pintype "passive"))
    )
    (net (code "108") (name "Net-(R25-22)") (class "Default")
      (node (ref "JP106") (pin "3") (pinfunction "3_3") (pintype "passive"))
      (node (ref "R25") (pin "2") (pinfunction "22_2") (pintype "passive"))
    )
    (net (code "109") (name "Net-(R25-33)") (class "Default")
      (node (ref "JP105") (pin "3") (pinfunction "3_3") (pintype "passive"))
      (node (ref "R25") (pin "3") (pinfunction "33_3") (pintype "passive"))
    )
    (net (code "110") (name "Net-(R25-44)") (class "Default")
      (node (ref "R25") (pin "4") (pinfunction "44_4") (pintype "passive"))
      (node (ref "U7") (pin "H1") (pinfunction "LCD_DATA5_H1") (pintype "bidirectional"))
    )
    (net (code "111") (name "Net-(R25-66)") (class "Default")
      (node (ref "JP109") (pin "1") (pinfunction "1_1") (pintype "passive"))
      (node (ref "R25") (pin "6") (pinfunction "66_6") (pintype "passive"))
    )
    (net (code "112") (name "Net-(R25-77)") (class "Default")
      (node (ref "R25") (pin "7") (pinfunction "77_7") (pintype "passive"))
      (node (ref "U7") (pin "J3") (pinfunction "LCD_DATA6_J3") (pintype "bidirectional"))
    )
    (net (code "113") (name "Net-(R25-99)") (class "Default")
      (node (ref "JP108") (pin "1") (pinfunction "1_1") (pintype "passive"))
      (node (ref "R25") (pin "9") (pinfunction "99_9") (pintype "passive"))
    )
    (net (code "114") (name "Net-(R26-11)") (class "Default")
      (node (ref "R26") (pin "1") (pinfunction "11_1") (pintype "passive"))
      (node (ref "U7") (pin "M3") (pinfunction "LCD_DATA15_M3") (pintype "bidirectional"))
    )
    (net (code "115") (name "Net-(R26-22)") (class "Default")
      (node (ref "R26") (pin "2") (pinfunction "22_2") (pintype "passive"))
      (node (ref "U7") (pin "L3") (pinfunction "LCD_DATA12_L3") (pintype "bidirectional"))
    )
    (net (code "116") (name "Net-(R26-33)") (class "Default")
      (node (ref "R26") (pin "3") (pinfunction "33_3") (pintype "passive"))
      (node (ref "U7") (pin "K2") (pinfunction "LCD_DATA10_K2") (pintype "bidirectional"))
    )
    (net (code "117") (name "Net-(R26-44)") (class "Default")
      (node (ref "R26") (pin "4") (pinfunction "44_4") (pintype "passive"))
      (node (ref "U7") (pin "J1") (pinfunction "LCD_DATA8_J1") (pintype "bidirectional"))
    )
    (net (code "118") (name "Net-(R26-66)") (class "Default")
      (node (ref "R26") (pin "6") (pinfunction "66_6") (pintype "passive"))
      (node (ref "U7") (pin "J2") (pinfunction "LCD_DATA7_J2") (pintype "bidirectional"))
    )
    (net (code "119") (name "Net-(R26-77)") (class "Default")
      (node (ref "R26") (pin "7") (pinfunction "77_7") (pintype "passive"))
      (node (ref "U7") (pin "K3") (pinfunction "LCD_DATA9_K3") (pintype "bidirectional"))
    )
    (net (code "120") (name "Net-(R26-88)") (class "Default")
      (node (ref "R26") (pin "8") (pinfunction "88_8") (pintype "passive"))
      (node (ref "U7") (pin "K1") (pinfunction "LCD_DATA11_K1") (pintype "bidirectional"))
    )
    (net (code "121") (name "Net-(R26-99)") (class "Default")
      (node (ref "R26") (pin "9") (pinfunction "99_9") (pintype "passive"))
      (node (ref "U7") (pin "L2") (pinfunction "LCD_DATA13_L2") (pintype "bidirectional"))
    )
    (net (code "122") (name "Net-(TP30-1)") (class "Default")
      (node (ref "TP30") (pin "P$1") (pinfunction "1_P$1") (pintype "bidirectional"))
      (node (ref "U7") (pin "A4") (pinfunction "XDMA_EVENT_INTR0_A4") (pintype "bidirectional"))
    )
    (net (code "123") (name "Net-(TP31-1)") (class "Default")
      (node (ref "R19") (pin "2") (pinfunction "2_2") (pintype "passive"))
      (node (ref "TP31") (pin "P$1") (pinfunction "1_P$1") (pintype "bidirectional"))
      (node (ref "U7") (pin "D3") (pinfunction "TRSTN_D3") (pintype "bidirectional"))
    )
    (net (code "124") (name "Net-(TP35-1)") (class "Default")
      (node (ref "TP35") (pin "P$1") (pinfunction "1_P$1") (pintype "bidirectional"))
      (node (ref "U11") (pin "5") (pinfunction "SHDN_5") (pintype "input"))
    )
    (net (code "125") (name "Net-(TP38-1)") (class "Default")
      (node (ref "TP38") (pin "P$1") (pinfunction "1_P$1") (pintype "bidirectional"))
      (node (ref "U7") (pin "B8") (pinfunction "AIN1_B8") (pintype "bidirectional"))
    )
    (net (code "126") (name "Net-(TP39-1)") (class "Default")
      (node (ref "TP39") (pin "P$1") (pinfunction "1_P$1") (pintype "bidirectional"))
      (node (ref "U7") (pin "A8") (pinfunction "AIN0_A8") (pintype "bidirectional"))
    )
    (net (code "127") (name "Net-(TP40-1)") (class "Default")
      (node (ref "TP40") (pin "P$1") (pinfunction "1_P$1") (pintype "bidirectional"))
      (node (ref "U11") (pin "8") (pinfunction "S_8") (pintype "input"))
    )
    (net (code "128") (name "Net-(TP69-1)") (class "Default")
      (node (ref "TP69") (pin "P$1") (pinfunction "1_P$1") (pintype "bidirectional"))
      (node (ref "U17") (pin "7") (pinfunction "~{HOLD}_7") (pintype "input"))
    )
    (net (code "129") (name "Net-(TP100-1)") (class "Default")
      (node (ref "TP100") (pin "P$1") (pinfunction "1_P$1") (pintype "bidirectional"))
      (node (ref "U7") (pin "T12") (pinfunction "GPMC_A0_T12") (pintype "bidirectional"))
    )
    (net (code "130") (name "Net-(TP101-1)") (class "Default")
      (node (ref "TP101") (pin "P$1") (pinfunction "1_P$1") (pintype "bidirectional"))
      (node (ref "U7") (pin "T13") (pinfunction "GPMC_A3_T13") (pintype "bidirectional"))
    )
    (net (code "131") (name "Net-(TP102-1)") (class "Default")
      (node (ref "TP102") (pin "P$1") (pinfunction "1_P$1") (pintype "bidirectional"))
      (node (ref "U7") (pin "T11") (pinfunction "PMIC_PB_IN_T11") (pintype "bidirectional"))
    )
    (net (code "132") (name "Net-(TP103-1)") (class "Default")
      (node (ref "TP103") (pin "P$1") (pinfunction "1_P$1") (pintype "bidirectional"))
      (node (ref "U7") (pin "T16") (pinfunction "GPMC_A11_T16") (pintype "bidirectional"))
    )
    (net (code "133") (name "Net-(TP104-1)") (class "Default")
      (node (ref "TP104") (pin "P$1") (pinfunction "1_P$1") (pintype "bidirectional"))
      (node (ref "U7") (pin "T4") (pinfunction "GPMC_AD8_T4") (pintype "bidirectional"))
    )
    (net (code "134") (name "Net-(TP105-1)") (class "Default")
      (node (ref "TP105") (pin "P$1") (pinfunction "1_P$1") (pintype "bidirectional"))
      (node (ref "U7") (pin "T5") (pinfunction "GPMC_AD11_T5") (pintype "bidirectional"))
    )
    (net (code "135") (name "Net-(TP106-1)") (class "Default")
      (node (ref "TP106") (pin "P$1") (pinfunction "1_P$1") (pintype "bidirectional"))
      (node (ref "U7") (pin "T7") (pinfunction "GPMC_CLK_T7") (pintype "bidirectional"))
    )
    (net (code "136") (name "Net-(TP107-1)") (class "Default")
      (node (ref "TP107") (pin "P$1") (pinfunction "1_P$1") (pintype "bidirectional"))
      (node (ref "U7") (pin "R7") (pinfunction "GPMC_CSN3_R7") (pintype "bidirectional"))
    )
    (net (code "137") (name "Net-(TP108-1)") (class "Default")
      (node (ref "TP108") (pin "P$1") (pinfunction "1_P$1") (pintype "bidirectional"))
      (node (ref "U7") (pin "T15") (pinfunction "GPMC_A9_T15") (pintype "bidirectional"))
    )
    (net (code "138") (name "Net-(TP111-1)") (class "Default")
      (node (ref "TP111") (pin "P$1") (pinfunction "1_P$1") (pintype "bidirectional"))
      (node (ref "U7") (pin "R16") (pinfunction "GPMC_WPN_R16") (pintype "bidirectional"))
    )
    (net (code "139") (name "Net-(TP114-1)") (class "Default")
      (node (ref "TP114") (pin "P$1") (pinfunction "1_P$1") (pintype "bidirectional"))
      (node (ref "U7") (pin "P15") (pinfunction "GPMC_WAIT0_P15") (pintype "bidirectional"))
    )
    (net (code "140") (name "Net-(TP115-1)") (class "Default")
      (node (ref "TP115") (pin "P$1") (pinfunction "1_P$1") (pintype "bidirectional"))
      (node (ref "U7") (pin "R5") (pinfunction "GPMC_AD10_R5") (pintype "bidirectional"))
    )
    (net (code "141") (name "Net-(TP117-1)") (class "Default")
      (node (ref "TP117") (pin "P$1") (pinfunction "1_P$1") (pintype "bidirectional"))
      (node (ref "U7") (pin "R15") (pinfunction "GPMC_A10_R15") (pintype "bidirectional"))
    )
    (net (code "142") (name "Net-(TP118-1)") (class "Default")
      (node (ref "TP118") (pin "P$1") (pinfunction "1_P$1") (pintype "bidirectional"))
      (node (ref "U7") (pin "R12") (pinfunction "GPMC_A1_R12") (pintype "bidirectional"))
    )
    (net (code "143") (name "Net-(TP120-1)") (class "Default")
      (node (ref "TP120") (pin "P$1") (pinfunction "1_P$1") (pintype "bidirectional"))
      (node (ref "U7") (pin "R6") (pinfunction "GPMC_AD13_R6") (pintype "bidirectional"))
    )
    (net (code "144") (name "Net-(TP121-1)") (class "Default")
      (node (ref "TP121") (pin "P$1") (pinfunction "1_P$1") (pintype "bidirectional"))
      (node (ref "U7") (pin "N10") (pinfunction "PMIC_POWER_EN_N10") (pintype "output"))
      (node (ref "U7") (pin "N11") (pinfunction "PMIC_PWR_EN_N11") (pintype "input"))
    )
    (net (code "145") (name "Net-(TP122-1)") (class "Default")
      (node (ref "TP122") (pin "P$1") (pinfunction "1_P$1") (pintype "bidirectional"))
      (node (ref "U7") (pin "P3") (pinfunction "GPMC_CSN0_P3") (pintype "bidirectional"))
    )
    (net (code "146") (name "Net-(TP123-1)") (class "Default")
      (node (ref "TP123") (pin "P$1") (pinfunction "1_P$1") (pintype "bidirectional"))
      (node (ref "U7") (pin "P5") (pinfunction "GPMC_AD9_P5") (pintype "bidirectional"))
    )
    (net (code "147") (name "Net-(TP124-1)") (class "Default")
      (node (ref "TP124") (pin "P$1") (pinfunction "1_P$1") (pintype "bidirectional"))
      (node (ref "U7") (pin "P6") (pinfunction "GPMC_AD12_P6") (pintype "bidirectional"))
    )
    (net (code "148") (name "Net-(TP125-1)") (class "Default")
      (node (ref "TP125") (pin "P$1") (pinfunction "1_P$1") (pintype "bidirectional"))
      (node (ref "U7") (pin "N14") (pinfunction "GPMC_BEN1_N14") (pintype "bidirectional"))
    )
    (net (code "149") (name "Net-(TP126-1)") (class "Default")
      (node (ref "TP126") (pin "P$1") (pinfunction "1_P$1") (pintype "bidirectional"))
      (node (ref "U7") (pin "P12") (pinfunction "GPMC_A2_P12") (pintype "bidirectional"))
    )
    (net (code "150") (name "Net-(TP127-1)") (class "Default")
      (node (ref "TP127") (pin "P$1") (pinfunction "1_P$1") (pintype "bidirectional"))
      (node (ref "U7") (pin "N2") (pinfunction "GPMC_WEN_N2") (pintype "bidirectional"))
    )
    (net (code "151") (name "Net-(TP128-1)") (class "Default")
      (node (ref "TP128") (pin "P$1") (pinfunction "1_P$1") (pintype "bidirectional"))
      (node (ref "U7") (pin "N1") (pinfunction "GPMC_OEN_REN_N1") (pintype "bidirectional"))
    )
    (net (code "152") (name "Net-(TP129-1)") (class "Default")
      (node (ref "TP129") (pin "P$1") (pinfunction "1_P$1") (pintype "bidirectional"))
      (node (ref "U7") (pin "N6") (pinfunction "PMIC_TS_N6") (pintype "bidirectional"))
    )
    (net (code "153") (name "Net-(TP130-1)") (class "Default")
      (node (ref "TP130") (pin "P$1") (pinfunction "1_P$1") (pintype "bidirectional"))
      (node (ref "TP4") (pin "P$1") (pinfunction "1_P$1") (pintype "bidirectional"))
      (node (ref "U7") (pin "N7") (pinfunction "PMIC_BAT_SENSE_N7") (pintype "bidirectional"))
      (node (ref "U7") (pin "P8") (pinfunction "VIN_BAT_P8") (pintype "power_in"))
      (node (ref "U7") (pin "R8") (pinfunction "VIN_BAT_R8") (pintype "power_in"))
      (node (ref "U7") (pin "T8") (pinfunction "VIN_BAT_T8") (pintype "power_in"))
    )
    (net (code "154") (name "Net-(TP131-1)") (class "Default")
      (node (ref "TP131") (pin "P$1") (pinfunction "1_P$1") (pintype "bidirectional"))
      (node (ref "U7") (pin "N3") (pinfunction "GPMC_BEN0_CLE_N3") (pintype "bidirectional"))
    )
    (net (code "155") (name "Net-(TP132-1)") (class "Default")
      (node (ref "TP132") (pin "P$1") (pinfunction "1_P$1") (pintype "bidirectional"))
      (node (ref "U7") (pin "N4") (pinfunction "PMIC_LDO_PGOOD_N4") (pintype "output"))
      (node (ref "U7") (pin "N5") (pinfunction "RTC_PWRONRSTN_N5") (pintype "bidirectional"))
    )
    (net (code "156") (name "Net-(TP133-1)") (class "Default")
      (node (ref "TP133") (pin "P$1") (pinfunction "1_P$1") (pintype "bidirectional"))
      (node (ref "U7") (pin "N13") (pinfunction "PMIC_MUX_IN_N13") (pintype "bidirectional"))
    )
    (net (code "157") (name "Net-(TP134-1)") (class "Default")
      (node (ref "TP134") (pin "P$1") (pinfunction "1_P$1") (pintype "bidirectional"))
      (node (ref "U7") (pin "M1") (pinfunction "GPMC_ADVN_ALE_M1") (pintype "bidirectional"))
    )
    (net (code "158") (name "Net-(TP135-1)") (class "Default")
      (node (ref "TP135") (pin "P$1") (pinfunction "1_P$1") (pintype "bidirectional"))
      (node (ref "U7") (pin "G16") (pinfunction "MII1_TXD2_G16") (pintype "bidirectional"))
    )
    (net (code "159") (name "Net-(TP136-1)") (class "Default")
      (node (ref "TP136") (pin "P$1") (pinfunction "1_P$1") (pintype "bidirectional"))
      (node (ref "U7") (pin "M13") (pinfunction "PMIC_NRESET_M13") (pintype "bidirectional"))
    )
    (net (code "160") (name "Net-(TP137-1)") (class "Default")
      (node (ref "TP137") (pin "P$1") (pinfunction "1_P$1") (pintype "bidirectional"))
      (node (ref "U7") (pin "H15") (pinfunction "MII1_TXD0_H15") (pintype "bidirectional"))
    )
    (net (code "161") (name "Net-(TP138-1)") (class "Default")
      (node (ref "TP138") (pin "P$1") (pinfunction "1_P$1") (pintype "bidirectional"))
      (node (ref "U7") (pin "K14") (pinfunction "USB0_ID_K14") (pintype "bidirectional"))
    )
    (net (code "162") (name "Net-(TP139-1)") (class "Default")
      (node (ref "TP139") (pin "P$1") (pinfunction "1_P$1") (pintype "bidirectional"))
      (node (ref "U7") (pin "J15") (pinfunction "USB0_DRVVBUS_J15") (pintype "bidirectional"))
    )
    (net (code "163") (name "Net-(TP140-1)") (class "Default")
      (node (ref "TP140") (pin "P$1") (pinfunction "1_P$1") (pintype "bidirectional"))
      (node (ref "U7") (pin "L4") (pinfunction "PMIC_NWAKEUP_L4") (pintype "output"))
      (node (ref "U7") (pin "M4") (pinfunction "EXT_WAKEUP_M4") (pintype "bidirectional"))
    )
    (net (code "164") (name "Net-(TP141-1)") (class "Default")
      (node (ref "TP141") (pin "P$1") (pinfunction "1_P$1") (pintype "bidirectional"))
      (node (ref "U7") (pin "K13") (pinfunction "USB0_CE_K13") (pintype "bidirectional"))
    )
    (net (code "165") (name "Net-(TP143-1)") (class "Default")
      (node (ref "TP143") (pin "P$1") (pinfunction "1_P$1") (pintype "bidirectional"))
      (node (ref "U7") (pin "J14") (pinfunction "RMII1_REF_CLK_J14") (pintype "bidirectional"))
    )
    (net (code "166") (name "Net-(TP144-1)") (class "Default")
      (node (ref "TP144") (pin "P$1") (pinfunction "1_P$1") (pintype "bidirectional"))
      (node (ref "U7") (pin "L13") (pinfunction "USB1_CE_L13") (pintype "bidirectional"))
    )
    (net (code "167") (name "Net-(TP145-1)") (class "Default")
      (node (ref "TP145") (pin "P$1") (pinfunction "1_P$1") (pintype "bidirectional"))
      (node (ref "U7") (pin "K4") (pinfunction "NC_K4") (pintype "bidirectional"))
    )
    (net (code "168") (name "Net-(TP147-1)") (class "Default")
      (node (ref "TP147") (pin "P$1") (pinfunction "1_P$1") (pintype "bidirectional"))
      (node (ref "U7") (pin "H16") (pinfunction "MII1_TX_CLK_H16") (pintype "bidirectional"))
    )
    (net (code "169") (name "Net-(TP148-1)") (class "Default")
      (node (ref "TP148") (pin "P$1") (pinfunction "1_P$1") (pintype "bidirectional"))
      (node (ref "U7") (pin "G14") (pinfunction "MII1_TX_EN_G14") (pintype "bidirectional"))
    )
    (net (code "170") (name "Net-(TP149-1)") (class "Default")
      (node (ref "TP149") (pin "P$1") (pinfunction "1_P$1") (pintype "bidirectional"))
      (node (ref "U7") (pin "H14") (pinfunction "MII1_TXD1_H14") (pintype "bidirectional"))
    )
    (net (code "171") (name "Net-(TP150-1)") (class "Default")
      (node (ref "TP150") (pin "P$1") (pinfunction "1_P$1") (pintype "bidirectional"))
      (node (ref "U7") (pin "J6") (pinfunction "NC_J6") (pintype "bidirectional"))
    )
    (net (code "172") (name "Net-(TP152-1)") (class "Default")
      (node (ref "TP152") (pin "P$1") (pinfunction "1_P$1") (pintype "bidirectional"))
      (node (ref "U7") (pin "F2") (pinfunction "LCD_HSYNC_F2") (pintype "bidirectional"))
    )
    (net (code "173") (name "Net-(TP153-1)") (class "Default")
      (node (ref "TP153") (pin "P$1") (pinfunction "1_P$1") (pintype "bidirectional"))
      (node (ref "U7") (pin "F3") (pinfunction "LCD_VSYNC_F3") (pintype "bidirectional"))
    )
    (net (code "174") (name "Net-(TP154-1)") (class "Default")
      (node (ref "TP154") (pin "P$1") (pinfunction "1_P$1") (pintype "bidirectional"))
      (node (ref "U7") (pin "G4") (pinfunction "VDD_CORE_G4") (pintype "bidirectional"))
    )
    (net (code "175") (name "Net-(TP156-1)") (class "Default")
      (node (ref "TP156") (pin "P$1") (pinfunction "1_P$1") (pintype "bidirectional"))
      (node (ref "U7") (pin "F4") (pinfunction "VDDS_DDR_F4") (pintype "bidirectional"))
    )
    (net (code "176") (name "Net-(TP157-1)") (class "Default")
      (node (ref "TP157") (pin "P$1") (pinfunction "1_P$1") (pintype "bidirectional"))
      (node (ref "U7") (pin "H6") (pinfunction "VPP_H6") (pintype "bidirectional"))
    )
    (net (code "177") (name "Net-(TP158-1)") (class "Default")
      (node (ref "TP158") (pin "P$1") (pinfunction "1_P$1") (pintype "bidirectional"))
      (node (ref "U7") (pin "E13") (pinfunction "MDIO_E13") (pintype "bidirectional"))
    )
    (net (code "178") (name "Net-(TP159-1)") (class "Default")
      (node (ref "TP159") (pin "P$1") (pinfunction "1_P$1") (pintype "bidirectional"))
      (node (ref "U7") (pin "E1") (pinfunction "LCD_AC_BIAS_EN_E1") (pintype "bidirectional"))
    )
    (net (code "179") (name "Net-(TP160-1)") (class "Default")
      (node (ref "TP160") (pin "P$1") (pinfunction "1_P$1") (pintype "bidirectional"))
      (node (ref "U7") (pin "F13") (pinfunction "VDD_MPU_F13") (pintype "bidirectional"))
    )
    (net (code "180") (name "Net-(TP161-1)") (class "Default")
      (node (ref "TP161") (pin "P$1") (pinfunction "1_P$1") (pintype "bidirectional"))
      (node (ref "U7") (pin "F11") (pinfunction "SYS_VDD2_3P3V_F11") (pintype "power_in"))
      (node (ref "U7") (pin "G11") (pinfunction "SYS_VDD2_3P3V_G11") (pintype "power_in"))
    )
    (net (code "181") (name "Net-(TP162-1)") (class "Default")
      (node (ref "TP162") (pin "P$1") (pinfunction "1_P$1") (pintype "bidirectional"))
      (node (ref "U7") (pin "F1") (pinfunction "LCD_PCLK_F1") (pintype "bidirectional"))
    )
    (net (code "182") (name "Net-(TP163-1)") (class "Default")
      (node (ref "TP163") (pin "P$1") (pinfunction "1_P$1") (pintype "bidirectional"))
      (node (ref "U7") (pin "F10") (pinfunction "SYS_VDD_1P8V_F10") (pintype "power_in"))
      (node (ref "U7") (pin "G10") (pinfunction "SYS_VDD_1P8V_G10") (pintype "power_in"))
      (node (ref "U7") (pin "H10") (pinfunction "SYS_VDD_1P8V_H10") (pintype "power_in"))
      (node (ref "U7") (pin "H11") (pinfunction "SYS_VDD_1P8V_H11") (pintype "power_in"))
      (node (ref "U7") (pin "J10") (pinfunction "SYS_VDD_1P8V_J10") (pintype "power_in"))
      (node (ref "U7") (pin "J11") (pinfunction "SYS_VDD_1P8V_J11") (pintype "power_in"))
      (node (ref "U7") (pin "K10") (pinfunction "SYS_VDD_1P8V_K10") (pintype "power_in"))
      (node (ref "U7") (pin "L10") (pinfunction "SYS_VDD_1P8V_L10") (pintype "power_in"))
    )
    (net (code "183") (name "Net-(TP165-1)") (class "Default")
      (node (ref "JP101") (pin "1") (pinfunction "1_1") (pintype "passive"))
      (node (ref "TP165") (pin "P$1") (pinfunction "1_P$1") (pintype "bidirectional"))
      (node (ref "U7") (pin "F8") (pinfunction "SYS_VDD3_3P3V_F8") (pintype "power_in"))
      (node (ref "U7") (pin "F9") (pinfunction "VDDSHV4_F9") (pintype "power_in"))
      (node (ref "U7") (pin "G8") (pinfunction "SYS_VDD3_3P3V_G8") (pintype "power_in"))
      (node (ref "U7") (pin "G9") (pinfunction "VDDSHV5_G9") (pintype "power_in"))
      (node (ref "U7") (pin "H7") (pinfunction "SYS_VDD3_3P3V_H7") (pintype "power_in"))
      (node (ref "U7") (pin "H8") (pinfunction "SYS_VDD3_3P3V_H8") (pintype "power_in"))
      (node (ref "U7") (pin "H9") (pinfunction "VDDSHV6_H9") (pintype "power_in"))
      (node (ref "U7") (pin "J7") (pinfunction "SYS_VDD3_3P3V_J7") (pintype "power_in"))
      (node (ref "U7") (pin "J8") (pinfunction "SYS_VDD3_3P3V_J8") (pintype "power_in"))
      (node (ref "U7") (pin "J9") (pinfunction "VDDSHV1_J9") (pintype "power_in"))
      (node (ref "U7") (pin "K8") (pinfunction "SYS_VDD3_3P3V_K8") (pintype "power_in"))
      (node (ref "U7") (pin "K9") (pinfunction "VDDSHV2_K9") (pintype "power_in"))
      (node (ref "U7") (pin "L8") (pinfunction "SYS_VDD3_3P3V_L8") (pintype "power_in"))
      (node (ref "U7") (pin "L9") (pinfunction "VDDSHV3_L9") (pintype "power_in"))
    )
    (net (code "184") (name "Net-(TP166-1)") (class "Default")
      (node (ref "TP166") (pin "P$1") (pinfunction "1_P$1") (pintype "bidirectional"))
      (node (ref "U7") (pin "G13") (pinfunction "VDDS_PLL_G13") (pintype "bidirectional"))
    )
    (net (code "185") (name "Net-(TP167-1)") (class "Default")
      (node (ref "TP167") (pin "P$1") (pinfunction "1_P$1") (pintype "bidirectional"))
      (node (ref "U7") (pin "D4") (pinfunction "EXTINTN_D4") (pintype "bidirectional"))
      (node (ref "U7") (pin "E4") (pinfunction "PMIC_NINT_E4") (pintype "output"))
    )
    (net (code "186") (name "Net-(TP168-1)") (class "Default")
      (node (ref "TP168") (pin "P$1") (pinfunction "1_P$1") (pintype "bidirectional"))
      (node (ref "U7") (pin "D6") (pinfunction "PMIC_MUX_OUT_D6") (pintype "bidirectional"))
    )
    (net (code "187") (name "Net-(TP169-1)") (class "Default")
      (node (ref "TP169") (pin "P$1") (pinfunction "1_P$1") (pintype "bidirectional"))
      (node (ref "U7") (pin "C8") (pinfunction "AIN5_C8") (pintype "bidirectional"))
    )
    (net (code "188") (name "Net-(TP170-1)") (class "Default")
      (node (ref "TP170") (pin "P$1") (pinfunction "1_P$1") (pintype "bidirectional"))
      (node (ref "U7") (pin "D7") (pinfunction "AIN7_D7") (pintype "bidirectional"))
    )
    (net (code "189") (name "Net-(TP171-1)") (class "Default")
      (node (ref "TP171") (pin "P$1") (pinfunction "1_P$1") (pintype "bidirectional"))
      (node (ref "U7") (pin "A9") (pinfunction "AGND_ADC_A9") (pintype "bidirectional"))
      (node (ref "U7") (pin "B7") (pinfunction "VREFP_B7") (pintype "bidirectional"))
      (node (ref "U7") (pin "B9") (pinfunction "VREFN_B9") (pintype "bidirectional"))
    )
    (net (code "190") (name "Net-(TP172-1)") (class "Default")
      (node (ref "TP172") (pin "P$1") (pinfunction "1_P$1") (pintype "bidirectional"))
      (node (ref "U7") (pin "D12") (pinfunction "NC_D12") (pintype "bidirectional"))
    )
    (net (code "191") (name "Net-(TP173-1)") (class "Default")
      (node (ref "TP173") (pin "P$1") (pinfunction "1_P$1") (pintype "bidirectional"))
      (node (ref "U7") (pin "D5") (pinfunction "CAP_VDD_RTC_D5") (pintype "bidirectional"))
    )
    (net (code "192") (name "Net-(TP174-1)") (class "Default")
      (node (ref "TP174") (pin "P$1") (pinfunction "1_P$1") (pintype "bidirectional"))
      (node (ref "U7") (pin "D13") (pinfunction "MDC_D13") (pintype "bidirectional"))
    )
    (net (code "193") (name "Net-(TP175-1)") (class "Default")
      (node (ref "TP175") (pin "P$1") (pinfunction "1_P$1") (pintype "bidirectional"))
      (node (ref "U7") (pin "C6") (pinfunction "AIN3_C6") (pintype "bidirectional"))
    )
    (net (code "194") (name "Net-(TP176-1)") (class "Default")
      (node (ref "TP176") (pin "P$1") (pinfunction "1_P$1") (pintype "bidirectional"))
      (node (ref "U7") (pin "C7") (pinfunction "AIN4_C7") (pintype "bidirectional"))
    )
    (net (code "195") (name "Net-(TP177-1)") (class "Default")
      (node (ref "TP177") (pin "P$1") (pinfunction "1_P$1") (pintype "bidirectional"))
      (node (ref "U7") (pin "C12") (pinfunction "UART0_CTSN_C12") (pintype "bidirectional"))
    )
    (net (code "196") (name "Net-(TP178-1)") (class "Default")
      (node (ref "TP178") (pin "P$1") (pinfunction "1_P$1") (pintype "bidirectional"))
      (node (ref "U7") (pin "C13") (pinfunction "UART0_RTSN_C13") (pintype "bidirectional"))
    )
    (net (code "197") (name "Net-(TP179-1)") (class "Default")
      (node (ref "TP179") (pin "P$1") (pinfunction "1_P$1") (pintype "bidirectional"))
      (node (ref "U7") (pin "C9") (pinfunction "AIN6_C9") (pintype "bidirectional"))
    )
    (net (code "198") (name "Net-(TP180-1)") (class "Default")
      (node (ref "TP180") (pin "P$1") (pinfunction "1_P$1") (pintype "bidirectional"))
      (node (ref "U7") (pin "C5") (pinfunction "ECAP0_IN_PWM0_OUT_C5") (pintype "bidirectional"))
    )
    (net (code "199") (name "Net-(TP181-1)") (class "Default")
      (node (ref "TP181") (pin "P$1") (pinfunction "1_P$1") (pintype "bidirectional"))
      (node (ref "U7") (pin "B6") (pinfunction "AIN2_B6") (pintype "bidirectional"))
    )
    (net (code "200") (name "Net-(TP182-1)") (class "Default")
      (node (ref "TP182") (pin "P$1") (pinfunction "1_P$1") (pintype "bidirectional"))
      (node (ref "U7") (pin "A7") (pinfunction "SYS_ADC_1P8V_A7") (pintype "bidirectional"))
    )
    (net (code "201") (name "Net-(U2-EN)") (class "Default")
      (node (ref "R6") (pin "2") (pinfunction "2_2") (pintype "passive"))
      (node (ref "U2") (pin "4") (pinfunction "EN_4") (pintype "input"))
      (node (ref "U7") (pin "M14") (pinfunction "USB1_DRVVBUS_M14") (pintype "bidirectional"))
    )
    (net (code "202") (name "Net-(U2-~{FLT})") (class "Default")
      (node (ref "R7") (pin "1") (pinfunction "1_1") (pintype "passive"))
      (node (ref "U2") (pin "3") (pinfunction "~{FLT}_3") (pintype "output"))
    )
    (net (code "203") (name "Net-(U3-VDDI)") (class "Default")
      (node (ref "C10") (pin "1") (pinfunction "1_1") (pintype "passive"))
      (node (ref "C12") (pin "1") (pinfunction "1_1") (pintype "passive"))
      (node (ref "U3") (pin "C2") (pinfunction "VDDI_C2") (pintype "power_in"))
    )
    (net (code "204") (name "Net-(U5-DIR)") (class "Default")
      (node (ref "R14") (pin "1") (pinfunction "1_1") (pintype "passive"))
      (node (ref "U5") (pin "2") (pinfunction "DIR_2") (pintype "input"))
    )
    (net (code "205") (name "Net-(U6-1DIR)") (class "Default")
      (node (ref "R16") (pin "1") (pinfunction "1_1") (pintype "passive"))
      (node (ref "U6") (pin "1") (pinfunction "1DIR_1") (pintype "input"))
      (node (ref "U6") (pin "24") (pinfunction "2DIR_24") (pintype "input"))
    )
    (net (code "206") (name "Net-(U7A-EEPROM_WP)") (class "Default")
      (node (ref "R75") (pin "2") (pinfunction "2_2") (pintype "passive"))
      (node (ref "U7") (pin "M2") (pinfunction "EEPROM_WP_M2") (pintype "bidirectional"))
    )
    (net (code "207") (name "Net-(U7A-I2C0_SCL)") (class "Default")
      (node (ref "R73") (pin "2") (pinfunction "2_2") (pintype "passive"))
      (node (ref "U7") (pin "C10") (pinfunction "I2C0_SCL_C10") (pintype "bidirectional"))
      (node (ref "U7") (pin "D10") (pinfunction "PMIC_SCL_D10") (pintype "bidirectional"))
    )
    (net (code "208") (name "Net-(U7A-I2C0_SDA)") (class "Default")
      (node (ref "R74") (pin "2") (pinfunction "2_2") (pintype "passive"))
      (node (ref "U7") (pin "C11") (pinfunction "I2C0_SDA_C11") (pintype "bidirectional"))
      (node (ref "U7") (pin "D11") (pinfunction "PMIC_SDA_D11") (pintype "bidirectional"))
    )
    (net (code "209") (name "Net-(U7A-RTC_KALDO_ENN)") (class "Default")
      (node (ref "R15") (pin "2") (pinfunction "2_2") (pintype "passive"))
      (node (ref "U7") (pin "M16") (pinfunction "RTC_KALDO_ENN_M16") (pintype "bidirectional"))
    )
    (net (code "210") (name "Net-(U7B-EMU0)") (class "Default")
      (node (ref "R22") (pin "1") (pinfunction "1_1") (pintype "passive"))
      (node (ref "U7") (pin "E2") (pinfunction "EMU0_E2") (pintype "bidirectional"))
    )
    (net (code "211") (name "Net-(U7B-EMU1)") (class "Default")
      (node (ref "R20") (pin "1") (pinfunction "1_1") (pintype "passive"))
      (node (ref "U7") (pin "E3") (pinfunction "EMU1_E3") (pintype "bidirectional"))
    )
    (net (code "212") (name "Net-(U7B-OSC1_GND)") (class "Default")
      (node (ref "C29") (pin "2") (pinfunction "2_2") (pintype "passive"))
      (node (ref "C30") (pin "2") (pinfunction "2_2") (pintype "passive"))
      (node (ref "U7") (pin "B5") (pinfunction "OSC1_GND_B5") (pintype "bidirectional"))
    )
    (net (code "213") (name "Net-(U7B-OSC1_IN)") (class "Default")
      (node (ref "C30") (pin "1") (pinfunction "1_1") (pintype "passive"))
      (node (ref "R27") (pin "2") (pinfunction "2_2") (pintype "passive"))
      (node (ref "U7") (pin "A6") (pinfunction "OSC1_IN_A6") (pintype "bidirectional"))
      (node (ref "Y2") (pin "P$2") (pinfunction "P$2_P$2") (pintype "passive"))
    )
    (net (code "214") (name "Net-(U7B-OSC1_OUT)") (class "Default")
      (node (ref "C29") (pin "1") (pinfunction "1_1") (pintype "passive"))
      (node (ref "R27") (pin "1") (pinfunction "1_1") (pintype "passive"))
      (node (ref "U7") (pin "A5") (pinfunction "OSC1_OUT_A5") (pintype "bidirectional"))
      (node (ref "Y2") (pin "P$1") (pinfunction "P$1_P$1") (pintype "passive"))
    )
    (net (code "215") (name "Net-(U7B-USB1_ID)") (class "Default")
      (node (ref "JP100") (pin "1") (pinfunction "1_1") (pintype "passive"))
      (node (ref "U7") (pin "L14") (pinfunction "USB1_ID_L14") (pintype "bidirectional"))
    )
    (net (code "216") (name "Net-(U7C-GPMC_A5)") (class "Default")
      (node (ref "R2") (pin "1") (pinfunction "1_1") (pintype "passive"))
      (node (ref "U7") (pin "P13") (pinfunction "GPMC_A5_P13") (pintype "bidirectional"))
    )
    (net (code "217") (name "Net-(U7C-GPMC_A6)") (class "Default")
      (node (ref "R3") (pin "1") (pinfunction "1_1") (pintype "passive"))
      (node (ref "U7") (pin "T14") (pinfunction "GPMC_A6_T14") (pintype "bidirectional"))
    )
    (net (code "218") (name "Net-(U7C-GPMC_A7)") (class "Default")
      (node (ref "R4") (pin "1") (pinfunction "1_1") (pintype "passive"))
      (node (ref "U7") (pin "R14") (pinfunction "GPMC_A7_R14") (pintype "bidirectional"))
    )
    (net (code "219") (name "Net-(U7C-GPMC_A8)") (class "Default")
      (node (ref "R5") (pin "1") (pinfunction "1_1") (pintype "passive"))
      (node (ref "U7") (pin "P14") (pinfunction "GPMC_A8_P14") (pintype "bidirectional"))
    )
    (net (code "220") (name "Net-(U7C-MMC0_DAT0)") (class "Default")
      (node (ref "JP111") (pin "2") (pinfunction "2_2") (pintype "passive"))
      (node (ref "U7") (pin "A16") (pinfunction "MMC0_DAT0_A16") (pintype "bidirectional"))
    )
    (net (code "221") (name "Net-(U7C-MMC0_DAT1)") (class "Default")
      (node (ref "JP110") (pin "2") (pinfunction "2_2") (pintype "passive"))
      (node (ref "U7") (pin "A15") (pinfunction "MMC0_DAT1_A15") (pintype "bidirectional"))
    )
    (net (code "222") (name "Net-(U7C-MMC0_DAT2)") (class "Default")
      (node (ref "JP103") (pin "2") (pinfunction "2_2") (pintype "passive"))
      (node (ref "U7") (pin "C16") (pinfunction "MMC0_DAT2_C16") (pintype "bidirectional"))
    )
    (net (code "223") (name "Net-(U7C-MMC0_DAT3)") (class "Default")
      (node (ref "JP102") (pin "2") (pinfunction "2_2") (pintype "passive"))
      (node (ref "U7") (pin "C15") (pinfunction "MMC0_DAT3_C15") (pintype "bidirectional"))
    )
    (net (code "224") (name "Net-(U7D-LCD_DATA0)") (class "Default")
      (node (ref "JP105") (pin "2") (pinfunction "2_2") (pintype "passive"))
      (node (ref "U7") (pin "G3") (pinfunction "LCD_DATA0_G3") (pintype "bidirectional"))
    )
    (net (code "225") (name "Net-(U7D-LCD_DATA1)") (class "Default")
      (node (ref "JP106") (pin "2") (pinfunction "2_2") (pintype "passive"))
      (node (ref "U7") (pin "G2") (pinfunction "LCD_DATA1_G2") (pintype "bidirectional"))
    )
    (net (code "226") (name "Net-(U7D-LCD_DATA2)") (class "Default")
      (node (ref "J3") (pin "2") (pinfunction "2_2") (pintype "passive"))
      (node (ref "JP107") (pin "2") (pinfunction "2_2") (pintype "passive"))
      (node (ref "U7") (pin "G1") (pinfunction "LCD_DATA2_G1") (pintype "bidirectional"))
    )
    (net (code "227") (name "Net-(U7D-LCD_DATA3)") (class "Default")
      (node (ref "JP108") (pin "2") (pinfunction "2_2") (pintype "passive"))
      (node (ref "U7") (pin "H3") (pinfunction "LCD_DATA3_H3") (pintype "bidirectional"))
    )
    (net (code "228") (name "Net-(U7D-LCD_DATA4)") (class "Default")
      (node (ref "JP109") (pin "2") (pinfunction "2_2") (pintype "passive"))
      (node (ref "U7") (pin "H2") (pinfunction "LCD_DATA4_H2") (pintype "bidirectional"))
    )
    (net (code "229") (name "Net-(U9-EN)") (class "Default")
      (node (ref "R21") (pin "1") (pinfunction "1_1") (pintype "passive"))
      (node (ref "U9") (pin "5") (pinfunction "EN_5") (pintype "input"))
    )
    (net (code "230") (name "Net-(U10-ANODE)") (class "Default")
      (node (ref "JP104") (pin "2") (pinfunction "2_2") (pintype "passive"))
      (node (ref "Q1") (pin "C") (pinfunction "C_C") (pintype "passive"))
      (node (ref "R31") (pin "1") (pinfunction "1_1") (pintype "passive"))
      (node (ref "U10") (pin "3") (pinfunction "ANODE_3") (pintype "bidirectional"))
    )
    (net (code "231") (name "Net-(U10-CATHODE)") (class "Default")
      (node (ref "Q1") (pin "B") (pinfunction "B_B") (pintype "passive"))
      (node (ref "R23") (pin "1") (pinfunction "1_1") (pintype "passive"))
      (node (ref "U10") (pin "2") (pinfunction "CATHODE_2") (pintype "bidirectional"))
    )
    (net (code "232") (name "Net-(U10-REF)") (class "Default")
      (node (ref "R28") (pin "1") (pinfunction "1_1") (pintype "passive"))
      (node (ref "R31") (pin "2") (pinfunction "2_2") (pintype "passive"))
      (node (ref "U10") (pin "1") (pinfunction "REF_1") (pintype "bidirectional"))
    )
    (net (code "233") (name "Net-(U11-RXD)") (class "Default")
      (node (ref "U11") (pin "4") (pinfunction "RXD_4") (pintype "output"))
      (node (ref "U7") (pin "B11") (pinfunction "UART1_TXD_B11") (pintype "bidirectional"))
    )
    (net (code "234") (name "Net-(U11-TXD)") (class "Default")
      (node (ref "U11") (pin "1") (pinfunction "TXD_1") (pintype "input"))
      (node (ref "U7") (pin "A11") (pinfunction "UART1_RXD_A11") (pintype "bidirectional"))
    )
    (net (code "235") (name "Net-(U12-INP)") (class "Default")
      (node (ref "C32") (pin "1") (pinfunction "1_1") (pintype "passive"))
      (node (ref "R36") (pin "1") (pinfunction "1_1") (pintype "passive"))
      (node (ref "R37") (pin "1") (pinfunction "1_1") (pintype "passive"))
      (node (ref "U12") (pin "1") (pinfunction "INP_1") (pintype "input"))
    )
    (net (code "236") (name "Net-(U12-OUT)") (class "Default")
      (node (ref "R35") (pin "1") (pinfunction "1_1") (pintype "passive"))
      (node (ref "TP44") (pin "1") (pinfunction "1_1") (pintype "passive"))
      (node (ref "U12") (pin "4") (pinfunction "OUT_4") (pintype "output"))
    )
    (net (code "237") (name "Net-(U13-INP)") (class "Default")
      (node (ref "C35") (pin "1") (pinfunction "1_1") (pintype "passive"))
      (node (ref "R44") (pin "1") (pinfunction "1_1") (pintype "passive"))
      (node (ref "R45") (pin "1") (pinfunction "1_1") (pintype "passive"))
      (node (ref "U13") (pin "1") (pinfunction "INP_1") (pintype "input"))
    )
    (net (code "238") (name "Net-(U13-OUT)") (class "Default")
      (node (ref "R43") (pin "1") (pinfunction "1_1") (pintype "passive"))
      (node (ref "TP43") (pin "1") (pinfunction "1_1") (pintype "passive"))
      (node (ref "U13") (pin "4") (pinfunction "OUT_4") (pintype "output"))
    )
    (net (code "239") (name "Net-(U14-CIN1+)") (class "Default")
      (node (ref "R50") (pin "1") (pinfunction "1_1") (pintype "passive"))
      (node (ref "R51") (pin "2") (pinfunction "2_2") (pintype "passive"))
      (node (ref "TP57") (pin "1") (pinfunction "1_1") (pintype "passive"))
      (node (ref "U14") (pin "10") (pinfunction "CIN1+_10") (pintype "input"))
    )
    (net (code "240") (name "Net-(U14-CIN1-)") (class "Default")
      (node (ref "R42") (pin "2") (pinfunction "2_2") (pintype "passive"))
      (node (ref "R47") (pin "1") (pinfunction "1_1") (pintype "passive"))
      (node (ref "TP47") (pin "1") (pinfunction "1_1") (pintype "passive"))
      (node (ref "U14") (pin "11") (pinfunction "CIN1-_11") (pintype "input"))
    )
    (net (code "241") (name "Net-(U14-CIN2+)") (class "Default")
      (node (ref "R47") (pin "2") (pinfunction "2_2") (pintype "passive"))
      (node (ref "U14") (pin "12") (pinfunction "REF_12") (pintype "output"))
      (node (ref "U14") (pin "8") (pinfunction "CIN2+_8") (pintype "input"))
    )
    (net (code "242") (name "Net-(U14-INHIBIT)") (class "Default")
      (node (ref "R38") (pin "1") (pinfunction "1_1") (pintype "passive"))
      (node (ref "U14") (pin "5") (pinfunction "INHIBIT_5") (pintype "input"))
    )
    (net (code "243") (name "Net-(U14-IOUT)") (class "Default")
      (node (ref "R50") (pin "2") (pinfunction "2_2") (pintype "passive"))
      (node (ref "U14") (pin "14") (pinfunction "IOUT_14") (pintype "output"))
    )
    (net (code "244") (name "Net-(U14-RS+)") (class "Default")
      (node (ref "C44") (pin "1") (pinfunction "1_1") (pintype "passive"))
      (node (ref "Q6") (pin "1") (pinfunction "D_1") (pintype "passive"))
      (node (ref "Q6") (pin "2") (pinfunction "D_2") (pintype "passive"))
      (node (ref "Q6") (pin "5") (pinfunction "D_5") (pintype "passive"))
      (node (ref "Q6") (pin "6") (pinfunction "D_6") (pintype "passive"))
      (node (ref "R63") (pin "1") (pinfunction "1_1") (pintype "passive"))
      (node (ref "U14") (pin "16") (pinfunction "RS+_16") (pintype "passive"))
    )
    (net (code "245") (name "Net-(U15-PG)") (class "Default")
      (node (ref "TP48") (pin "1") (pinfunction "1_1") (pintype "passive"))
      (node (ref "U15") (pin "13") (pinfunction "PG_13") (pintype "open_collector"))
    )
    (net (code "246") (name "Net-(U15-SYNC)") (class "Default")
      (node (ref "R34") (pin "1") (pinfunction "1_1") (pintype "passive"))
      (node (ref "R40") (pin "2") (pinfunction "2_2") (pintype "passive"))
      (node (ref "TP46") (pin "1") (pinfunction "1_1") (pintype "passive"))
      (node (ref "U15") (pin "5") (pinfunction "SYNC_5") (pintype "input"))
    )
    (net (code "247") (name "Net-(U16-IO6)") (class "Default")
      (node (ref "TP53") (pin "1") (pinfunction "1_1") (pintype "passive"))
      (node (ref "U16") (pin "11") (pinfunction "IO6_11") (pintype "bidirectional"))
    )
    (net (code "248") (name "Net-(U16-IO7)") (class "Default")
      (node (ref "TP56") (pin "1") (pinfunction "1_1") (pintype "passive"))
      (node (ref "U16") (pin "12") (pinfunction "IO7_12") (pintype "bidirectional"))
    )
    (net (code "249") (name "Net-(U16-~{RESET})") (class "Default")
      (node (ref "R72") (pin "1") (pinfunction "1_1") (pintype "passive"))
      (node (ref "U16") (pin "13") (pinfunction "~{RESET}_13") (pintype "input"))
    )
    (net (code "250") (name "Net-(U17-MISO)") (class "Default")
      (node (ref "U17") (pin "2") (pinfunction "MISO_2") (pintype "output"))
      (node (ref "U7") (pin "B13") (pinfunction "SPI0_D0_B13") (pintype "bidirectional"))
    )
    (net (code "251") (name "Net-(U17-MOSI)") (class "Default")
      (node (ref "U17") (pin "5") (pinfunction "MOSI_5") (pintype "input"))
      (node (ref "U7") (pin "B14") (pinfunction "SPI0_D1_B14") (pintype "bidirectional"))
    )
    (net (code "252") (name "Net-(U17-SCK)") (class "Default")
      (node (ref "U17") (pin "6") (pinfunction "SCK_6") (pintype "input"))
      (node (ref "U7") (pin "A13") (pinfunction "SPI0_SCLK_A13") (pintype "bidirectional"))
    )
    (net (code "253") (name "Net-(U17-~{CS})") (class "Default")
      (node (ref "U17") (pin "1") (pinfunction "~{CS}_1") (pintype "input"))
      (node (ref "U7") (pin "A14") (pinfunction "SPI0_CS0_A14") (pintype "bidirectional"))
    )
    (net (code "254") (name "Net-(U17-~{WP})") (class "Default")
      (node (ref "R59") (pin "1") (pinfunction "1_1") (pintype "passive"))
      (node (ref "R60") (pin "2") (pinfunction "2_2") (pintype "passive"))
      (node (ref "U17") (pin "3") (pinfunction "~{WP}_3") (pintype "input"))
    )
    (net (code "255") (name "ON{slash}~{OFF}") (class "Default")
      (node (ref "C34") (pin "1") (pinfunction "1_1") (pintype "passive"))
      (node (ref "Q4") (pin "1") (pinfunction "G_1") (pintype "passive"))
      (node (ref "R46") (pin "2") (pinfunction "2_2") (pintype "passive"))
      (node (ref "R49") (pin "2") (pinfunction "2_2") (pintype "passive"))
      (node (ref "TP50") (pin "1") (pinfunction "1_1") (pintype "passive"))
      (node (ref "U14") (pin "1") (pinfunction "VCC_1") (pintype "power_in"))
      (node (ref "U16") (pin "8") (pinfunction "IO3_8") (pintype "bidirectional"))
    )
    (net (code "256") (name "OPD_PWR") (class "Default")
      (node (ref "J4") (pin "15") (pinfunction "15_15") (pintype "passive"))
      (node (ref "J4") (pin "16") (pinfunction "16_16") (pintype "passive"))
      (node (ref "R71") (pin "1") (pinfunction "1_1") (pintype "passive"))
    )
    (net (code "257") (name "OPD_SCL") (class "Default")
      (node (ref "J4") (pin "13") (pinfunction "13_13") (pintype "passive"))
      (node (ref "J4") (pin "14") (pinfunction "14_14") (pintype "passive"))
      (node (ref "R48") (pin "1") (pinfunction "1_1") (pintype "passive"))
    )
    (net (code "258") (name "OPD_SDA") (class "Default")
      (node (ref "J4") (pin "11") (pinfunction "11_11") (pintype "passive"))
      (node (ref "J4") (pin "12") (pinfunction "12_12") (pintype "passive"))
      (node (ref "R41") (pin "1") (pinfunction "1_1") (pintype "passive"))
    )
    (net (code "259") (name "OSC0_GND") (class "Default")
      (node (ref "C19") (pin "1") (pinfunction "1_1") (pintype "passive"))
      (node (ref "C22") (pin "1") (pinfunction "1_1") (pintype "passive"))
      (node (ref "U7") (pin "N15") (pinfunction "OSC0_GND_N15") (pintype "bidirectional"))
    )
    (net (code "260") (name "OSC0_IN") (class "Default")
      (node (ref "C19") (pin "2") (pinfunction "2_2") (pintype "passive"))
      (node (ref "R13") (pin "2") (pinfunction "2_2") (pintype "passive"))
      (node (ref "U7") (pin "P16") (pinfunction "OSC0_IN_P16") (pintype "bidirectional"))
      (node (ref "Y1") (pin "1") (pinfunction "X1_1") (pintype "passive"))
    )
    (net (code "261") (name "OSC0_OUT") (class "Default")
      (node (ref "C22") (pin "2") (pinfunction "2_2") (pintype "passive"))
      (node (ref "R13") (pin "1") (pinfunction "1_1") (pintype "passive"))
      (node (ref "U7") (pin "N16") (pinfunction "OSC0_OUT_N16") (pintype "bidirectional"))
      (node (ref "Y1") (pin "3") (pinfunction "X2_3") (pintype "passive"))
    )
    (net (code "262") (name "PB6{slash}SCL") (class "Default")
      (node (ref "TP67") (pin "1") (pinfunction "1_1") (pintype "passive"))
      (node (ref "U16") (pin "4") (pinfunction "IO0_4") (pintype "bidirectional"))
    )
    (net (code "263") (name "PB7{slash}SDA") (class "Default")
      (node (ref "TP68") (pin "1") (pinfunction "1_1") (pintype "passive"))
      (node (ref "U16") (pin "5") (pinfunction "IO1_5") (pintype "bidirectional"))
    )
    (net (code "264") (name "PEN-SCL-FILT") (class "Default")
      (node (ref "Q3") (pin "6") (pinfunction "D_6") (pintype "passive"))
      (node (ref "R37") (pin "2") (pinfunction "2_2") (pintype "passive"))
      (node (ref "R65") (pin "1") (pinfunction "1_1") (pintype "passive"))
      (node (ref "R67") (pin "1") (pinfunction "1_1") (pintype "passive"))
      (node (ref "R69") (pin "1") (pinfunction "1_1") (pintype "passive"))
      (node (ref "TP42") (pin "1") (pinfunction "1_1") (pintype "passive"))
      (node (ref "TP66") (pin "1") (pinfunction "1_1") (pintype "passive"))
      (node (ref "U16") (pin "15") (pinfunction "SCL_15") (pintype "input"))
    )
    (net (code "265") (name "PEN-SDA-FILT") (class "Default")
      (node (ref "Q3") (pin "4") (pinfunction "D_4") (pintype "passive"))
      (node (ref "R45") (pin "2") (pinfunction "2_2") (pintype "passive"))
      (node (ref "R66") (pin "2") (pinfunction "2_2") (pintype "passive"))
      (node (ref "R68") (pin "2") (pinfunction "2_2") (pintype "passive"))
      (node (ref "R70") (pin "2") (pinfunction "2_2") (pintype "passive"))
      (node (ref "TP41") (pin "1") (pinfunction "1_1") (pintype "passive"))
      (node (ref "TP65") (pin "1") (pinfunction "1_1") (pintype "passive"))
      (node (ref "U16") (pin "16") (pinfunction "SDA_16") (pintype "bidirectional"))
    )
    (net (code "266") (name "PIXCLK_E") (class "Default")
      (node (ref "J101") (pin "5") (pinfunction "5_5") (pintype "passive"))
      (node (ref "U6") (pin "20") (pinfunction "2B6_20") (pintype "bidirectional"))
    )
    (net (code "267") (name "PIXCLK_I") (class "Default")
      (node (ref "TP28") (pin "P$1") (pinfunction "1_P$1") (pintype "bidirectional"))
      (node (ref "U6") (pin "29") (pinfunction "2A6_29") (pintype "bidirectional"))
      (node (ref "U7") (pin "B4") (pinfunction "XDMA_EVENT_INTR1_B4") (pintype "bidirectional"))
    )
    (net (code "268") (name "PMIC_PGOOD") (class "Default")
      (node (ref "TP110") (pin "P$1") (pinfunction "1_P$1") (pintype "bidirectional"))
      (node (ref "U4") (pin "2") (pinfunction "A_2") (pintype "bidirectional"))
      (node (ref "U7") (pin "N12") (pinfunction "PMIC_PGOOD_N12") (pintype "output"))
      (node (ref "U7") (pin "P11") (pinfunction "PWRONRSTN_P11") (pintype "bidirectional"))
    )
    (net (code "269") (name "POUT") (class "Default")
      (node (ref "TP64") (pin "1") (pinfunction "1_1") (pintype "passive"))
      (node (ref "U14") (pin "13") (pinfunction "POUT_13") (pintype "output"))
    )
    (net (code "270") (name "RESET") (class "Default")
      (node (ref "TP10") (pin "P$1") (pinfunction "1_P$1") (pintype "bidirectional"))
      (node (ref "U5") (pin "19") (pinfunction "B3_19") (pintype "bidirectional"))
      (node (ref "U7") (pin "D16") (pinfunction "MII1_RXD1_D16") (pintype "bidirectional"))
    )
    (net (code "271") (name "RESET#") (class "Default")
      (node (ref "JP1") (pin "1") (pinfunction "1_1") (pintype "passive"))
      (node (ref "TP109") (pin "P$1") (pinfunction "1_P$1") (pintype "bidirectional"))
      (node (ref "U4") (pin "4") (pinfunction "Y_4") (pintype "bidirectional"))
      (node (ref "U7") (pin "R11") (pinfunction "WARMRSTN_R11") (pintype "bidirectional"))
    )
    (net (code "272") (name "SADDR") (class "Default")
      (node (ref "TP7") (pin "P$1") (pinfunction "1_P$1") (pintype "bidirectional"))
      (node (ref "U5") (pin "16") (pinfunction "B6_16") (pintype "bidirectional"))
      (node (ref "U7") (pin "D15") (pinfunction "MII1_RXD2_D15") (pintype "bidirectional"))
    )
    (net (code "273") (name "SADDR_E") (class "Default")
      (node (ref "J101") (pin "27") (pinfunction "27_27") (pintype "passive"))
      (node (ref "U5") (pin "8") (pinfunction "A6_8") (pintype "bidirectional"))
    )
    (net (code "274") (name "SCL_2") (class "Default")
      (node (ref "R30") (pin "2") (pinfunction "2_2") (pintype "passive"))
      (node (ref "TP37") (pin "P$1") (pinfunction "1_P$1") (pintype "bidirectional"))
      (node (ref "U7") (pin "A10") (pinfunction "UART1_RTSN_A10") (pintype "bidirectional"))
      (node (ref "U9") (pin "2") (pinfunction "SCLA_2") (pintype "bidirectional"))
    )
    (net (code "275") (name "SDA_2") (class "Default")
      (node (ref "R29") (pin "2") (pinfunction "2_2") (pintype "passive"))
      (node (ref "TP36") (pin "P$1") (pinfunction "1_P$1") (pintype "bidirectional"))
      (node (ref "U7") (pin "B10") (pinfunction "UART1_CTSN_B10") (pintype "bidirectional"))
      (node (ref "U9") (pin "3") (pinfunction "SDAA_3") (pintype "bidirectional"))
    )
    (net (code "276") (name "SPARE1") (class "Default")
      (node (ref "J4") (pin "10") (pinfunction "10_10") (pintype "passive"))
      (node (ref "J4") (pin "9") (pinfunction "9_9") (pintype "passive"))
      (node (ref "TP58") (pin "P$1") (pinfunction "1_P$1") (pintype "bidirectional"))
    )
    (net (code "277") (name "SPARE2") (class "Default")
      (node (ref "J4") (pin "7") (pinfunction "7_7") (pintype "passive"))
      (node (ref "J4") (pin "8") (pinfunction "8_8") (pintype "passive"))
      (node (ref "TP59") (pin "P$1") (pinfunction "1_P$1") (pintype "bidirectional"))
    )
    (net (code "278") (name "SPARE3") (class "Default")
      (node (ref "J4") (pin "5") (pinfunction "5_5") (pintype "passive"))
      (node (ref "J4") (pin "6") (pinfunction "6_6") (pintype "passive"))
      (node (ref "TP60") (pin "P$1") (pinfunction "1_P$1") (pintype "bidirectional"))
    )
    (net (code "279") (name "SPARE4") (class "Default")
      (node (ref "J4") (pin "3") (pinfunction "3_3") (pintype "passive"))
      (node (ref "J4") (pin "4") (pinfunction "4_4") (pintype "passive"))
      (node (ref "TP61") (pin "P$1") (pinfunction "1_P$1") (pintype "bidirectional"))
    )
    (net (code "280") (name "STANDBY") (class "Default")
      (node (ref "TP9") (pin "P$1") (pinfunction "1_P$1") (pintype "bidirectional"))
      (node (ref "U5") (pin "18") (pinfunction "B4_18") (pintype "bidirectional"))
      (node (ref "U7") (pin "D14") (pinfunction "MII1_RXD3_D14") (pintype "bidirectional"))
    )
    (net (code "281") (name "STANDBY_E") (class "Default")
      (node (ref "J101") (pin "25") (pinfunction "25_25") (pintype "passive"))
      (node (ref "U5") (pin "6") (pinfunction "A4_6") (pintype "bidirectional"))
    )
    (net (code "282") (name "TRIGGER") (class "Default")
      (node (ref "TP6") (pin "P$1") (pinfunction "1_P$1") (pintype "bidirectional"))
      (node (ref "U5") (pin "15") (pinfunction "B7_15") (pintype "bidirectional"))
      (node (ref "U7") (pin "E15") (pinfunction "MII1_RX_ER_E15") (pintype "bidirectional"))
    )
    (net (code "283") (name "TRIGGER_E") (class "Default")
      (node (ref "J101") (pin "29") (pinfunction "29_29") (pintype "passive"))
      (node (ref "U5") (pin "9") (pinfunction "A7_9") (pintype "bidirectional"))
    )
    (net (code "284") (name "UART0_RX") (class "Default")
      (node (ref "J1") (pin "12") (pinfunction "CARD-RX_12") (pintype "passive"))
      (node (ref "TP146") (pin "P$1") (pinfunction "1_P$1") (pintype "bidirectional"))
      (node (ref "U7") (pin "A12") (pinfunction "UART0_RXD_A12") (pintype "bidirectional"))
    )
    (net (code "285") (name "UART0_TX") (class "Default")
      (node (ref "J1") (pin "13") (pinfunction "CARD-TX_13") (pintype "passive"))
      (node (ref "TP142") (pin "P$1") (pinfunction "1_P$1") (pintype "bidirectional"))
      (node (ref "U7") (pin "B12") (pinfunction "UART0_TXD_B12") (pintype "bidirectional"))
    )
    (net (code "286") (name "USB_CLI_N") (class "Default")
      (node (ref "J1") (pin "5") (pinfunction "DEVICE-D-_5") (pintype "passive"))
      (node (ref "U1") (pin "1") (pinfunction "I1_1") (pintype "bidirectional"))
      (node (ref "U7") (pin "K16") (pinfunction "USB0_DM_K16") (pintype "bidirectional"))
    )
    (net (code "287") (name "USB_CLI_P") (class "Default")
      (node (ref "J1") (pin "4") (pinfunction "DEVICE-D+_4") (pintype "passive"))
      (node (ref "U1") (pin "3") (pinfunction "I2_3") (pintype "bidirectional"))
      (node (ref "U7") (pin "K15") (pinfunction "USB0_DP_K15") (pintype "bidirectional"))
    )
    (net (code "288") (name "USB_CLI_VBUS") (class "Default")
      (node (ref "FB2") (pin "1") (pinfunction "1_1") (pintype "passive"))
      (node (ref "J1") (pin "1") (pinfunction "VBUSP_1") (pintype "passive"))
      (node (ref "J1") (pin "2") (pinfunction "VBUSP_2") (pintype "passive"))
    )
    (net (code "289") (name "USB_HO_N") (class "Default")
      (node (ref "J1") (pin "8") (pinfunction "HOST-D-_8") (pintype "passive"))
      (node (ref "U1") (pin "6") (pinfunction "I4_6") (pintype "bidirectional"))
      (node (ref "U7") (pin "L16") (pinfunction "USB1_DM_L16") (pintype "bidirectional"))
    )
    (net (code "290") (name "USB_HO_PX") (class "Default")
      (node (ref "J1") (pin "7") (pinfunction "HOST-D+_7") (pintype "passive"))
      (node (ref "U1") (pin "4") (pinfunction "I3_4") (pintype "bidirectional"))
      (node (ref "U7") (pin "L15") (pinfunction "USB1_DP_L15") (pintype "bidirectional"))
    )
    (net (code "291") (name "USB_HO_VBUS") (class "Default")
      (node (ref "FB1") (pin "2") (pinfunction "2_2") (pintype "passive"))
      (node (ref "J1") (pin "17") (pinfunction "DEBUG-0_17") (pintype "passive"))
    )
    (net (code "292") (name "VBUS") (class "Default")
      (node (ref "J4") (pin "21") (pinfunction "21_21") (pintype "passive"))
      (node (ref "J4") (pin "22") (pinfunction "22_22") (pintype "passive"))
      (node (ref "J4") (pin "23") (pinfunction "23_23") (pintype "passive"))
      (node (ref "J4") (pin "24") (pinfunction "24_24") (pintype "passive"))
      (node (ref "J4") (pin "25") (pinfunction "25_25") (pintype "passive"))
      (node (ref "J4") (pin "26") (pinfunction "26_26") (pintype "passive"))
      (node (ref "Q6") (pin "4") (pinfunction "S_4") (pintype "passive"))
      (node (ref "R52") (pin "2") (pinfunction "2_2") (pintype "passive"))
    )
    (net (code "293") (name "VBUSP") (class "Default")
      (node (ref "C33") (pin "2") (pinfunction "2_2") (pintype "passive"))
      (node (ref "C37") (pin "1") (pinfunction "1_1") (pintype "passive"))
      (node (ref "C38") (pin "1") (pinfunction "1_1") (pintype "passive"))
      (node (ref "Q5") (pin "1") (pinfunction "D_1") (pintype "passive"))
      (node (ref "Q5") (pin "2") (pinfunction "D_2") (pintype "passive"))
      (node (ref "Q5") (pin "5") (pinfunction "D_5") (pintype "passive"))
      (node (ref "Q5") (pin "6") (pinfunction "D_6") (pintype "passive"))
      (node (ref "R34") (pin "2") (pinfunction "2_2") (pintype "passive"))
      (node (ref "R61") (pin "2") (pinfunction "2_2") (pintype "passive"))
      (node (ref "TP55") (pin "1") (pinfunction "1_1") (pintype "passive"))
      (node (ref "U15") (pin "2") (pinfunction "VIN_2") (pintype "power_in"))
      (node (ref "U15") (pin "3") (pinfunction "VIN_3") (pintype "power_in"))
      (node (ref "U15") (pin "4") (pinfunction "EN_4") (pintype "input"))
      (node (ref "U15") (pin "8") (pinfunction "VIN_8") (pintype "power_in"))
    )
    (net (code "294") (name "VDD") (class "Default")
      (node (ref "C15") (pin "1") (pinfunction "1_1") (pintype "passive"))
      (node (ref "C7") (pin "1") (pinfunction "1_1") (pintype "passive"))
      (node (ref "R7") (pin "2") (pinfunction "2_2") (pintype "passive"))
      (node (ref "TP3") (pin "P$1") (pinfunction "1_P$1") (pintype "bidirectional"))
      (node (ref "U2") (pin "5") (pinfunction "IN_5") (pintype "input"))
      (node (ref "U7") (pin "K6") (pinfunction "SYS_VOUT_K6") (pintype "power_in"))
      (node (ref "U7") (pin "K7") (pinfunction "SYS_VOUT_K7") (pintype "power_in"))
      (node (ref "U7") (pin "L6") (pinfunction "SYS_VOUT_L6") (pintype "power_in"))
      (node (ref "U7") (pin "L7") (pinfunction "SYS_VOUT_L7") (pintype "power_in"))
    )
    (net (code "295") (name "VIN_USB") (class "Default")
      (node (ref "C13") (pin "1") (pinfunction "1_1") (pintype "passive"))
      (node (ref "C4") (pin "1") (pinfunction "1_1") (pintype "passive"))
      (node (ref "FB2") (pin "2") (pinfunction "2_2") (pintype "passive"))
      (node (ref "TP2") (pin "P$1") (pinfunction "1_P$1") (pintype "bidirectional"))
      (node (ref "U1") (pin "5") (pinfunction "VCC_5") (pintype "power_in"))
      (node (ref "U7") (pin "J16") (pinfunction "USB0_VBUS_J16") (pintype "bidirectional"))
      (node (ref "U7") (pin "P9") (pinfunction "VIN_USB_P9") (pintype "power_in"))
      (node (ref "U7") (pin "R9") (pinfunction "VIN_USB_R9") (pintype "power_in"))
      (node (ref "U7") (pin "T9") (pinfunction "VIN_USB_T9") (pintype "power_in"))
    )
    (net (code "296") (name "VOUT_USB") (class "Default")
      (node (ref "C1") (pin "1") (pinfunction "1_1") (pintype "passive"))
      (node (ref "FB1") (pin "1") (pinfunction "1_1") (pintype "passive"))
      (node (ref "TP1") (pin "P$1") (pinfunction "1_P$1") (pintype "bidirectional"))
      (node (ref "U2") (pin "1") (pinfunction "OUT_1") (pintype "output"))
      (node (ref "U7") (pin "M15") (pinfunction "USB1_VBUS_M15") (pintype "bidirectional"))
    )
    (net (code "297") (name "VPD") (class "Default")
      (node (ref "C39") (pin "2") (pinfunction "2_2") (pintype "passive"))
      (node (ref "R32") (pin "2") (pinfunction "2_2") (pintype "passive"))
      (node (ref "R36") (pin "2") (pinfunction "2_2") (pintype "passive"))
      (node (ref "R44") (pin "2") (pinfunction "2_2") (pintype "passive"))
      (node (ref "R53") (pin "2") (pinfunction "2_2") (pintype "passive"))
      (node (ref "R55") (pin "2") (pinfunction "2_2") (pintype "passive"))
      (node (ref "R57") (pin "2") (pinfunction "2_2") (pintype "passive"))
      (node (ref "R71") (pin "2") (pinfunction "2_2") (pintype "passive"))
      (node (ref "R72") (pin "2") (pinfunction "2_2") (pintype "passive"))
      (node (ref "TP63") (pin "1") (pinfunction "1_1") (pintype "passive"))
      (node (ref "U12") (pin "5") (pinfunction "VDD_5") (pintype "power_in"))
      (node (ref "U13") (pin "5") (pinfunction "VDD_5") (pintype "power_in"))
      (node (ref "U16") (pin "14") (pinfunction "V+_14") (pintype "power_in"))
    )
    (net (code "298") (name "VREG_EN") (class "Default")
      (node (ref "TP5") (pin "P$1") (pinfunction "1_P$1") (pintype "bidirectional"))
      (node (ref "U5") (pin "14") (pinfunction "B8_14") (pintype "bidirectional"))
      (node (ref "U7") (pin "F16") (pinfunction "MII1_RX_DV_F16") (pintype "bidirectional"))
    )
    (net (code "299") (name "VREG_EN_E") (class "Default")
      (node (ref "J101") (pin "30") (pinfunction "30_30") (pintype "passive"))
      (node (ref "U5") (pin "10") (pinfunction "A8_10") (pintype "bidirectional"))
    )
    (net (code "300") (name "VSYNC_E") (class "Default")
      (node (ref "J101") (pin "3") (pinfunction "3_3") (pintype "passive"))
      (node (ref "U6") (pin "23") (pinfunction "2B8_23") (pintype "bidirectional"))
    )
    (net (code "301") (name "VSYNC_I") (class "Default")
      (node (ref "TP116") (pin "P$1") (pinfunction "1_P$1") (pintype "bidirectional"))
      (node (ref "U6") (pin "26") (pinfunction "2A8_26") (pintype "bidirectional"))
      (node (ref "U7") (pin "T6") (pinfunction "GPMC_AD14_T6") (pintype "bidirectional"))
    )
    (net (code "302") (name "unconnected-(J1-NRST-Pad10)") (class "Default")
      (node (ref "J1") (pin "10") (pinfunction "NRST_10") (pintype "passive"))
    )
    (net (code "303") (name "unconnected-(J1-SWCLK-Pad15)") (class "Default")
      (node (ref "J1") (pin "15") (pinfunction "SWCLK_15") (pintype "passive"))
    )
    (net (code "304") (name "unconnected-(J1-SWDIO-Pad14)") (class "Default")
      (node (ref "J1") (pin "14") (pinfunction "SWDIO_14") (pintype "passive"))
    )
    (net (code "305") (name "unconnected-(J1-SWO-Pad16)") (class "Default")
      (node (ref "J1") (pin "16") (pinfunction "SWO_16") (pintype "passive"))
    )
    (net (code "306") (name "unconnected-(J1-VTARGET-Pad11)") (class "Default")
      (node (ref "J1") (pin "11") (pinfunction "VTARGET_11") (pintype "passive"))
    )
    (net (code "307") (name "unconnected-(R8-11-Pad1)") (class "Default")
      (node (ref "R8") (pin "1") (pinfunction "11_1") (pintype "passive"))
    )
    (net (code "308") (name "unconnected-(R9-11-Pad1)") (class "Default")
      (node (ref "R9") (pin "1") (pinfunction "11_1") (pintype "passive"))
    )
    (net (code "309") (name "unconnected-(R9-99-Pad9)") (class "Default")
      (node (ref "R9") (pin "9") (pinfunction "99_9") (pintype "passive"))
    )
    (net (code "310") (name "unconnected-(R10-44-Pad4)") (class "Default")
      (node (ref "R10") (pin "4") (pinfunction "44_4") (pintype "passive"))
    )
    (net (code "311") (name "unconnected-(R10-66-Pad6)") (class "Default")
      (node (ref "R10") (pin "6") (pinfunction "66_6") (pintype "passive"))
    )
    (net (code "312") (name "unconnected-(R10-77-Pad7)") (class "Default")
      (node (ref "R10") (pin "7") (pinfunction "77_7") (pintype "passive"))
    )
    (net (code "313") (name "unconnected-(R24-11-Pad1)") (class "Default")
      (node (ref "R24") (pin "1") (pinfunction "11_1") (pintype "passive"))
    )
    (net (code "314") (name "unconnected-(R24-77-Pad7)") (class "Default")
      (node (ref "R24") (pin "7") (pinfunction "77_7") (pintype "passive"))
    )
    (net (code "315") (name "unconnected-(R25-88-Pad8)") (class "Default")
      (node (ref "R25") (pin "8") (pinfunction "88_8") (pintype "passive"))
    )
    (net (code "316") (name "unconnected-(U5-A1-Pad3)") (class "Default")
      (node (ref "U5") (pin "3") (pinfunction "A1_3") (pintype "bidirectional"))
    )
    (net (code "317") (name "unconnected-(U5-B1-Pad21)") (class "Default")
      (node (ref "U5") (pin "21") (pinfunction "B1_21") (pintype "bidirectional"))
    )
    (net (code "318") (name "unconnected-(U18-I3-Pad4)") (class "Default")
      (node (ref "U18") (pin "4") (pinfunction "I3_4") (pintype "bidirectional"))
    )
    (net (code "319") (name "~{FAULT}") (class "Default")
      (node (ref "Q2") (pin "3") (pinfunction "D_3") (pintype "passive"))
      (node (ref "R32") (pin "1") (pinfunction "1_1") (pintype "passive"))
      (node (ref "TP45") (pin "1") (pinfunction "1_1") (pintype "passive"))
      (node (ref "U16") (pin "7") (pinfunction "IO2_7") (pintype "bidirectional"))
    )
    (net (code "320") (name "~{OE_E}") (class "Default")
      (node (ref "J101") (pin "26") (pinfunction "26_26") (pintype "passive"))
      (node (ref "U5") (pin "7") (pinfunction "A5_7") (pintype "bidirectional"))
    )
    (net (code "321") (name "~{RESET_E}") (class "Default")
      (node (ref "J101") (pin "24") (pinfunction "24_24") (pintype "passive"))
      (node (ref "U5") (pin "5") (pinfunction "A3_5") (pintype "bidirectional"))
    )
    (net (code "322") (name "~{SD}") (class "Default")
      (node (ref "J4") (pin "39") (pinfunction "39_39") (pintype "passive"))
      (node (ref "J4") (pin "40") (pinfunction "40_40") (pintype "passive"))
    )
  )
)
